# PD.net
KiCad netlist of a schematic drawn in Altium Designer
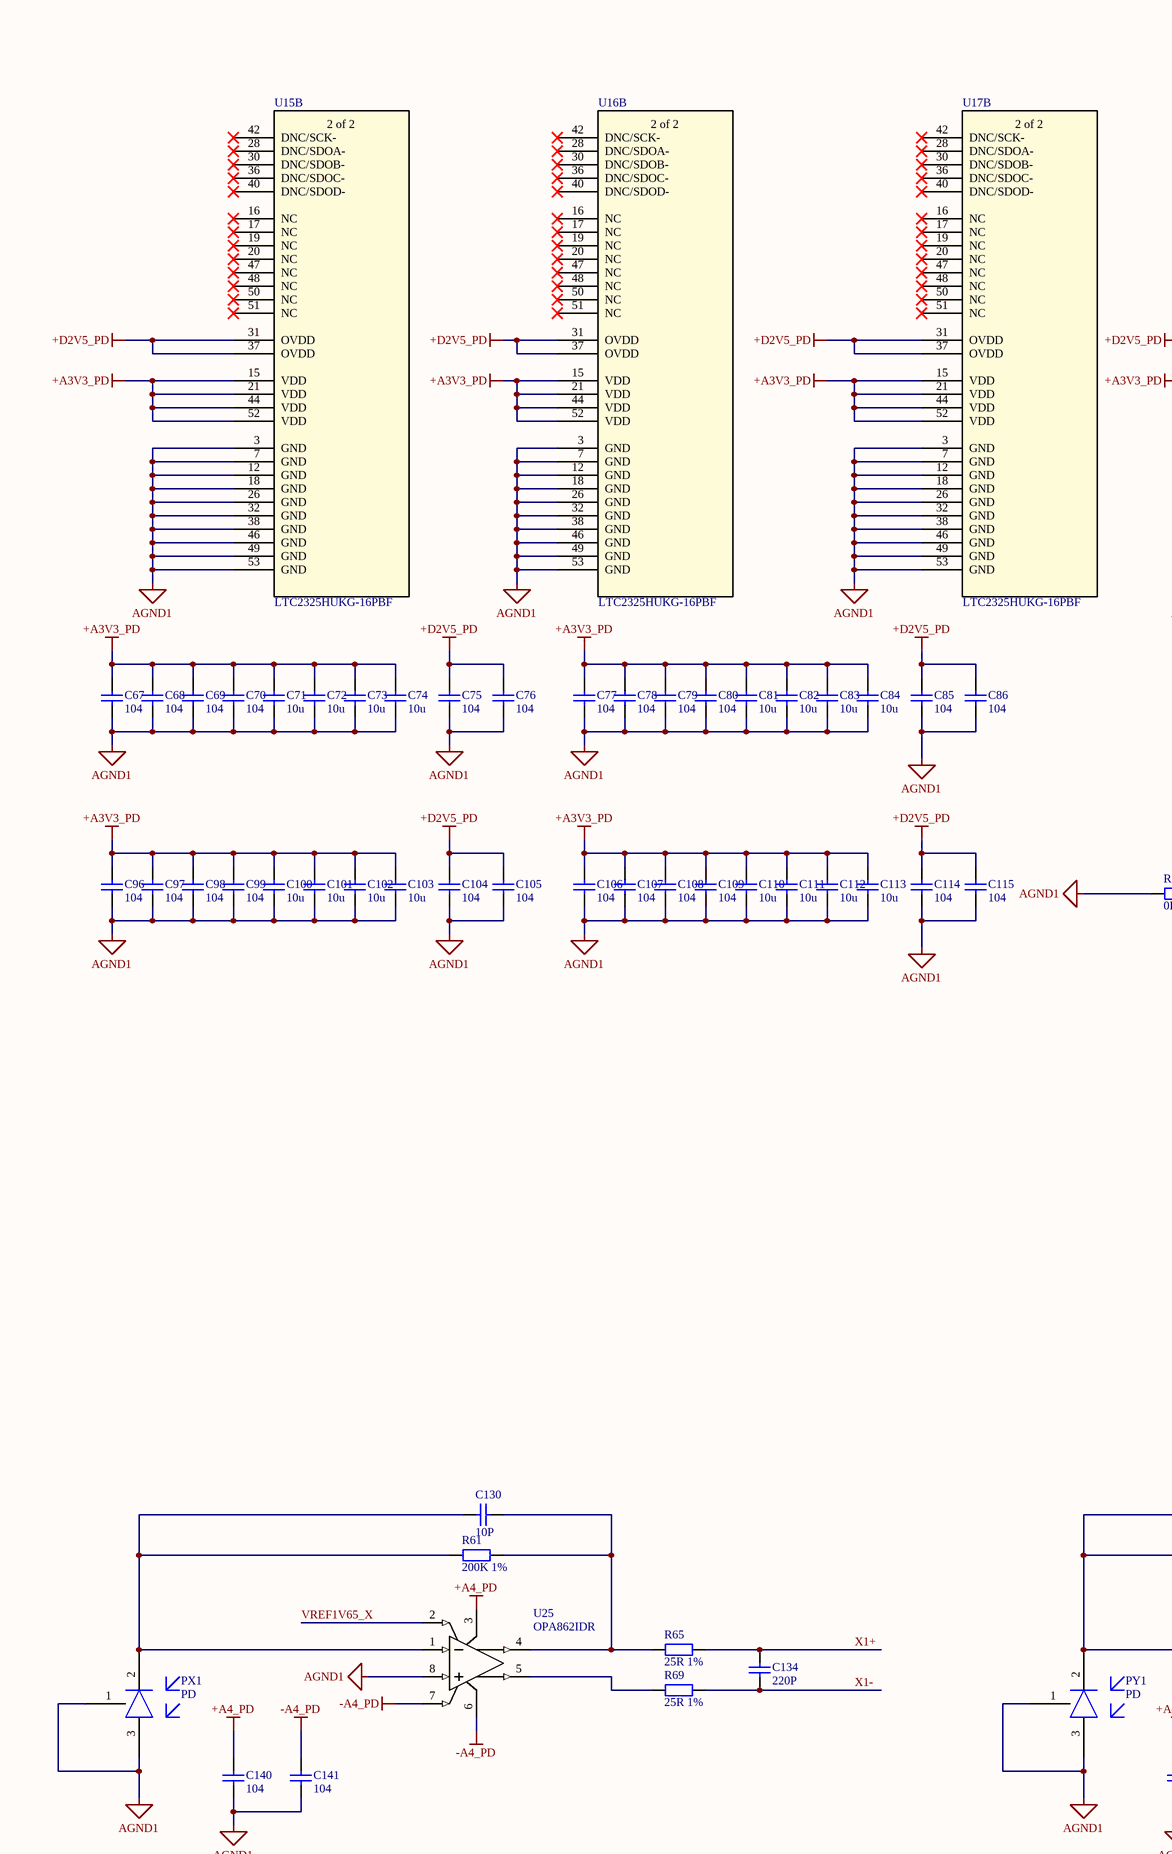
[diagram p0: PD.SchDoc, top left]
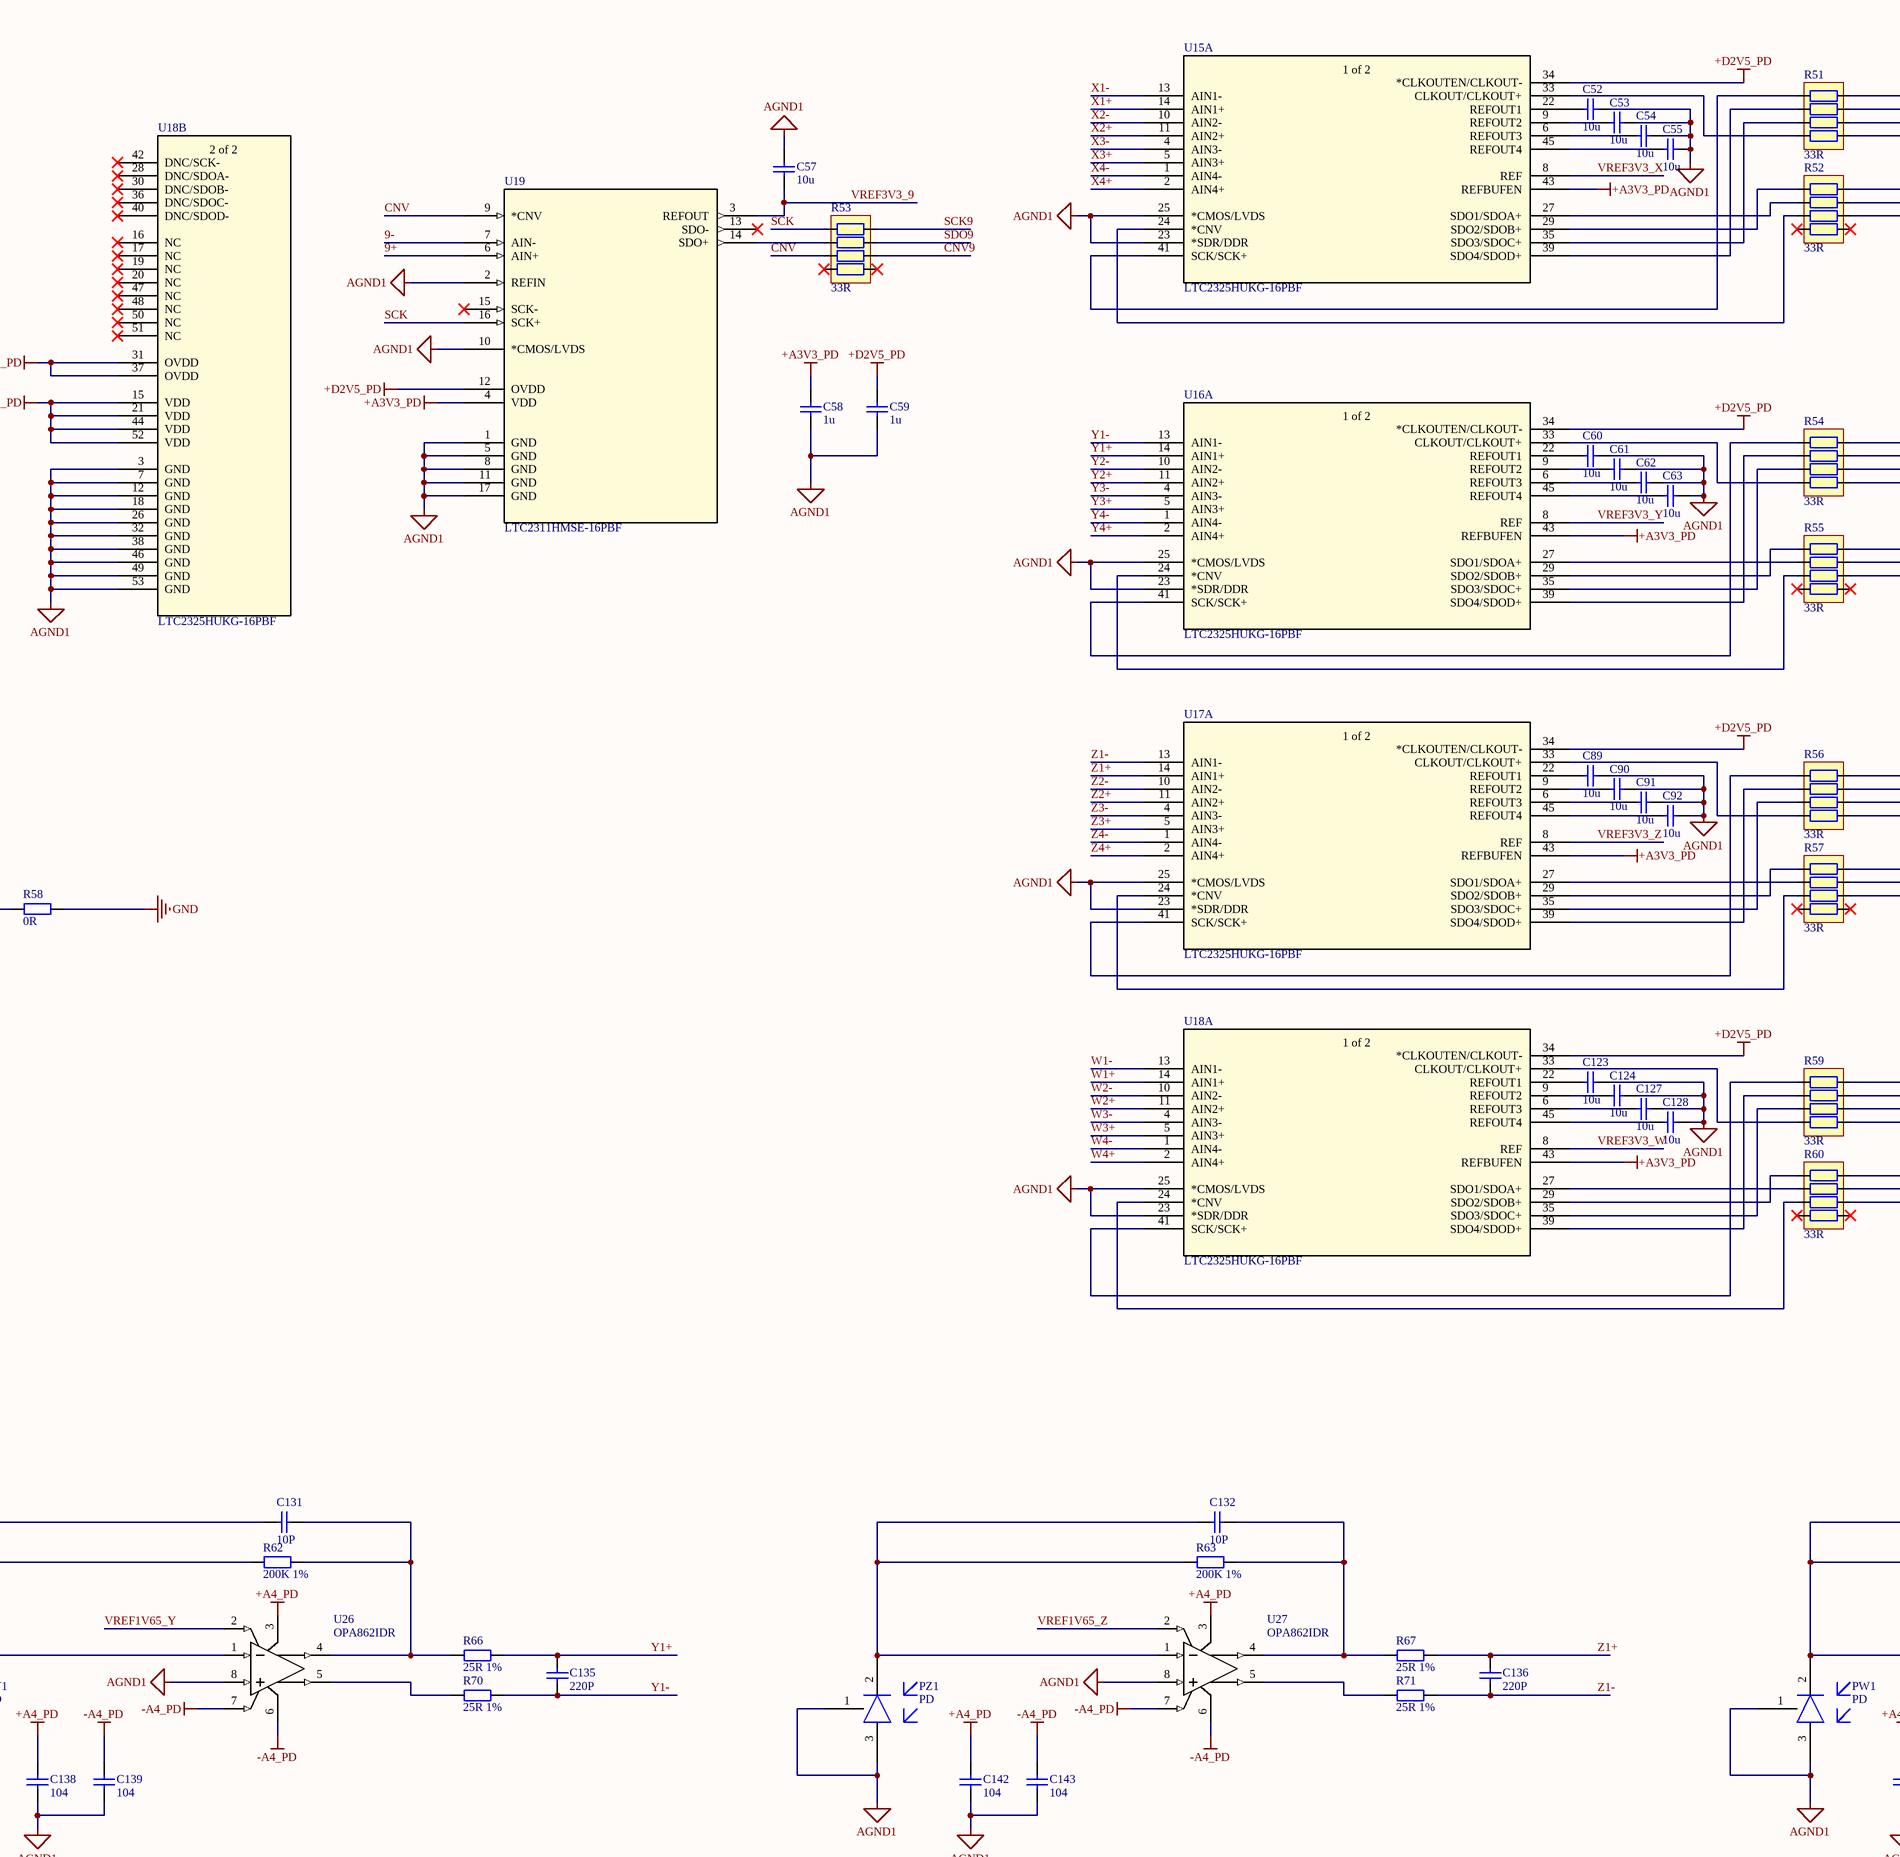
[diagram p1: PD.SchDoc, top middle]
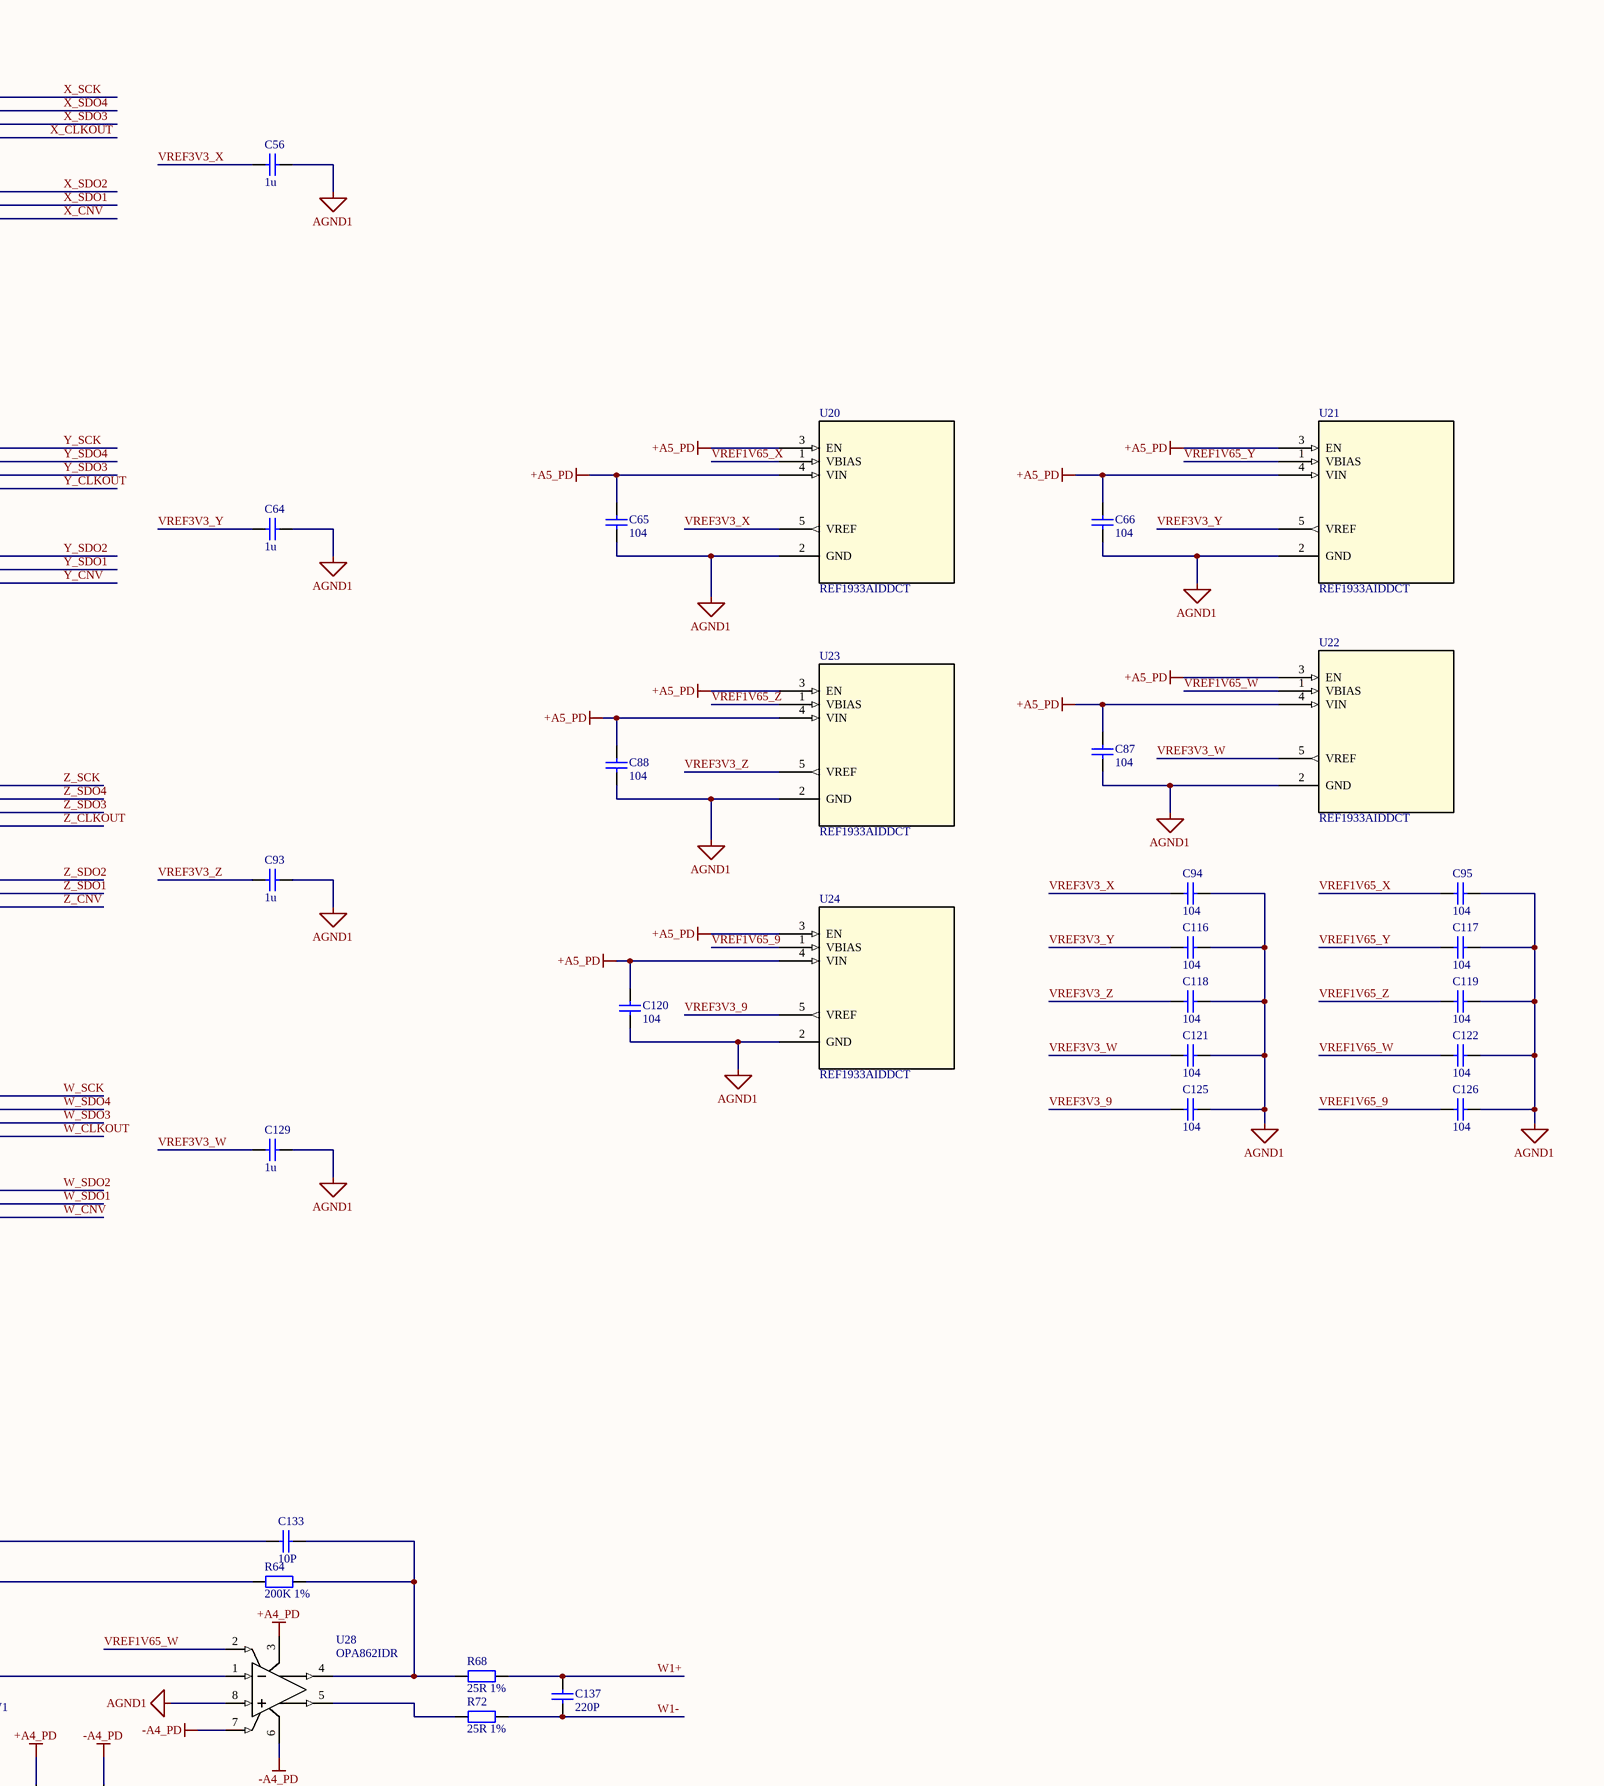
[diagram p2: PD.SchDoc, top right]
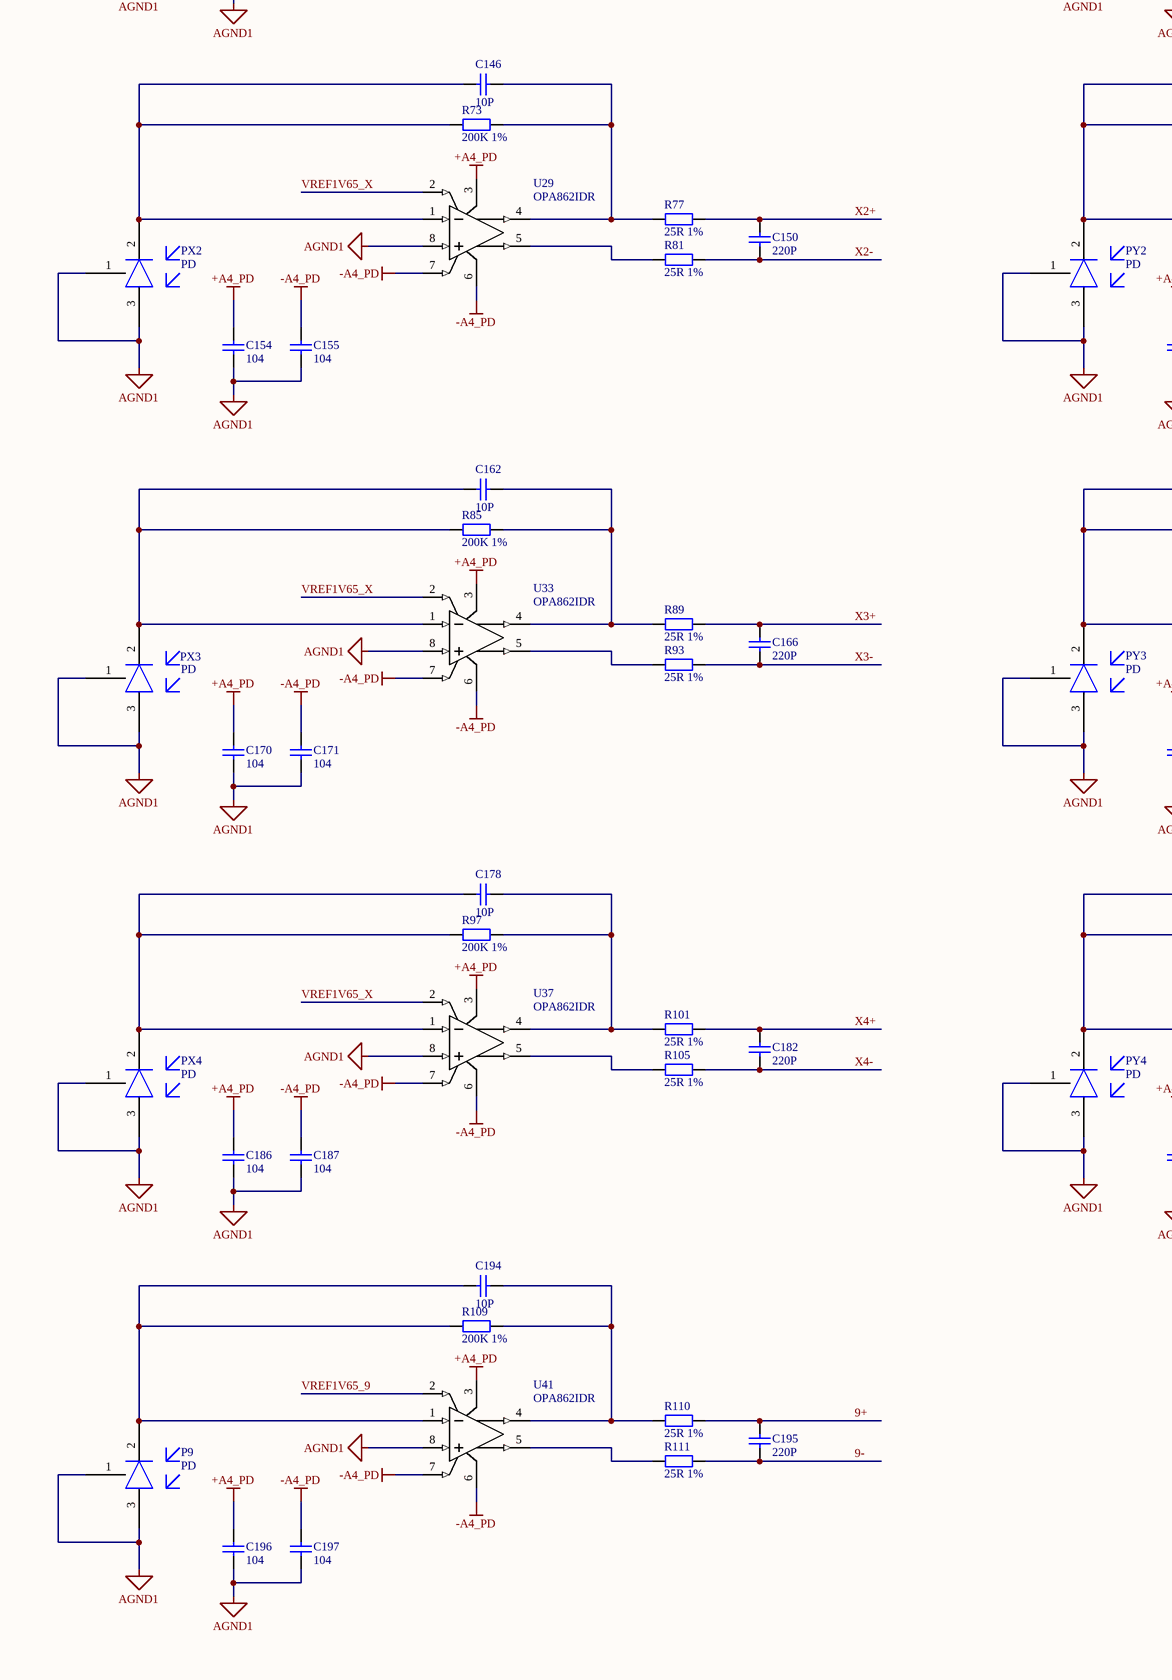
[diagram p3: PD.SchDoc, bottom left]
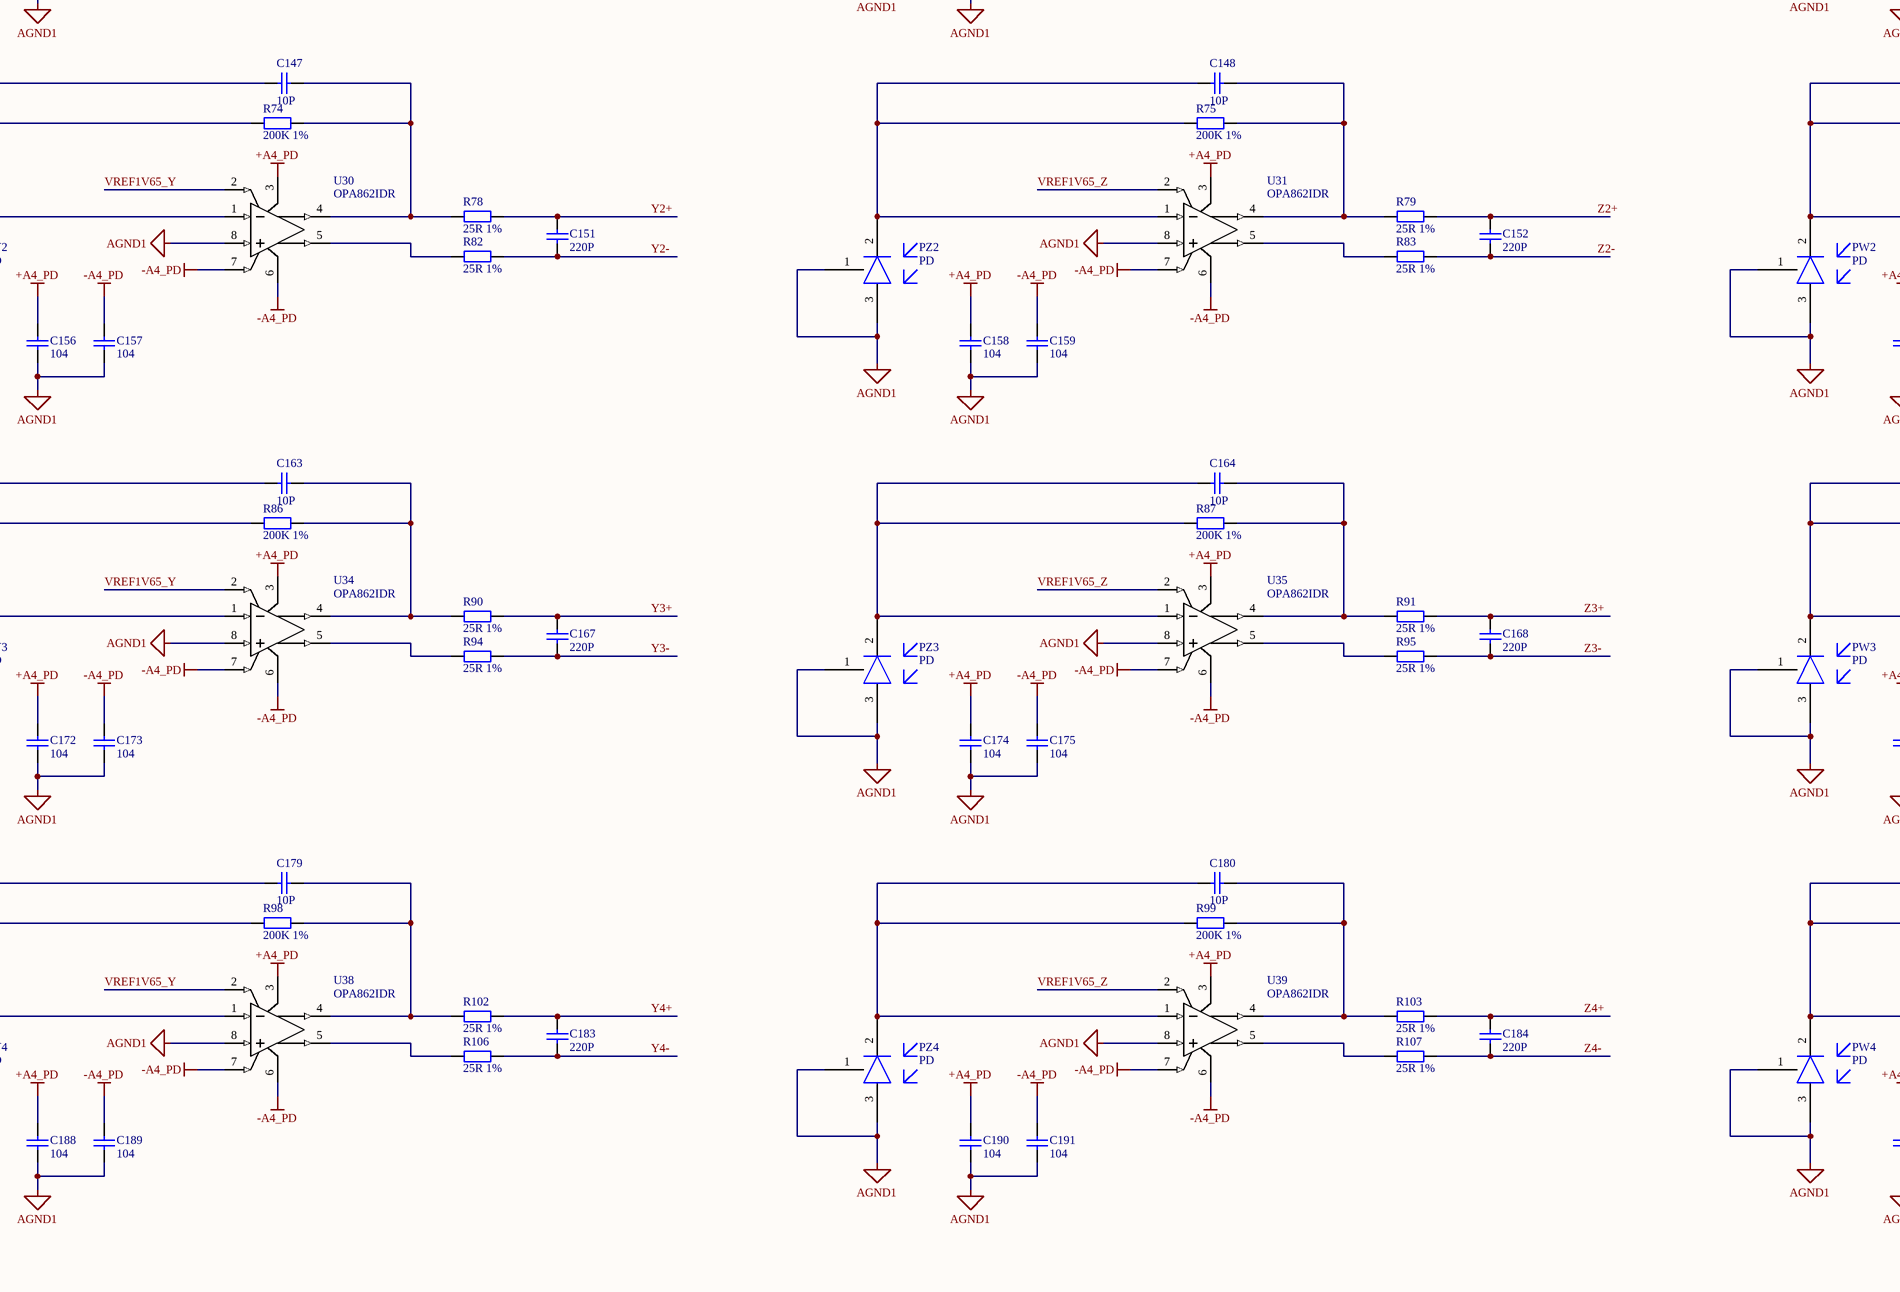
[diagram p4: PD.SchDoc, bottom middle]
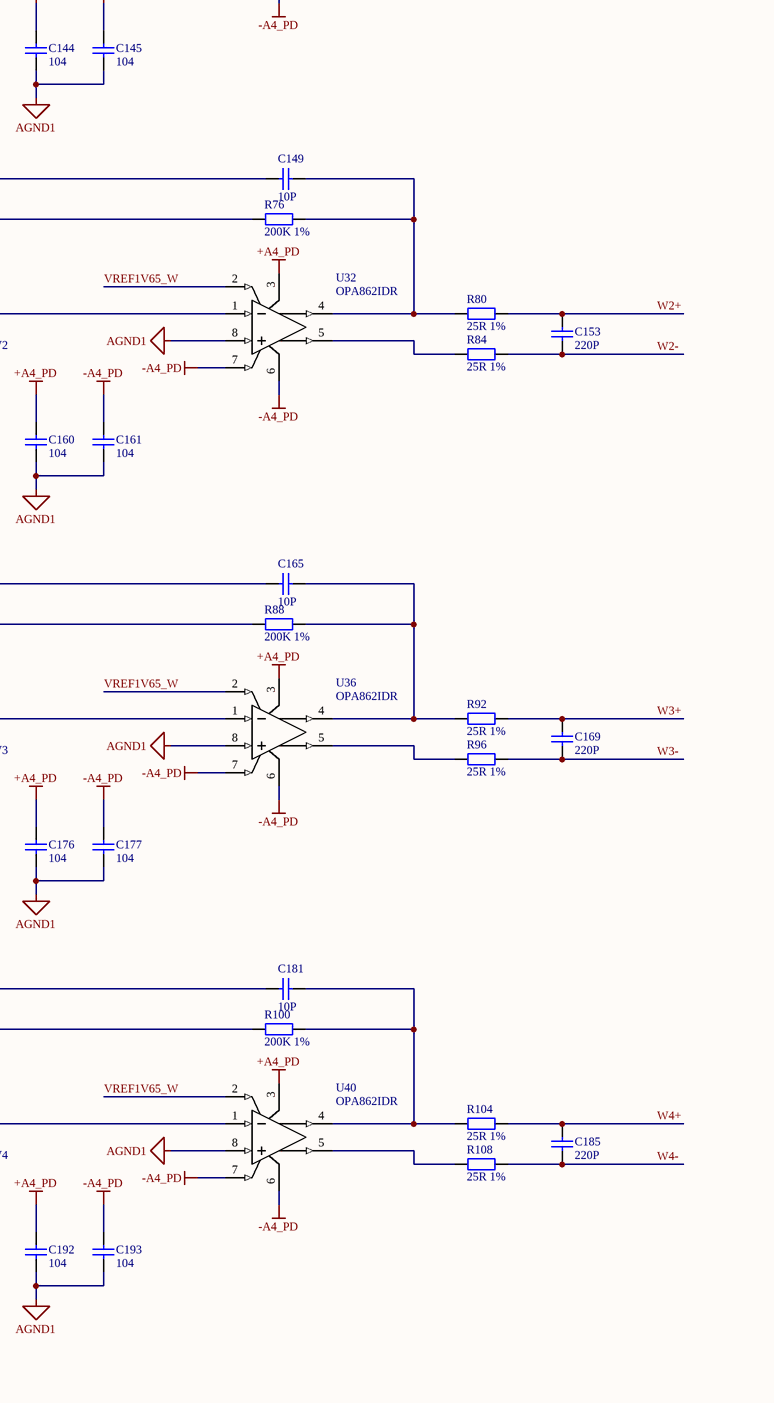
[diagram p5: PD.SchDoc, bottom right]

(export (version "E")
  (design (tool "Eeschema 10.0.6"))
  (components
    (comp (ref "C52")
      (value "10u")
      (footprint "C0805_L")
      (description "贴片电容/MLCC电容")
      (libsource (lib "0.1 - 电阻-电容-电感-保险丝-晶振-晶体-磁珠-电位器-法拉电容-馈通电容") (part "C"))
    )
    (comp (ref "C53")
      (value "10u")
      (footprint "C0805_L")
      (description "贴片电容/MLCC电容")
      (libsource (lib "0.1 - 电阻-电容-电感-保险丝-晶振-晶体-磁珠-电位器-法拉电容-馈通电容") (part "C"))
    )
    (comp (ref "C54")
      (value "10u")
      (footprint "C0805_L")
      (description "贴片电容/MLCC电容")
      (libsource (lib "0.1 - 电阻-电容-电感-保险丝-晶振-晶体-磁珠-电位器-法拉电容-馈通电容") (part "C"))
    )
    (comp (ref "C55")
      (value "10u")
      (footprint "C0805_L")
      (description "贴片电容/MLCC电容")
      (libsource (lib "0.1 - 电阻-电容-电感-保险丝-晶振-晶体-磁珠-电位器-法拉电容-馈通电容") (part "C"))
    )
    (comp (ref "C56")
      (value "1u")
      (footprint "C0805_L")
      (description "贴片电容/MLCC电容")
      (libsource (lib "0.1 - 电阻-电容-电感-保险丝-晶振-晶体-磁珠-电位器-法拉电容-馈通电容") (part "C"))
    )
    (comp (ref "C57")
      (value "10u")
      (footprint "C0805_L")
      (description "贴片电容/MLCC电容")
      (libsource (lib "0.1 - 电阻-电容-电感-保险丝-晶振-晶体-磁珠-电位器-法拉电容-馈通电容") (part "C"))
    )
    (comp (ref "C58")
      (value "1u")
      (footprint "C0402_L")
      (description "贴片电容/MLCC电容")
      (libsource (lib "0.1 - 电阻-电容-电感-保险丝-晶振-晶体-磁珠-电位器-法拉电容-馈通电容") (part "C"))
    )
    (comp (ref "C59")
      (value "1u")
      (footprint "C0402_L")
      (description "贴片电容/MLCC电容")
      (libsource (lib "0.1 - 电阻-电容-电感-保险丝-晶振-晶体-磁珠-电位器-法拉电容-馈通电容") (part "C"))
    )
    (comp (ref "C60")
      (value "10u")
      (footprint "C0805_L")
      (description "贴片电容/MLCC电容")
      (libsource (lib "0.1 - 电阻-电容-电感-保险丝-晶振-晶体-磁珠-电位器-法拉电容-馈通电容") (part "C"))
    )
    (comp (ref "C61")
      (value "10u")
      (footprint "C0805_L")
      (description "贴片电容/MLCC电容")
      (libsource (lib "0.1 - 电阻-电容-电感-保险丝-晶振-晶体-磁珠-电位器-法拉电容-馈通电容") (part "C"))
    )
    (comp (ref "C62")
      (value "10u")
      (footprint "C0805_L")
      (description "贴片电容/MLCC电容")
      (libsource (lib "0.1 - 电阻-电容-电感-保险丝-晶振-晶体-磁珠-电位器-法拉电容-馈通电容") (part "C"))
    )
    (comp (ref "C63")
      (value "10u")
      (footprint "C0805_L")
      (description "贴片电容/MLCC电容")
      (libsource (lib "0.1 - 电阻-电容-电感-保险丝-晶振-晶体-磁珠-电位器-法拉电容-馈通电容") (part "C"))
    )
    (comp (ref "C64")
      (value "1u")
      (footprint "C0805_L")
      (description "贴片电容/MLCC电容")
      (libsource (lib "0.1 - 电阻-电容-电感-保险丝-晶振-晶体-磁珠-电位器-法拉电容-馈通电容") (part "C"))
    )
    (comp (ref "C65")
      (value "104")
      (footprint "C0402_L")
      (description "贴片电容/MLCC电容")
      (libsource (lib "0.1 - 电阻-电容-电感-保险丝-晶振-晶体-磁珠-电位器-法拉电容-馈通电容") (part "C"))
    )
    (comp (ref "C66")
      (value "104")
      (footprint "C0402_L")
      (description "贴片电容/MLCC电容")
      (libsource (lib "0.1 - 电阻-电容-电感-保险丝-晶振-晶体-磁珠-电位器-法拉电容-馈通电容") (part "C"))
    )
    (comp (ref "C67")
      (value "104")
      (footprint "C0402_L")
      (description "贴片电容/MLCC电容")
      (libsource (lib "0.1 - 电阻-电容-电感-保险丝-晶振-晶体-磁珠-电位器-法拉电容-馈通电容") (part "C"))
    )
    (comp (ref "C68")
      (value "104")
      (footprint "C0402_L")
      (description "贴片电容/MLCC电容")
      (libsource (lib "0.1 - 电阻-电容-电感-保险丝-晶振-晶体-磁珠-电位器-法拉电容-馈通电容") (part "C"))
    )
    (comp (ref "C69")
      (value "104")
      (footprint "C0402_L")
      (description "贴片电容/MLCC电容")
      (libsource (lib "0.1 - 电阻-电容-电感-保险丝-晶振-晶体-磁珠-电位器-法拉电容-馈通电容") (part "C"))
    )
    (comp (ref "C70")
      (value "104")
      (footprint "C0402_L")
      (description "贴片电容/MLCC电容")
      (libsource (lib "0.1 - 电阻-电容-电感-保险丝-晶振-晶体-磁珠-电位器-法拉电容-馈通电容") (part "C"))
    )
    (comp (ref "C71")
      (value "10u")
      (footprint "C0402_L")
      (description "贴片电容/MLCC电容")
      (libsource (lib "0.1 - 电阻-电容-电感-保险丝-晶振-晶体-磁珠-电位器-法拉电容-馈通电容") (part "C"))
    )
    (comp (ref "C72")
      (value "10u")
      (footprint "C0402_L")
      (description "贴片电容/MLCC电容")
      (libsource (lib "0.1 - 电阻-电容-电感-保险丝-晶振-晶体-磁珠-电位器-法拉电容-馈通电容") (part "C"))
    )
    (comp (ref "C73")
      (value "10u")
      (footprint "C0402_L")
      (description "贴片电容/MLCC电容")
      (libsource (lib "0.1 - 电阻-电容-电感-保险丝-晶振-晶体-磁珠-电位器-法拉电容-馈通电容") (part "C"))
    )
    (comp (ref "C74")
      (value "10u")
      (footprint "C0402_L")
      (description "贴片电容/MLCC电容")
      (libsource (lib "0.1 - 电阻-电容-电感-保险丝-晶振-晶体-磁珠-电位器-法拉电容-馈通电容") (part "C"))
    )
    (comp (ref "C75")
      (value "104")
      (footprint "C0402_L")
      (description "贴片电容/MLCC电容")
      (libsource (lib "0.1 - 电阻-电容-电感-保险丝-晶振-晶体-磁珠-电位器-法拉电容-馈通电容") (part "C"))
    )
    (comp (ref "C76")
      (value "104")
      (footprint "C0402_L")
      (description "贴片电容/MLCC电容")
      (libsource (lib "0.1 - 电阻-电容-电感-保险丝-晶振-晶体-磁珠-电位器-法拉电容-馈通电容") (part "C"))
    )
    (comp (ref "C77")
      (value "104")
      (footprint "C0402_L")
      (description "贴片电容/MLCC电容")
      (libsource (lib "0.1 - 电阻-电容-电感-保险丝-晶振-晶体-磁珠-电位器-法拉电容-馈通电容") (part "C"))
    )
    (comp (ref "C78")
      (value "104")
      (footprint "C0402_L")
      (description "贴片电容/MLCC电容")
      (libsource (lib "0.1 - 电阻-电容-电感-保险丝-晶振-晶体-磁珠-电位器-法拉电容-馈通电容") (part "C"))
    )
    (comp (ref "C79")
      (value "104")
      (footprint "C0402_L")
      (description "贴片电容/MLCC电容")
      (libsource (lib "0.1 - 电阻-电容-电感-保险丝-晶振-晶体-磁珠-电位器-法拉电容-馈通电容") (part "C"))
    )
    (comp (ref "C80")
      (value "104")
      (footprint "C0402_L")
      (description "贴片电容/MLCC电容")
      (libsource (lib "0.1 - 电阻-电容-电感-保险丝-晶振-晶体-磁珠-电位器-法拉电容-馈通电容") (part "C"))
    )
    (comp (ref "C81")
      (value "10u")
      (footprint "C0402_L")
      (description "贴片电容/MLCC电容")
      (libsource (lib "0.1 - 电阻-电容-电感-保险丝-晶振-晶体-磁珠-电位器-法拉电容-馈通电容") (part "C"))
    )
    (comp (ref "C82")
      (value "10u")
      (footprint "C0402_L")
      (description "贴片电容/MLCC电容")
      (libsource (lib "0.1 - 电阻-电容-电感-保险丝-晶振-晶体-磁珠-电位器-法拉电容-馈通电容") (part "C"))
    )
    (comp (ref "C83")
      (value "10u")
      (footprint "C0402_L")
      (description "贴片电容/MLCC电容")
      (libsource (lib "0.1 - 电阻-电容-电感-保险丝-晶振-晶体-磁珠-电位器-法拉电容-馈通电容") (part "C"))
    )
    (comp (ref "C84")
      (value "10u")
      (footprint "C0402_L")
      (description "贴片电容/MLCC电容")
      (libsource (lib "0.1 - 电阻-电容-电感-保险丝-晶振-晶体-磁珠-电位器-法拉电容-馈通电容") (part "C"))
    )
    (comp (ref "C85")
      (value "104")
      (footprint "C0402_L")
      (description "贴片电容/MLCC电容")
      (libsource (lib "0.1 - 电阻-电容-电感-保险丝-晶振-晶体-磁珠-电位器-法拉电容-馈通电容") (part "C"))
    )
    (comp (ref "C86")
      (value "104")
      (footprint "C0402_L")
      (description "贴片电容/MLCC电容")
      (libsource (lib "0.1 - 电阻-电容-电感-保险丝-晶振-晶体-磁珠-电位器-法拉电容-馈通电容") (part "C"))
    )
    (comp (ref "C87")
      (value "104")
      (footprint "C0402_L")
      (description "贴片电容/MLCC电容")
      (libsource (lib "0.1 - 电阻-电容-电感-保险丝-晶振-晶体-磁珠-电位器-法拉电容-馈通电容") (part "C"))
    )
    (comp (ref "C88")
      (value "104")
      (footprint "C0402_L")
      (description "贴片电容/MLCC电容")
      (libsource (lib "0.1 - 电阻-电容-电感-保险丝-晶振-晶体-磁珠-电位器-法拉电容-馈通电容") (part "C"))
    )
    (comp (ref "C89")
      (value "10u")
      (footprint "C0805_L")
      (description "贴片电容/MLCC电容")
      (libsource (lib "0.1 - 电阻-电容-电感-保险丝-晶振-晶体-磁珠-电位器-法拉电容-馈通电容") (part "C"))
    )
    (comp (ref "C90")
      (value "10u")
      (footprint "C0805_L")
      (description "贴片电容/MLCC电容")
      (libsource (lib "0.1 - 电阻-电容-电感-保险丝-晶振-晶体-磁珠-电位器-法拉电容-馈通电容") (part "C"))
    )
    (comp (ref "C91")
      (value "10u")
      (footprint "C0805_L")
      (description "贴片电容/MLCC电容")
      (libsource (lib "0.1 - 电阻-电容-电感-保险丝-晶振-晶体-磁珠-电位器-法拉电容-馈通电容") (part "C"))
    )
    (comp (ref "C92")
      (value "10u")
      (footprint "C0805_L")
      (description "贴片电容/MLCC电容")
      (libsource (lib "0.1 - 电阻-电容-电感-保险丝-晶振-晶体-磁珠-电位器-法拉电容-馈通电容") (part "C"))
    )
    (comp (ref "C93")
      (value "1u")
      (footprint "C0805_L")
      (description "贴片电容/MLCC电容")
      (libsource (lib "0.1 - 电阻-电容-电感-保险丝-晶振-晶体-磁珠-电位器-法拉电容-馈通电容") (part "C"))
    )
    (comp (ref "C94")
      (value "104")
      (footprint "C0402_L")
      (description "贴片电容/MLCC电容")
      (libsource (lib "0.1 - 电阻-电容-电感-保险丝-晶振-晶体-磁珠-电位器-法拉电容-馈通电容") (part "C"))
    )
    (comp (ref "C95")
      (value "104")
      (footprint "C0402_L")
      (description "贴片电容/MLCC电容")
      (libsource (lib "0.1 - 电阻-电容-电感-保险丝-晶振-晶体-磁珠-电位器-法拉电容-馈通电容") (part "C"))
    )
    (comp (ref "C96")
      (value "104")
      (footprint "C0402_L")
      (description "贴片电容/MLCC电容")
      (libsource (lib "0.1 - 电阻-电容-电感-保险丝-晶振-晶体-磁珠-电位器-法拉电容-馈通电容") (part "C"))
    )
    (comp (ref "C97")
      (value "104")
      (footprint "C0402_L")
      (description "贴片电容/MLCC电容")
      (libsource (lib "0.1 - 电阻-电容-电感-保险丝-晶振-晶体-磁珠-电位器-法拉电容-馈通电容") (part "C"))
    )
    (comp (ref "C98")
      (value "104")
      (footprint "C0402_L")
      (description "贴片电容/MLCC电容")
      (libsource (lib "0.1 - 电阻-电容-电感-保险丝-晶振-晶体-磁珠-电位器-法拉电容-馈通电容") (part "C"))
    )
    (comp (ref "C99")
      (value "104")
      (footprint "C0402_L")
      (description "贴片电容/MLCC电容")
      (libsource (lib "0.1 - 电阻-电容-电感-保险丝-晶振-晶体-磁珠-电位器-法拉电容-馈通电容") (part "C"))
    )
    (comp (ref "C100")
      (value "10u")
      (footprint "C0402_L")
      (description "贴片电容/MLCC电容")
      (libsource (lib "0.1 - 电阻-电容-电感-保险丝-晶振-晶体-磁珠-电位器-法拉电容-馈通电容") (part "C"))
    )
    (comp (ref "C101")
      (value "10u")
      (footprint "C0402_L")
      (description "贴片电容/MLCC电容")
      (libsource (lib "0.1 - 电阻-电容-电感-保险丝-晶振-晶体-磁珠-电位器-法拉电容-馈通电容") (part "C"))
    )
    (comp (ref "C102")
      (value "10u")
      (footprint "C0402_L")
      (description "贴片电容/MLCC电容")
      (libsource (lib "0.1 - 电阻-电容-电感-保险丝-晶振-晶体-磁珠-电位器-法拉电容-馈通电容") (part "C"))
    )
    (comp (ref "C103")
      (value "10u")
      (footprint "C0402_L")
      (description "贴片电容/MLCC电容")
      (libsource (lib "0.1 - 电阻-电容-电感-保险丝-晶振-晶体-磁珠-电位器-法拉电容-馈通电容") (part "C"))
    )
    (comp (ref "C104")
      (value "104")
      (footprint "C0402_L")
      (description "贴片电容/MLCC电容")
      (libsource (lib "0.1 - 电阻-电容-电感-保险丝-晶振-晶体-磁珠-电位器-法拉电容-馈通电容") (part "C"))
    )
    (comp (ref "C105")
      (value "104")
      (footprint "C0402_L")
      (description "贴片电容/MLCC电容")
      (libsource (lib "0.1 - 电阻-电容-电感-保险丝-晶振-晶体-磁珠-电位器-法拉电容-馈通电容") (part "C"))
    )
    (comp (ref "C106")
      (value "104")
      (footprint "C0402_L")
      (description "贴片电容/MLCC电容")
      (libsource (lib "0.1 - 电阻-电容-电感-保险丝-晶振-晶体-磁珠-电位器-法拉电容-馈通电容") (part "C"))
    )
    (comp (ref "C107")
      (value "104")
      (footprint "C0402_L")
      (description "贴片电容/MLCC电容")
      (libsource (lib "0.1 - 电阻-电容-电感-保险丝-晶振-晶体-磁珠-电位器-法拉电容-馈通电容") (part "C"))
    )
    (comp (ref "C108")
      (value "104")
      (footprint "C0402_L")
      (description "贴片电容/MLCC电容")
      (libsource (lib "0.1 - 电阻-电容-电感-保险丝-晶振-晶体-磁珠-电位器-法拉电容-馈通电容") (part "C"))
    )
    (comp (ref "C109")
      (value "104")
      (footprint "C0402_L")
      (description "贴片电容/MLCC电容")
      (libsource (lib "0.1 - 电阻-电容-电感-保险丝-晶振-晶体-磁珠-电位器-法拉电容-馈通电容") (part "C"))
    )
    (comp (ref "C110")
      (value "10u")
      (footprint "C0402_L")
      (description "贴片电容/MLCC电容")
      (libsource (lib "0.1 - 电阻-电容-电感-保险丝-晶振-晶体-磁珠-电位器-法拉电容-馈通电容") (part "C"))
    )
    (comp (ref "C111")
      (value "10u")
      (footprint "C0402_L")
      (description "贴片电容/MLCC电容")
      (libsource (lib "0.1 - 电阻-电容-电感-保险丝-晶振-晶体-磁珠-电位器-法拉电容-馈通电容") (part "C"))
    )
    (comp (ref "C112")
      (value "10u")
      (footprint "C0402_L")
      (description "贴片电容/MLCC电容")
      (libsource (lib "0.1 - 电阻-电容-电感-保险丝-晶振-晶体-磁珠-电位器-法拉电容-馈通电容") (part "C"))
    )
    (comp (ref "C113")
      (value "10u")
      (footprint "C0402_L")
      (description "贴片电容/MLCC电容")
      (libsource (lib "0.1 - 电阻-电容-电感-保险丝-晶振-晶体-磁珠-电位器-法拉电容-馈通电容") (part "C"))
    )
    (comp (ref "C114")
      (value "104")
      (footprint "C0402_L")
      (description "贴片电容/MLCC电容")
      (libsource (lib "0.1 - 电阻-电容-电感-保险丝-晶振-晶体-磁珠-电位器-法拉电容-馈通电容") (part "C"))
    )
    (comp (ref "C115")
      (value "104")
      (footprint "C0402_L")
      (description "贴片电容/MLCC电容")
      (libsource (lib "0.1 - 电阻-电容-电感-保险丝-晶振-晶体-磁珠-电位器-法拉电容-馈通电容") (part "C"))
    )
    (comp (ref "C116")
      (value "104")
      (footprint "C0402_L")
      (description "贴片电容/MLCC电容")
      (libsource (lib "0.1 - 电阻-电容-电感-保险丝-晶振-晶体-磁珠-电位器-法拉电容-馈通电容") (part "C"))
    )
    (comp (ref "C117")
      (value "104")
      (footprint "C0402_L")
      (description "贴片电容/MLCC电容")
      (libsource (lib "0.1 - 电阻-电容-电感-保险丝-晶振-晶体-磁珠-电位器-法拉电容-馈通电容") (part "C"))
    )
    (comp (ref "C118")
      (value "104")
      (footprint "C0402_L")
      (description "贴片电容/MLCC电容")
      (libsource (lib "0.1 - 电阻-电容-电感-保险丝-晶振-晶体-磁珠-电位器-法拉电容-馈通电容") (part "C"))
    )
    (comp (ref "C119")
      (value "104")
      (footprint "C0402_L")
      (description "贴片电容/MLCC电容")
      (libsource (lib "0.1 - 电阻-电容-电感-保险丝-晶振-晶体-磁珠-电位器-法拉电容-馈通电容") (part "C"))
    )
    (comp (ref "C120")
      (value "104")
      (footprint "C0402_L")
      (description "贴片电容/MLCC电容")
      (libsource (lib "0.1 - 电阻-电容-电感-保险丝-晶振-晶体-磁珠-电位器-法拉电容-馈通电容") (part "C"))
    )
    (comp (ref "C121")
      (value "104")
      (footprint "C0402_L")
      (description "贴片电容/MLCC电容")
      (libsource (lib "0.1 - 电阻-电容-电感-保险丝-晶振-晶体-磁珠-电位器-法拉电容-馈通电容") (part "C"))
    )
    (comp (ref "C122")
      (value "104")
      (footprint "C0402_L")
      (description "贴片电容/MLCC电容")
      (libsource (lib "0.1 - 电阻-电容-电感-保险丝-晶振-晶体-磁珠-电位器-法拉电容-馈通电容") (part "C"))
    )
    (comp (ref "C123")
      (value "10u")
      (footprint "C0805_L")
      (description "贴片电容/MLCC电容")
      (libsource (lib "0.1 - 电阻-电容-电感-保险丝-晶振-晶体-磁珠-电位器-法拉电容-馈通电容") (part "C"))
    )
    (comp (ref "C124")
      (value "10u")
      (footprint "C0805_L")
      (description "贴片电容/MLCC电容")
      (libsource (lib "0.1 - 电阻-电容-电感-保险丝-晶振-晶体-磁珠-电位器-法拉电容-馈通电容") (part "C"))
    )
    (comp (ref "C125")
      (value "104")
      (footprint "C0402_L")
      (description "贴片电容/MLCC电容")
      (libsource (lib "0.1 - 电阻-电容-电感-保险丝-晶振-晶体-磁珠-电位器-法拉电容-馈通电容") (part "C"))
    )
    (comp (ref "C126")
      (value "104")
      (footprint "C0402_L")
      (description "贴片电容/MLCC电容")
      (libsource (lib "0.1 - 电阻-电容-电感-保险丝-晶振-晶体-磁珠-电位器-法拉电容-馈通电容") (part "C"))
    )
    (comp (ref "C127")
      (value "10u")
      (footprint "C0805_L")
      (description "贴片电容/MLCC电容")
      (libsource (lib "0.1 - 电阻-电容-电感-保险丝-晶振-晶体-磁珠-电位器-法拉电容-馈通电容") (part "C"))
    )
    (comp (ref "C128")
      (value "10u")
      (footprint "C0805_L")
      (description "贴片电容/MLCC电容")
      (libsource (lib "0.1 - 电阻-电容-电感-保险丝-晶振-晶体-磁珠-电位器-法拉电容-馈通电容") (part "C"))
    )
    (comp (ref "C129")
      (value "1u")
      (footprint "C0805_L")
      (description "贴片电容/MLCC电容")
      (libsource (lib "0.1 - 电阻-电容-电感-保险丝-晶振-晶体-磁珠-电位器-法拉电容-馈通电容") (part "C"))
    )
    (comp (ref "C130")
      (value "10P")
      (footprint "C0402_L")
      (description "贴片电容/MLCC电容")
      (libsource (lib "0.1 - 电阻-电容-电感-保险丝-晶振-晶体-磁珠-电位器-法拉电容-馈通电容") (part "C"))
    )
    (comp (ref "C131")
      (value "10P")
      (footprint "C0402_L")
      (description "贴片电容/MLCC电容")
      (libsource (lib "0.1 - 电阻-电容-电感-保险丝-晶振-晶体-磁珠-电位器-法拉电容-馈通电容") (part "C"))
    )
    (comp (ref "C132")
      (value "10P")
      (footprint "C0402_L")
      (description "贴片电容/MLCC电容")
      (libsource (lib "0.1 - 电阻-电容-电感-保险丝-晶振-晶体-磁珠-电位器-法拉电容-馈通电容") (part "C"))
    )
    (comp (ref "C133")
      (value "10P")
      (footprint "C0402_L")
      (description "贴片电容/MLCC电容")
      (libsource (lib "0.1 - 电阻-电容-电感-保险丝-晶振-晶体-磁珠-电位器-法拉电容-馈通电容") (part "C"))
    )
    (comp (ref "C134")
      (value "220P")
      (footprint "C0402_L")
      (description "贴片电容/MLCC电容")
      (libsource (lib "0.1 - 电阻-电容-电感-保险丝-晶振-晶体-磁珠-电位器-法拉电容-馈通电容") (part "C"))
    )
    (comp (ref "C135")
      (value "220P")
      (footprint "C0402_L")
      (description "贴片电容/MLCC电容")
      (libsource (lib "0.1 - 电阻-电容-电感-保险丝-晶振-晶体-磁珠-电位器-法拉电容-馈通电容") (part "C"))
    )
    (comp (ref "C136")
      (value "220P")
      (footprint "C0402_L")
      (description "贴片电容/MLCC电容")
      (libsource (lib "0.1 - 电阻-电容-电感-保险丝-晶振-晶体-磁珠-电位器-法拉电容-馈通电容") (part "C"))
    )
    (comp (ref "C137")
      (value "220P")
      (footprint "C0402_L")
      (description "贴片电容/MLCC电容")
      (libsource (lib "0.1 - 电阻-电容-电感-保险丝-晶振-晶体-磁珠-电位器-法拉电容-馈通电容") (part "C"))
    )
    (comp (ref "C138")
      (value "104")
      (footprint "C0402_L")
      (description "贴片电容/MLCC电容")
      (libsource (lib "0.1 - 电阻-电容-电感-保险丝-晶振-晶体-磁珠-电位器-法拉电容-馈通电容") (part "C"))
    )
    (comp (ref "C139")
      (value "104")
      (footprint "C0402_L")
      (description "贴片电容/MLCC电容")
      (libsource (lib "0.1 - 电阻-电容-电感-保险丝-晶振-晶体-磁珠-电位器-法拉电容-馈通电容") (part "C"))
    )
    (comp (ref "C140")
      (value "104")
      (footprint "C0402_L")
      (description "贴片电容/MLCC电容")
      (libsource (lib "0.1 - 电阻-电容-电感-保险丝-晶振-晶体-磁珠-电位器-法拉电容-馈通电容") (part "C"))
    )
    (comp (ref "C141")
      (value "104")
      (footprint "C0402_L")
      (description "贴片电容/MLCC电容")
      (libsource (lib "0.1 - 电阻-电容-电感-保险丝-晶振-晶体-磁珠-电位器-法拉电容-馈通电容") (part "C"))
    )
    (comp (ref "C142")
      (value "104")
      (footprint "C0402_L")
      (description "贴片电容/MLCC电容")
      (libsource (lib "0.1 - 电阻-电容-电感-保险丝-晶振-晶体-磁珠-电位器-法拉电容-馈通电容") (part "C"))
    )
    (comp (ref "C143")
      (value "104")
      (footprint "C0402_L")
      (description "贴片电容/MLCC电容")
      (libsource (lib "0.1 - 电阻-电容-电感-保险丝-晶振-晶体-磁珠-电位器-法拉电容-馈通电容") (part "C"))
    )
    (comp (ref "C144")
      (value "104")
      (footprint "C0402_L")
      (description "贴片电容/MLCC电容")
      (libsource (lib "0.1 - 电阻-电容-电感-保险丝-晶振-晶体-磁珠-电位器-法拉电容-馈通电容") (part "C"))
    )
    (comp (ref "C145")
      (value "104")
      (footprint "C0402_L")
      (description "贴片电容/MLCC电容")
      (libsource (lib "0.1 - 电阻-电容-电感-保险丝-晶振-晶体-磁珠-电位器-法拉电容-馈通电容") (part "C"))
    )
    (comp (ref "C146")
      (value "10P")
      (footprint "C0402_L")
      (description "贴片电容/MLCC电容")
      (libsource (lib "0.1 - 电阻-电容-电感-保险丝-晶振-晶体-磁珠-电位器-法拉电容-馈通电容") (part "C"))
    )
    (comp (ref "C147")
      (value "10P")
      (footprint "C0402_L")
      (description "贴片电容/MLCC电容")
      (libsource (lib "0.1 - 电阻-电容-电感-保险丝-晶振-晶体-磁珠-电位器-法拉电容-馈通电容") (part "C"))
    )
    (comp (ref "C148")
      (value "10P")
      (footprint "C0402_L")
      (description "贴片电容/MLCC电容")
      (libsource (lib "0.1 - 电阻-电容-电感-保险丝-晶振-晶体-磁珠-电位器-法拉电容-馈通电容") (part "C"))
    )
    (comp (ref "C149")
      (value "10P")
      (footprint "C0402_L")
      (description "贴片电容/MLCC电容")
      (libsource (lib "0.1 - 电阻-电容-电感-保险丝-晶振-晶体-磁珠-电位器-法拉电容-馈通电容") (part "C"))
    )
    (comp (ref "C150")
      (value "220P")
      (footprint "C0402_L")
      (description "贴片电容/MLCC电容")
      (libsource (lib "0.1 - 电阻-电容-电感-保险丝-晶振-晶体-磁珠-电位器-法拉电容-馈通电容") (part "C"))
    )
    (comp (ref "C151")
      (value "220P")
      (footprint "C0402_L")
      (description "贴片电容/MLCC电容")
      (libsource (lib "0.1 - 电阻-电容-电感-保险丝-晶振-晶体-磁珠-电位器-法拉电容-馈通电容") (part "C"))
    )
    (comp (ref "C152")
      (value "220P")
      (footprint "C0402_L")
      (description "贴片电容/MLCC电容")
      (libsource (lib "0.1 - 电阻-电容-电感-保险丝-晶振-晶体-磁珠-电位器-法拉电容-馈通电容") (part "C"))
    )
    (comp (ref "C153")
      (value "220P")
      (footprint "C0402_L")
      (description "贴片电容/MLCC电容")
      (libsource (lib "0.1 - 电阻-电容-电感-保险丝-晶振-晶体-磁珠-电位器-法拉电容-馈通电容") (part "C"))
    )
    (comp (ref "C154")
      (value "104")
      (footprint "C0402_L")
      (description "贴片电容/MLCC电容")
      (libsource (lib "0.1 - 电阻-电容-电感-保险丝-晶振-晶体-磁珠-电位器-法拉电容-馈通电容") (part "C"))
    )
    (comp (ref "C155")
      (value "104")
      (footprint "C0402_L")
      (description "贴片电容/MLCC电容")
      (libsource (lib "0.1 - 电阻-电容-电感-保险丝-晶振-晶体-磁珠-电位器-法拉电容-馈通电容") (part "C"))
    )
    (comp (ref "C156")
      (value "104")
      (footprint "C0402_L")
      (description "贴片电容/MLCC电容")
      (libsource (lib "0.1 - 电阻-电容-电感-保险丝-晶振-晶体-磁珠-电位器-法拉电容-馈通电容") (part "C"))
    )
    (comp (ref "C157")
      (value "104")
      (footprint "C0402_L")
      (description "贴片电容/MLCC电容")
      (libsource (lib "0.1 - 电阻-电容-电感-保险丝-晶振-晶体-磁珠-电位器-法拉电容-馈通电容") (part "C"))
    )
    (comp (ref "C158")
      (value "104")
      (footprint "C0402_L")
      (description "贴片电容/MLCC电容")
      (libsource (lib "0.1 - 电阻-电容-电感-保险丝-晶振-晶体-磁珠-电位器-法拉电容-馈通电容") (part "C"))
    )
    (comp (ref "C159")
      (value "104")
      (footprint "C0402_L")
      (description "贴片电容/MLCC电容")
      (libsource (lib "0.1 - 电阻-电容-电感-保险丝-晶振-晶体-磁珠-电位器-法拉电容-馈通电容") (part "C"))
    )
    (comp (ref "C160")
      (value "104")
      (footprint "C0402_L")
      (description "贴片电容/MLCC电容")
      (libsource (lib "0.1 - 电阻-电容-电感-保险丝-晶振-晶体-磁珠-电位器-法拉电容-馈通电容") (part "C"))
    )
    (comp (ref "C161")
      (value "104")
      (footprint "C0402_L")
      (description "贴片电容/MLCC电容")
      (libsource (lib "0.1 - 电阻-电容-电感-保险丝-晶振-晶体-磁珠-电位器-法拉电容-馈通电容") (part "C"))
    )
    (comp (ref "C162")
      (value "10P")
      (footprint "C0402_L")
      (description "贴片电容/MLCC电容")
      (libsource (lib "0.1 - 电阻-电容-电感-保险丝-晶振-晶体-磁珠-电位器-法拉电容-馈通电容") (part "C"))
    )
    (comp (ref "C163")
      (value "10P")
      (footprint "C0402_L")
      (description "贴片电容/MLCC电容")
      (libsource (lib "0.1 - 电阻-电容-电感-保险丝-晶振-晶体-磁珠-电位器-法拉电容-馈通电容") (part "C"))
    )
    (comp (ref "C164")
      (value "10P")
      (footprint "C0402_L")
      (description "贴片电容/MLCC电容")
      (libsource (lib "0.1 - 电阻-电容-电感-保险丝-晶振-晶体-磁珠-电位器-法拉电容-馈通电容") (part "C"))
    )
    (comp (ref "C165")
      (value "10P")
      (footprint "C0402_L")
      (description "贴片电容/MLCC电容")
      (libsource (lib "0.1 - 电阻-电容-电感-保险丝-晶振-晶体-磁珠-电位器-法拉电容-馈通电容") (part "C"))
    )
    (comp (ref "C166")
      (value "220P")
      (footprint "C0402_L")
      (description "贴片电容/MLCC电容")
      (libsource (lib "0.1 - 电阻-电容-电感-保险丝-晶振-晶体-磁珠-电位器-法拉电容-馈通电容") (part "C"))
    )
    (comp (ref "C167")
      (value "220P")
      (footprint "C0402_L")
      (description "贴片电容/MLCC电容")
      (libsource (lib "0.1 - 电阻-电容-电感-保险丝-晶振-晶体-磁珠-电位器-法拉电容-馈通电容") (part "C"))
    )
    (comp (ref "C168")
      (value "220P")
      (footprint "C0402_L")
      (description "贴片电容/MLCC电容")
      (libsource (lib "0.1 - 电阻-电容-电感-保险丝-晶振-晶体-磁珠-电位器-法拉电容-馈通电容") (part "C"))
    )
    (comp (ref "C169")
      (value "220P")
      (footprint "C0402_L")
      (description "贴片电容/MLCC电容")
      (libsource (lib "0.1 - 电阻-电容-电感-保险丝-晶振-晶体-磁珠-电位器-法拉电容-馈通电容") (part "C"))
    )
    (comp (ref "C170")
      (value "104")
      (footprint "C0402_L")
      (description "贴片电容/MLCC电容")
      (libsource (lib "0.1 - 电阻-电容-电感-保险丝-晶振-晶体-磁珠-电位器-法拉电容-馈通电容") (part "C"))
    )
    (comp (ref "C171")
      (value "104")
      (footprint "C0402_L")
      (description "贴片电容/MLCC电容")
      (libsource (lib "0.1 - 电阻-电容-电感-保险丝-晶振-晶体-磁珠-电位器-法拉电容-馈通电容") (part "C"))
    )
    (comp (ref "C172")
      (value "104")
      (footprint "C0402_L")
      (description "贴片电容/MLCC电容")
      (libsource (lib "0.1 - 电阻-电容-电感-保险丝-晶振-晶体-磁珠-电位器-法拉电容-馈通电容") (part "C"))
    )
    (comp (ref "C173")
      (value "104")
      (footprint "C0402_L")
      (description "贴片电容/MLCC电容")
      (libsource (lib "0.1 - 电阻-电容-电感-保险丝-晶振-晶体-磁珠-电位器-法拉电容-馈通电容") (part "C"))
    )
    (comp (ref "C174")
      (value "104")
      (footprint "C0402_L")
      (description "贴片电容/MLCC电容")
      (libsource (lib "0.1 - 电阻-电容-电感-保险丝-晶振-晶体-磁珠-电位器-法拉电容-馈通电容") (part "C"))
    )
    (comp (ref "C175")
      (value "104")
      (footprint "C0402_L")
      (description "贴片电容/MLCC电容")
      (libsource (lib "0.1 - 电阻-电容-电感-保险丝-晶振-晶体-磁珠-电位器-法拉电容-馈通电容") (part "C"))
    )
    (comp (ref "C176")
      (value "104")
      (footprint "C0402_L")
      (description "贴片电容/MLCC电容")
      (libsource (lib "0.1 - 电阻-电容-电感-保险丝-晶振-晶体-磁珠-电位器-法拉电容-馈通电容") (part "C"))
    )
    (comp (ref "C177")
      (value "104")
      (footprint "C0402_L")
      (description "贴片电容/MLCC电容")
      (libsource (lib "0.1 - 电阻-电容-电感-保险丝-晶振-晶体-磁珠-电位器-法拉电容-馈通电容") (part "C"))
    )
    (comp (ref "C178")
      (value "10P")
      (footprint "C0402_L")
      (description "贴片电容/MLCC电容")
      (libsource (lib "0.1 - 电阻-电容-电感-保险丝-晶振-晶体-磁珠-电位器-法拉电容-馈通电容") (part "C"))
    )
    (comp (ref "C179")
      (value "10P")
      (footprint "C0402_L")
      (description "贴片电容/MLCC电容")
      (libsource (lib "0.1 - 电阻-电容-电感-保险丝-晶振-晶体-磁珠-电位器-法拉电容-馈通电容") (part "C"))
    )
    (comp (ref "C180")
      (value "10P")
      (footprint "C0402_L")
      (description "贴片电容/MLCC电容")
      (libsource (lib "0.1 - 电阻-电容-电感-保险丝-晶振-晶体-磁珠-电位器-法拉电容-馈通电容") (part "C"))
    )
    (comp (ref "C181")
      (value "10P")
      (footprint "C0402_L")
      (description "贴片电容/MLCC电容")
      (libsource (lib "0.1 - 电阻-电容-电感-保险丝-晶振-晶体-磁珠-电位器-法拉电容-馈通电容") (part "C"))
    )
    (comp (ref "C182")
      (value "220P")
      (footprint "C0402_L")
      (description "贴片电容/MLCC电容")
      (libsource (lib "0.1 - 电阻-电容-电感-保险丝-晶振-晶体-磁珠-电位器-法拉电容-馈通电容") (part "C"))
    )
    (comp (ref "C183")
      (value "220P")
      (footprint "C0402_L")
      (description "贴片电容/MLCC电容")
      (libsource (lib "0.1 - 电阻-电容-电感-保险丝-晶振-晶体-磁珠-电位器-法拉电容-馈通电容") (part "C"))
    )
    (comp (ref "C184")
      (value "220P")
      (footprint "C0402_L")
      (description "贴片电容/MLCC电容")
      (libsource (lib "0.1 - 电阻-电容-电感-保险丝-晶振-晶体-磁珠-电位器-法拉电容-馈通电容") (part "C"))
    )
    (comp (ref "C185")
      (value "220P")
      (footprint "C0402_L")
      (description "贴片电容/MLCC电容")
      (libsource (lib "0.1 - 电阻-电容-电感-保险丝-晶振-晶体-磁珠-电位器-法拉电容-馈通电容") (part "C"))
    )
    (comp (ref "C186")
      (value "104")
      (footprint "C0402_L")
      (description "贴片电容/MLCC电容")
      (libsource (lib "0.1 - 电阻-电容-电感-保险丝-晶振-晶体-磁珠-电位器-法拉电容-馈通电容") (part "C"))
    )
    (comp (ref "C187")
      (value "104")
      (footprint "C0402_L")
      (description "贴片电容/MLCC电容")
      (libsource (lib "0.1 - 电阻-电容-电感-保险丝-晶振-晶体-磁珠-电位器-法拉电容-馈通电容") (part "C"))
    )
    (comp (ref "C188")
      (value "104")
      (footprint "C0402_L")
      (description "贴片电容/MLCC电容")
      (libsource (lib "0.1 - 电阻-电容-电感-保险丝-晶振-晶体-磁珠-电位器-法拉电容-馈通电容") (part "C"))
    )
    (comp (ref "C189")
      (value "104")
      (footprint "C0402_L")
      (description "贴片电容/MLCC电容")
      (libsource (lib "0.1 - 电阻-电容-电感-保险丝-晶振-晶体-磁珠-电位器-法拉电容-馈通电容") (part "C"))
    )
    (comp (ref "C190")
      (value "104")
      (footprint "C0402_L")
      (description "贴片电容/MLCC电容")
      (libsource (lib "0.1 - 电阻-电容-电感-保险丝-晶振-晶体-磁珠-电位器-法拉电容-馈通电容") (part "C"))
    )
    (comp (ref "C191")
      (value "104")
      (footprint "C0402_L")
      (description "贴片电容/MLCC电容")
      (libsource (lib "0.1 - 电阻-电容-电感-保险丝-晶振-晶体-磁珠-电位器-法拉电容-馈通电容") (part "C"))
    )
    (comp (ref "C192")
      (value "104")
      (footprint "C0402_L")
      (description "贴片电容/MLCC电容")
      (libsource (lib "0.1 - 电阻-电容-电感-保险丝-晶振-晶体-磁珠-电位器-法拉电容-馈通电容") (part "C"))
    )
    (comp (ref "C193")
      (value "104")
      (footprint "C0402_L")
      (description "贴片电容/MLCC电容")
      (libsource (lib "0.1 - 电阻-电容-电感-保险丝-晶振-晶体-磁珠-电位器-法拉电容-馈通电容") (part "C"))
    )
    (comp (ref "C194")
      (value "10P")
      (footprint "C0402_L")
      (description "贴片电容/MLCC电容")
      (libsource (lib "0.1 - 电阻-电容-电感-保险丝-晶振-晶体-磁珠-电位器-法拉电容-馈通电容") (part "C"))
    )
    (comp (ref "C195")
      (value "220P")
      (footprint "C0402_L")
      (description "贴片电容/MLCC电容")
      (libsource (lib "0.1 - 电阻-电容-电感-保险丝-晶振-晶体-磁珠-电位器-法拉电容-馈通电容") (part "C"))
    )
    (comp (ref "C196")
      (value "104")
      (footprint "C0402_L")
      (description "贴片电容/MLCC电容")
      (libsource (lib "0.1 - 电阻-电容-电感-保险丝-晶振-晶体-磁珠-电位器-法拉电容-馈通电容") (part "C"))
    )
    (comp (ref "C197")
      (value "104")
      (footprint "C0402_L")
      (description "贴片电容/MLCC电容")
      (libsource (lib "0.1 - 电阻-电容-电感-保险丝-晶振-晶体-磁珠-电位器-法拉电容-馈通电容") (part "C"))
    )
    (comp (ref "P9") (value "PD") (footprint "PD") (libsource (lib "LTC2325_2311_COMS") (part "PD")))
    (comp (ref "PW1") (value "PD") (footprint "PD") (libsource (lib "LTC2325_2311_COMS") (part "PD")))
    (comp (ref "PW2") (value "PD") (footprint "PD") (libsource (lib "LTC2325_2311_COMS") (part "PD")))
    (comp (ref "PW3") (value "PD") (footprint "PD") (libsource (lib "LTC2325_2311_COMS") (part "PD")))
    (comp (ref "PW4") (value "PD") (footprint "PD") (libsource (lib "LTC2325_2311_COMS") (part "PD")))
    (comp (ref "PX1") (value "PD") (footprint "PD") (libsource (lib "LTC2325_2311_COMS") (part "PD")))
    (comp (ref "PX2") (value "PD") (footprint "PD") (libsource (lib "LTC2325_2311_COMS") (part "PD")))
    (comp (ref "PX3") (value "PD") (footprint "PD") (libsource (lib "LTC2325_2311_COMS") (part "PD")))
    (comp (ref "PX4") (value "PD") (footprint "PD") (libsource (lib "LTC2325_2311_COMS") (part "PD")))
    (comp (ref "PY1") (value "PD") (footprint "PD") (libsource (lib "LTC2325_2311_COMS") (part "PD")))
    (comp (ref "PY2") (value "PD") (footprint "PD") (libsource (lib "LTC2325_2311_COMS") (part "PD")))
    (comp (ref "PY3") (value "PD") (footprint "PD") (libsource (lib "LTC2325_2311_COMS") (part "PD")))
    (comp (ref "PY4") (value "PD") (footprint "PD") (libsource (lib "LTC2325_2311_COMS") (part "PD")))
    (comp (ref "PZ1") (value "PD") (footprint "PD") (libsource (lib "LTC2325_2311_COMS") (part "PD")))
    (comp (ref "PZ2") (value "PD") (footprint "PD") (libsource (lib "LTC2325_2311_COMS") (part "PD")))
    (comp (ref "PZ3") (value "PD") (footprint "PD") (libsource (lib "LTC2325_2311_COMS") (part "PD")))
    (comp (ref "PZ4") (value "PD") (footprint "PD") (libsource (lib "LTC2325_2311_COMS") (part "PD")))
    (comp (ref "R51")
      (value "33R")
      (footprint "RCA-8P4R-0402")
      (description "贴片4P排阻")
      (libsource (lib "0.1 - 电阻-电容-电感-保险丝-晶振-晶体-磁珠-电位器-法拉电容-馈通电容") (part "R-8P4R"))
    )
    (comp (ref "R52")
      (value "33R")
      (footprint "RCA-8P4R-0402")
      (description "贴片4P排阻")
      (libsource (lib "0.1 - 电阻-电容-电感-保险丝-晶振-晶体-磁珠-电位器-法拉电容-馈通电容") (part "R-8P4R"))
    )
    (comp (ref "R53")
      (value "33R")
      (footprint "RCA-8P4R-0402")
      (description "贴片4P排阻")
      (libsource (lib "0.1 - 电阻-电容-电感-保险丝-晶振-晶体-磁珠-电位器-法拉电容-馈通电容") (part "R-8P4R"))
    )
    (comp (ref "R54")
      (value "33R")
      (footprint "RCA-8P4R-0402")
      (description "贴片4P排阻")
      (libsource (lib "0.1 - 电阻-电容-电感-保险丝-晶振-晶体-磁珠-电位器-法拉电容-馈通电容") (part "R-8P4R"))
    )
    (comp (ref "R55")
      (value "33R")
      (footprint "RCA-8P4R-0402")
      (description "贴片4P排阻")
      (libsource (lib "0.1 - 电阻-电容-电感-保险丝-晶振-晶体-磁珠-电位器-法拉电容-馈通电容") (part "R-8P4R"))
    )
    (comp (ref "R56")
      (value "33R")
      (footprint "RCA-8P4R-0402")
      (description "贴片4P排阻")
      (libsource (lib "0.1 - 电阻-电容-电感-保险丝-晶振-晶体-磁珠-电位器-法拉电容-馈通电容") (part "R-8P4R"))
    )
    (comp (ref "R57")
      (value "33R")
      (footprint "RCA-8P4R-0402")
      (description "贴片4P排阻")
      (libsource (lib "0.1 - 电阻-电容-电感-保险丝-晶振-晶体-磁珠-电位器-法拉电容-馈通电容") (part "R-8P4R"))
    )
    (comp (ref "R58")
      (value "0R")
      (footprint "R0402_L")
      (description "贴片电阻")
      (libsource (lib "0.1 - 电阻-电容-电感-保险丝-晶振-晶体-磁珠-电位器-法拉电容-馈通电容") (part "R"))
    )
    (comp (ref "R59")
      (value "33R")
      (footprint "RCA-8P4R-0402")
      (description "贴片4P排阻")
      (libsource (lib "0.1 - 电阻-电容-电感-保险丝-晶振-晶体-磁珠-电位器-法拉电容-馈通电容") (part "R-8P4R"))
    )
    (comp (ref "R60")
      (value "33R")
      (footprint "RCA-8P4R-0402")
      (description "贴片4P排阻")
      (libsource (lib "0.1 - 电阻-电容-电感-保险丝-晶振-晶体-磁珠-电位器-法拉电容-馈通电容") (part "R-8P4R"))
    )
    (comp (ref "R61")
      (value "200K 1%")
      (footprint "R0402_L")
      (description "贴片电阻")
      (libsource (lib "0.1 - 电阻-电容-电感-保险丝-晶振-晶体-磁珠-电位器-法拉电容-馈通电容") (part "R"))
    )
    (comp (ref "R62")
      (value "200K 1%")
      (footprint "R0402_L")
      (description "贴片电阻")
      (libsource (lib "0.1 - 电阻-电容-电感-保险丝-晶振-晶体-磁珠-电位器-法拉电容-馈通电容") (part "R"))
    )
    (comp (ref "R63")
      (value "200K 1%")
      (footprint "R0402_L")
      (description "贴片电阻")
      (libsource (lib "0.1 - 电阻-电容-电感-保险丝-晶振-晶体-磁珠-电位器-法拉电容-馈通电容") (part "R"))
    )
    (comp (ref "R64")
      (value "200K 1%")
      (footprint "R0402_L")
      (description "贴片电阻")
      (libsource (lib "0.1 - 电阻-电容-电感-保险丝-晶振-晶体-磁珠-电位器-法拉电容-馈通电容") (part "R"))
    )
    (comp (ref "R65")
      (value "25R 1%")
      (footprint "R0402_L")
      (description "贴片电阻")
      (libsource (lib "0.1 - 电阻-电容-电感-保险丝-晶振-晶体-磁珠-电位器-法拉电容-馈通电容") (part "R"))
    )
    (comp (ref "R66")
      (value "25R 1%")
      (footprint "R0402_L")
      (description "贴片电阻")
      (libsource (lib "0.1 - 电阻-电容-电感-保险丝-晶振-晶体-磁珠-电位器-法拉电容-馈通电容") (part "R"))
    )
    (comp (ref "R67")
      (value "25R 1%")
      (footprint "R0402_L")
      (description "贴片电阻")
      (libsource (lib "0.1 - 电阻-电容-电感-保险丝-晶振-晶体-磁珠-电位器-法拉电容-馈通电容") (part "R"))
    )
    (comp (ref "R68")
      (value "25R 1%")
      (footprint "R0402_L")
      (description "贴片电阻")
      (libsource (lib "0.1 - 电阻-电容-电感-保险丝-晶振-晶体-磁珠-电位器-法拉电容-馈通电容") (part "R"))
    )
    (comp (ref "R69")
      (value "25R 1%")
      (footprint "R0402_L")
      (description "贴片电阻")
      (libsource (lib "0.1 - 电阻-电容-电感-保险丝-晶振-晶体-磁珠-电位器-法拉电容-馈通电容") (part "R"))
    )
    (comp (ref "R70")
      (value "25R 1%")
      (footprint "R0402_L")
      (description "贴片电阻")
      (libsource (lib "0.1 - 电阻-电容-电感-保险丝-晶振-晶体-磁珠-电位器-法拉电容-馈通电容") (part "R"))
    )
    (comp (ref "R71")
      (value "25R 1%")
      (footprint "R0402_L")
      (description "贴片电阻")
      (libsource (lib "0.1 - 电阻-电容-电感-保险丝-晶振-晶体-磁珠-电位器-法拉电容-馈通电容") (part "R"))
    )
    (comp (ref "R72")
      (value "25R 1%")
      (footprint "R0402_L")
      (description "贴片电阻")
      (libsource (lib "0.1 - 电阻-电容-电感-保险丝-晶振-晶体-磁珠-电位器-法拉电容-馈通电容") (part "R"))
    )
    (comp (ref "R73")
      (value "200K 1%")
      (footprint "R0402_L")
      (description "贴片电阻")
      (libsource (lib "0.1 - 电阻-电容-电感-保险丝-晶振-晶体-磁珠-电位器-法拉电容-馈通电容") (part "R"))
    )
    (comp (ref "R74")
      (value "200K 1%")
      (footprint "R0402_L")
      (description "贴片电阻")
      (libsource (lib "0.1 - 电阻-电容-电感-保险丝-晶振-晶体-磁珠-电位器-法拉电容-馈通电容") (part "R"))
    )
    (comp (ref "R75")
      (value "200K 1%")
      (footprint "R0402_L")
      (description "贴片电阻")
      (libsource (lib "0.1 - 电阻-电容-电感-保险丝-晶振-晶体-磁珠-电位器-法拉电容-馈通电容") (part "R"))
    )
    (comp (ref "R76")
      (value "200K 1%")
      (footprint "R0402_L")
      (description "贴片电阻")
      (libsource (lib "0.1 - 电阻-电容-电感-保险丝-晶振-晶体-磁珠-电位器-法拉电容-馈通电容") (part "R"))
    )
    (comp (ref "R77")
      (value "25R 1%")
      (footprint "R0402_L")
      (description "贴片电阻")
      (libsource (lib "0.1 - 电阻-电容-电感-保险丝-晶振-晶体-磁珠-电位器-法拉电容-馈通电容") (part "R"))
    )
    (comp (ref "R78")
      (value "25R 1%")
      (footprint "R0402_L")
      (description "贴片电阻")
      (libsource (lib "0.1 - 电阻-电容-电感-保险丝-晶振-晶体-磁珠-电位器-法拉电容-馈通电容") (part "R"))
    )
    (comp (ref "R79")
      (value "25R 1%")
      (footprint "R0402_L")
      (description "贴片电阻")
      (libsource (lib "0.1 - 电阻-电容-电感-保险丝-晶振-晶体-磁珠-电位器-法拉电容-馈通电容") (part "R"))
    )
    (comp (ref "R80")
      (value "25R 1%")
      (footprint "R0402_L")
      (description "贴片电阻")
      (libsource (lib "0.1 - 电阻-电容-电感-保险丝-晶振-晶体-磁珠-电位器-法拉电容-馈通电容") (part "R"))
    )
    (comp (ref "R81")
      (value "25R 1%")
      (footprint "R0402_L")
      (description "贴片电阻")
      (libsource (lib "0.1 - 电阻-电容-电感-保险丝-晶振-晶体-磁珠-电位器-法拉电容-馈通电容") (part "R"))
    )
    (comp (ref "R82")
      (value "25R 1%")
      (footprint "R0402_L")
      (description "贴片电阻")
      (libsource (lib "0.1 - 电阻-电容-电感-保险丝-晶振-晶体-磁珠-电位器-法拉电容-馈通电容") (part "R"))
    )
    (comp (ref "R83")
      (value "25R 1%")
      (footprint "R0402_L")
      (description "贴片电阻")
      (libsource (lib "0.1 - 电阻-电容-电感-保险丝-晶振-晶体-磁珠-电位器-法拉电容-馈通电容") (part "R"))
    )
    (comp (ref "R84")
      (value "25R 1%")
      (footprint "R0402_L")
      (description "贴片电阻")
      (libsource (lib "0.1 - 电阻-电容-电感-保险丝-晶振-晶体-磁珠-电位器-法拉电容-馈通电容") (part "R"))
    )
    (comp (ref "R85")
      (value "200K 1%")
      (footprint "R0402_L")
      (description "贴片电阻")
      (libsource (lib "0.1 - 电阻-电容-电感-保险丝-晶振-晶体-磁珠-电位器-法拉电容-馈通电容") (part "R"))
    )
    (comp (ref "R86")
      (value "200K 1%")
      (footprint "R0402_L")
      (description "贴片电阻")
      (libsource (lib "0.1 - 电阻-电容-电感-保险丝-晶振-晶体-磁珠-电位器-法拉电容-馈通电容") (part "R"))
    )
    (comp (ref "R87")
      (value "200K 1%")
      (footprint "R0402_L")
      (description "贴片电阻")
      (libsource (lib "0.1 - 电阻-电容-电感-保险丝-晶振-晶体-磁珠-电位器-法拉电容-馈通电容") (part "R"))
    )
    (comp (ref "R88")
      (value "200K 1%")
      (footprint "R0402_L")
      (description "贴片电阻")
      (libsource (lib "0.1 - 电阻-电容-电感-保险丝-晶振-晶体-磁珠-电位器-法拉电容-馈通电容") (part "R"))
    )
    (comp (ref "R89")
      (value "25R 1%")
      (footprint "R0402_L")
      (description "贴片电阻")
      (libsource (lib "0.1 - 电阻-电容-电感-保险丝-晶振-晶体-磁珠-电位器-法拉电容-馈通电容") (part "R"))
    )
    (comp (ref "R90")
      (value "25R 1%")
      (footprint "R0402_L")
      (description "贴片电阻")
      (libsource (lib "0.1 - 电阻-电容-电感-保险丝-晶振-晶体-磁珠-电位器-法拉电容-馈通电容") (part "R"))
    )
    (comp (ref "R91")
      (value "25R 1%")
      (footprint "R0402_L")
      (description "贴片电阻")
      (libsource (lib "0.1 - 电阻-电容-电感-保险丝-晶振-晶体-磁珠-电位器-法拉电容-馈通电容") (part "R"))
    )
    (comp (ref "R92")
      (value "25R 1%")
      (footprint "R0402_L")
      (description "贴片电阻")
      (libsource (lib "0.1 - 电阻-电容-电感-保险丝-晶振-晶体-磁珠-电位器-法拉电容-馈通电容") (part "R"))
    )
    (comp (ref "R93")
      (value "25R 1%")
      (footprint "R0402_L")
      (description "贴片电阻")
      (libsource (lib "0.1 - 电阻-电容-电感-保险丝-晶振-晶体-磁珠-电位器-法拉电容-馈通电容") (part "R"))
    )
    (comp (ref "R94")
      (value "25R 1%")
      (footprint "R0402_L")
      (description "贴片电阻")
      (libsource (lib "0.1 - 电阻-电容-电感-保险丝-晶振-晶体-磁珠-电位器-法拉电容-馈通电容") (part "R"))
    )
    (comp (ref "R95")
      (value "25R 1%")
      (footprint "R0402_L")
      (description "贴片电阻")
      (libsource (lib "0.1 - 电阻-电容-电感-保险丝-晶振-晶体-磁珠-电位器-法拉电容-馈通电容") (part "R"))
    )
    (comp (ref "R96")
      (value "25R 1%")
      (footprint "R0402_L")
      (description "贴片电阻")
      (libsource (lib "0.1 - 电阻-电容-电感-保险丝-晶振-晶体-磁珠-电位器-法拉电容-馈通电容") (part "R"))
    )
    (comp (ref "R97")
      (value "200K 1%")
      (footprint "R0402_L")
      (description "贴片电阻")
      (libsource (lib "0.1 - 电阻-电容-电感-保险丝-晶振-晶体-磁珠-电位器-法拉电容-馈通电容") (part "R"))
    )
    (comp (ref "R98")
      (value "200K 1%")
      (footprint "R0402_L")
      (description "贴片电阻")
      (libsource (lib "0.1 - 电阻-电容-电感-保险丝-晶振-晶体-磁珠-电位器-法拉电容-馈通电容") (part "R"))
    )
    (comp (ref "R99")
      (value "200K 1%")
      (footprint "R0402_L")
      (description "贴片电阻")
      (libsource (lib "0.1 - 电阻-电容-电感-保险丝-晶振-晶体-磁珠-电位器-法拉电容-馈通电容") (part "R"))
    )
    (comp (ref "R100")
      (value "200K 1%")
      (footprint "R0402_L")
      (description "贴片电阻")
      (libsource (lib "0.1 - 电阻-电容-电感-保险丝-晶振-晶体-磁珠-电位器-法拉电容-馈通电容") (part "R"))
    )
    (comp (ref "R101")
      (value "25R 1%")
      (footprint "R0402_L")
      (description "贴片电阻")
      (libsource (lib "0.1 - 电阻-电容-电感-保险丝-晶振-晶体-磁珠-电位器-法拉电容-馈通电容") (part "R"))
    )
    (comp (ref "R102")
      (value "25R 1%")
      (footprint "R0402_L")
      (description "贴片电阻")
      (libsource (lib "0.1 - 电阻-电容-电感-保险丝-晶振-晶体-磁珠-电位器-法拉电容-馈通电容") (part "R"))
    )
    (comp (ref "R103")
      (value "25R 1%")
      (footprint "R0402_L")
      (description "贴片电阻")
      (libsource (lib "0.1 - 电阻-电容-电感-保险丝-晶振-晶体-磁珠-电位器-法拉电容-馈通电容") (part "R"))
    )
    (comp (ref "R104")
      (value "25R 1%")
      (footprint "R0402_L")
      (description "贴片电阻")
      (libsource (lib "0.1 - 电阻-电容-电感-保险丝-晶振-晶体-磁珠-电位器-法拉电容-馈通电容") (part "R"))
    )
    (comp (ref "R105")
      (value "25R 1%")
      (footprint "R0402_L")
      (description "贴片电阻")
      (libsource (lib "0.1 - 电阻-电容-电感-保险丝-晶振-晶体-磁珠-电位器-法拉电容-馈通电容") (part "R"))
    )
    (comp (ref "R106")
      (value "25R 1%")
      (footprint "R0402_L")
      (description "贴片电阻")
      (libsource (lib "0.1 - 电阻-电容-电感-保险丝-晶振-晶体-磁珠-电位器-法拉电容-馈通电容") (part "R"))
    )
    (comp (ref "R107")
      (value "25R 1%")
      (footprint "R0402_L")
      (description "贴片电阻")
      (libsource (lib "0.1 - 电阻-电容-电感-保险丝-晶振-晶体-磁珠-电位器-法拉电容-馈通电容") (part "R"))
    )
    (comp (ref "R108")
      (value "25R 1%")
      (footprint "R0402_L")
      (description "贴片电阻")
      (libsource (lib "0.1 - 电阻-电容-电感-保险丝-晶振-晶体-磁珠-电位器-法拉电容-馈通电容") (part "R"))
    )
    (comp (ref "R109")
      (value "200K 1%")
      (footprint "R0402_L")
      (description "贴片电阻")
      (libsource (lib "0.1 - 电阻-电容-电感-保险丝-晶振-晶体-磁珠-电位器-法拉电容-馈通电容") (part "R"))
    )
    (comp (ref "R110")
      (value "25R 1%")
      (footprint "R0402_L")
      (description "贴片电阻")
      (libsource (lib "0.1 - 电阻-电容-电感-保险丝-晶振-晶体-磁珠-电位器-法拉电容-馈通电容") (part "R"))
    )
    (comp (ref "R111")
      (value "25R 1%")
      (footprint "R0402_L")
      (description "贴片电阻")
      (libsource (lib "0.1 - 电阻-电容-电感-保险丝-晶振-晶体-磁珠-电位器-法拉电容-馈通电容") (part "R"))
    )
    (comp (ref "U15")
      (value "LTC2325HUKG-16PBF")
      (footprint "UKG_52A_ADI")
      (description "No Description Available")
      (libsource (lib "LTC2325HUKG-16PBF") (part "LTC2325HUKG-16PBF"))
    )
    (comp (ref "U16")
      (value "LTC2325HUKG-16PBF")
      (footprint "UKG_52A_ADI")
      (description "No Description Available")
      (libsource (lib "LTC2325HUKG-16PBF") (part "LTC2325HUKG-16PBF"))
    )
    (comp (ref "U17")
      (value "LTC2325HUKG-16PBF")
      (footprint "UKG_52A_ADI")
      (description "No Description Available")
      (libsource (lib "LTC2325HUKG-16PBF") (part "LTC2325HUKG-16PBF"))
    )
    (comp (ref "U18")
      (value "LTC2325HUKG-16PBF")
      (footprint "UKG_52A_ADI")
      (description "No Description Available")
      (libsource (lib "LTC2325HUKG-16PBF") (part "LTC2325HUKG-16PBF"))
    )
    (comp (ref "U19")
      (value "LTC2311HMSE-16PBF")
      (footprint "MSE_16_ADI")
      (description "No Description Available")
      (libsource (lib "LTC2311HMSE-16PBF") (part "LTC2311HMSE-16PBF"))
    )
    (comp (ref "U20")
      (value "REF1933AIDDCT")
      (footprint "DDC5_TEX")
      (description "No Description Available")
      (libsource (lib "REF1925AIDDCT") (part "REF1925AIDDCT"))
    )
    (comp (ref "U21")
      (value "REF1933AIDDCT")
      (footprint "DDC5_TEX")
      (description "No Description Available")
      (libsource (lib "REF1925AIDDCT") (part "REF1925AIDDCT"))
    )
    (comp (ref "U22")
      (value "REF1933AIDDCT")
      (footprint "DDC5_TEX")
      (description "No Description Available")
      (libsource (lib "REF1925AIDDCT") (part "REF1925AIDDCT"))
    )
    (comp (ref "U23")
      (value "REF1933AIDDCT")
      (footprint "DDC5_TEX")
      (description "No Description Available")
      (libsource (lib "REF1925AIDDCT") (part "REF1925AIDDCT"))
    )
    (comp (ref "U24")
      (value "REF1933AIDDCT")
      (footprint "DDC5_TEX")
      (description "No Description Available")
      (libsource (lib "REF1925AIDDCT") (part "REF1925AIDDCT"))
    )
    (comp (ref "U25")
      (value "OPA862IDR")
      (footprint "SOIC-8")
      (description "No Description Available")
      (libsource (lib "OPA862IDR") (part "OPA862IDR"))
    )
    (comp (ref "U26")
      (value "OPA862IDR")
      (footprint "SOIC-8")
      (description "No Description Available")
      (libsource (lib "OPA862IDR") (part "OPA862IDR"))
    )
    (comp (ref "U27")
      (value "OPA862IDR")
      (footprint "SOIC-8")
      (description "No Description Available")
      (libsource (lib "OPA862IDR") (part "OPA862IDR"))
    )
    (comp (ref "U28")
      (value "OPA862IDR")
      (footprint "SOIC-8")
      (description "No Description Available")
      (libsource (lib "OPA862IDR") (part "OPA862IDR"))
    )
    (comp (ref "U29")
      (value "OPA862IDR")
      (footprint "SOIC-8")
      (description "No Description Available")
      (libsource (lib "OPA862IDR") (part "OPA862IDR"))
    )
    (comp (ref "U30")
      (value "OPA862IDR")
      (footprint "SOIC-8")
      (description "No Description Available")
      (libsource (lib "OPA862IDR") (part "OPA862IDR"))
    )
    (comp (ref "U31")
      (value "OPA862IDR")
      (footprint "SOIC-8")
      (description "No Description Available")
      (libsource (lib "OPA862IDR") (part "OPA862IDR"))
    )
    (comp (ref "U32")
      (value "OPA862IDR")
      (footprint "SOIC-8")
      (description "No Description Available")
      (libsource (lib "OPA862IDR") (part "OPA862IDR"))
    )
    (comp (ref "U33")
      (value "OPA862IDR")
      (footprint "SOIC-8")
      (description "No Description Available")
      (libsource (lib "OPA862IDR") (part "OPA862IDR"))
    )
    (comp (ref "U34")
      (value "OPA862IDR")
      (footprint "SOIC-8")
      (description "No Description Available")
      (libsource (lib "OPA862IDR") (part "OPA862IDR"))
    )
    (comp (ref "U35")
      (value "OPA862IDR")
      (footprint "SOIC-8")
      (description "No Description Available")
      (libsource (lib "OPA862IDR") (part "OPA862IDR"))
    )
    (comp (ref "U36")
      (value "OPA862IDR")
      (footprint "SOIC-8")
      (description "No Description Available")
      (libsource (lib "OPA862IDR") (part "OPA862IDR"))
    )
    (comp (ref "U37")
      (value "OPA862IDR")
      (footprint "SOIC-8")
      (description "No Description Available")
      (libsource (lib "OPA862IDR") (part "OPA862IDR"))
    )
    (comp (ref "U38")
      (value "OPA862IDR")
      (footprint "SOIC-8")
      (description "No Description Available")
      (libsource (lib "OPA862IDR") (part "OPA862IDR"))
    )
    (comp (ref "U39")
      (value "OPA862IDR")
      (footprint "SOIC-8")
      (description "No Description Available")
      (libsource (lib "OPA862IDR") (part "OPA862IDR"))
    )
    (comp (ref "U40")
      (value "OPA862IDR")
      (footprint "SOIC-8")
      (description "No Description Available")
      (libsource (lib "OPA862IDR") (part "OPA862IDR"))
    )
    (comp (ref "U41")
      (value "OPA862IDR")
      (footprint "SOIC-8")
      (description "No Description Available")
      (libsource (lib "OPA862IDR") (part "OPA862IDR"))
    )
  )
  (nets
    (net (code "1") (name "+A3V3_PD") (class "Default")
      (node (ref "C100") (pin "1") (pinfunction "1_1") (pintype "passive"))
      (node (ref "C101") (pin "1") (pinfunction "1_1") (pintype "passive"))
      (node (ref "C102") (pin "1") (pinfunction "1_1") (pintype "passive"))
      (node (ref "C103") (pin "1") (pinfunction "1_1") (pintype "passive"))
      (node (ref "C106") (pin "1") (pinfunction "1_1") (pintype "passive"))
      (node (ref "C107") (pin "1") (pinfunction "1_1") (pintype "passive"))
      (node (ref "C108") (pin "1") (pinfunction "1_1") (pintype "passive"))
      (node (ref "C109") (pin "1") (pinfunction "1_1") (pintype "passive"))
      (node (ref "C110") (pin "1") (pinfunction "1_1") (pintype "passive"))
      (node (ref "C111") (pin "1") (pinfunction "1_1") (pintype "passive"))
      (node (ref "C112") (pin "1") (pinfunction "1_1") (pintype "passive"))
      (node (ref "C113") (pin "1") (pinfunction "1_1") (pintype "passive"))
      (node (ref "C58") (pin "1") (pinfunction "1_1") (pintype "passive"))
      (node (ref "C67") (pin "1") (pinfunction "1_1") (pintype "passive"))
      (node (ref "C68") (pin "1") (pinfunction "1_1") (pintype "passive"))
      (node (ref "C69") (pin "1") (pinfunction "1_1") (pintype "passive"))
      (node (ref "C70") (pin "1") (pinfunction "1_1") (pintype "passive"))
      (node (ref "C71") (pin "1") (pinfunction "1_1") (pintype "passive"))
      (node (ref "C72") (pin "1") (pinfunction "1_1") (pintype "passive"))
      (node (ref "C73") (pin "1") (pinfunction "1_1") (pintype "passive"))
      (node (ref "C74") (pin "1") (pinfunction "1_1") (pintype "passive"))
      (node (ref "C77") (pin "1") (pinfunction "1_1") (pintype "passive"))
      (node (ref "C78") (pin "1") (pinfunction "1_1") (pintype "passive"))
      (node (ref "C79") (pin "1") (pinfunction "1_1") (pintype "passive"))
      (node (ref "C80") (pin "1") (pinfunction "1_1") (pintype "passive"))
      (node (ref "C81") (pin "1") (pinfunction "1_1") (pintype "passive"))
      (node (ref "C82") (pin "1") (pinfunction "1_1") (pintype "passive"))
      (node (ref "C83") (pin "1") (pinfunction "1_1") (pintype "passive"))
      (node (ref "C84") (pin "1") (pinfunction "1_1") (pintype "passive"))
      (node (ref "C96") (pin "1") (pinfunction "1_1") (pintype "passive"))
      (node (ref "C97") (pin "1") (pinfunction "1_1") (pintype "passive"))
      (node (ref "C98") (pin "1") (pinfunction "1_1") (pintype "passive"))
      (node (ref "C99") (pin "1") (pinfunction "1_1") (pintype "passive"))
      (node (ref "U15") (pin "15") (pinfunction "VDD_15") (pintype "passive"))
      (node (ref "U15") (pin "21") (pinfunction "VDD_21") (pintype "passive"))
      (node (ref "U15") (pin "43") (pinfunction "REFBUFEN_43") (pintype "passive"))
      (node (ref "U15") (pin "44") (pinfunction "VDD_44") (pintype "passive"))
      (node (ref "U15") (pin "52") (pinfunction "VDD_52") (pintype "passive"))
      (node (ref "U16") (pin "15") (pinfunction "VDD_15") (pintype "passive"))
      (node (ref "U16") (pin "21") (pinfunction "VDD_21") (pintype "passive"))
      (node (ref "U16") (pin "43") (pinfunction "REFBUFEN_43") (pintype "passive"))
      (node (ref "U16") (pin "44") (pinfunction "VDD_44") (pintype "passive"))
      (node (ref "U16") (pin "52") (pinfunction "VDD_52") (pintype "passive"))
      (node (ref "U17") (pin "15") (pinfunction "VDD_15") (pintype "passive"))
      (node (ref "U17") (pin "21") (pinfunction "VDD_21") (pintype "passive"))
      (node (ref "U17") (pin "43") (pinfunction "REFBUFEN_43") (pintype "passive"))
      (node (ref "U17") (pin "44") (pinfunction "VDD_44") (pintype "passive"))
      (node (ref "U17") (pin "52") (pinfunction "VDD_52") (pintype "passive"))
      (node (ref "U18") (pin "15") (pinfunction "VDD_15") (pintype "passive"))
      (node (ref "U18") (pin "21") (pinfunction "VDD_21") (pintype "passive"))
      (node (ref "U18") (pin "43") (pinfunction "REFBUFEN_43") (pintype "passive"))
      (node (ref "U18") (pin "44") (pinfunction "VDD_44") (pintype "passive"))
      (node (ref "U18") (pin "52") (pinfunction "VDD_52") (pintype "passive"))
      (node (ref "U19") (pin "4") (pinfunction "VDD_4") (pintype "power_in"))
    )
    (net (code "2") (name "+A4_PD") (class "Default")
      (node (ref "C138") (pin "1") (pinfunction "1_1") (pintype "passive"))
      (node (ref "C140") (pin "1") (pinfunction "1_1") (pintype "passive"))
      (node (ref "C142") (pin "1") (pinfunction "1_1") (pintype "passive"))
      (node (ref "C144") (pin "1") (pinfunction "1_1") (pintype "passive"))
      (node (ref "C154") (pin "1") (pinfunction "1_1") (pintype "passive"))
      (node (ref "C156") (pin "1") (pinfunction "1_1") (pintype "passive"))
      (node (ref "C158") (pin "1") (pinfunction "1_1") (pintype "passive"))
      (node (ref "C160") (pin "1") (pinfunction "1_1") (pintype "passive"))
      (node (ref "C170") (pin "1") (pinfunction "1_1") (pintype "passive"))
      (node (ref "C172") (pin "1") (pinfunction "1_1") (pintype "passive"))
      (node (ref "C174") (pin "1") (pinfunction "1_1") (pintype "passive"))
      (node (ref "C176") (pin "1") (pinfunction "1_1") (pintype "passive"))
      (node (ref "C186") (pin "1") (pinfunction "1_1") (pintype "passive"))
      (node (ref "C188") (pin "1") (pinfunction "1_1") (pintype "passive"))
      (node (ref "C190") (pin "1") (pinfunction "1_1") (pintype "passive"))
      (node (ref "C192") (pin "1") (pinfunction "1_1") (pintype "passive"))
      (node (ref "C196") (pin "1") (pinfunction "1_1") (pintype "passive"))
      (node (ref "U25") (pin "3") (pinfunction "VS+_3") (pintype "power_in"))
      (node (ref "U26") (pin "3") (pinfunction "VS+_3") (pintype "power_in"))
      (node (ref "U27") (pin "3") (pinfunction "VS+_3") (pintype "power_in"))
      (node (ref "U28") (pin "3") (pinfunction "VS+_3") (pintype "power_in"))
      (node (ref "U29") (pin "3") (pinfunction "VS+_3") (pintype "power_in"))
      (node (ref "U30") (pin "3") (pinfunction "VS+_3") (pintype "power_in"))
      (node (ref "U31") (pin "3") (pinfunction "VS+_3") (pintype "power_in"))
      (node (ref "U32") (pin "3") (pinfunction "VS+_3") (pintype "power_in"))
      (node (ref "U33") (pin "3") (pinfunction "VS+_3") (pintype "power_in"))
      (node (ref "U34") (pin "3") (pinfunction "VS+_3") (pintype "power_in"))
      (node (ref "U35") (pin "3") (pinfunction "VS+_3") (pintype "power_in"))
      (node (ref "U36") (pin "3") (pinfunction "VS+_3") (pintype "power_in"))
      (node (ref "U37") (pin "3") (pinfunction "VS+_3") (pintype "power_in"))
      (node (ref "U38") (pin "3") (pinfunction "VS+_3") (pintype "power_in"))
      (node (ref "U39") (pin "3") (pinfunction "VS+_3") (pintype "power_in"))
      (node (ref "U40") (pin "3") (pinfunction "VS+_3") (pintype "power_in"))
      (node (ref "U41") (pin "3") (pinfunction "VS+_3") (pintype "power_in"))
    )
    (net (code "3") (name "+A5_PD") (class "Default")
      (node (ref "C120") (pin "2") (pinfunction "2_2") (pintype "passive"))
      (node (ref "C65") (pin "2") (pinfunction "2_2") (pintype "passive"))
      (node (ref "C66") (pin "2") (pinfunction "2_2") (pintype "passive"))
      (node (ref "C87") (pin "2") (pinfunction "2_2") (pintype "passive"))
      (node (ref "C88") (pin "2") (pinfunction "2_2") (pintype "passive"))
      (node (ref "U20") (pin "3") (pinfunction "EN_3") (pintype "input"))
      (node (ref "U20") (pin "4") (pinfunction "VIN_4") (pintype "input"))
      (node (ref "U21") (pin "3") (pinfunction "EN_3") (pintype "input"))
      (node (ref "U21") (pin "4") (pinfunction "VIN_4") (pintype "input"))
      (node (ref "U22") (pin "3") (pinfunction "EN_3") (pintype "input"))
      (node (ref "U22") (pin "4") (pinfunction "VIN_4") (pintype "input"))
      (node (ref "U23") (pin "3") (pinfunction "EN_3") (pintype "input"))
      (node (ref "U23") (pin "4") (pinfunction "VIN_4") (pintype "input"))
      (node (ref "U24") (pin "3") (pinfunction "EN_3") (pintype "input"))
      (node (ref "U24") (pin "4") (pinfunction "VIN_4") (pintype "input"))
    )
    (net (code "4") (name "+D2V5_PD") (class "Default")
      (node (ref "C104") (pin "1") (pinfunction "1_1") (pintype "passive"))
      (node (ref "C105") (pin "1") (pinfunction "1_1") (pintype "passive"))
      (node (ref "C114") (pin "1") (pinfunction "1_1") (pintype "passive"))
      (node (ref "C115") (pin "1") (pinfunction "1_1") (pintype "passive"))
      (node (ref "C59") (pin "1") (pinfunction "1_1") (pintype "passive"))
      (node (ref "C75") (pin "1") (pinfunction "1_1") (pintype "passive"))
      (node (ref "C76") (pin "1") (pinfunction "1_1") (pintype "passive"))
      (node (ref "C85") (pin "1") (pinfunction "1_1") (pintype "passive"))
      (node (ref "C86") (pin "1") (pinfunction "1_1") (pintype "passive"))
      (node (ref "U15") (pin "31") (pinfunction "OVDD_31") (pintype "passive"))
      (node (ref "U15") (pin "34") (pinfunction "*CLKOUTEN/CLKOUT-_34") (pintype "passive"))
      (node (ref "U15") (pin "37") (pinfunction "OVDD_37") (pintype "passive"))
      (node (ref "U16") (pin "31") (pinfunction "OVDD_31") (pintype "passive"))
      (node (ref "U16") (pin "34") (pinfunction "*CLKOUTEN/CLKOUT-_34") (pintype "passive"))
      (node (ref "U16") (pin "37") (pinfunction "OVDD_37") (pintype "passive"))
      (node (ref "U17") (pin "31") (pinfunction "OVDD_31") (pintype "passive"))
      (node (ref "U17") (pin "34") (pinfunction "*CLKOUTEN/CLKOUT-_34") (pintype "passive"))
      (node (ref "U17") (pin "37") (pinfunction "OVDD_37") (pintype "passive"))
      (node (ref "U18") (pin "31") (pinfunction "OVDD_31") (pintype "passive"))
      (node (ref "U18") (pin "34") (pinfunction "*CLKOUTEN/CLKOUT-_34") (pintype "passive"))
      (node (ref "U18") (pin "37") (pinfunction "OVDD_37") (pintype "passive"))
      (node (ref "U19") (pin "12") (pinfunction "OVDD_12") (pintype "power_in"))
    )
    (net (code "5") (name "-A4_PD") (class "Default")
      (node (ref "C139") (pin "1") (pinfunction "1_1") (pintype "passive"))
      (node (ref "C141") (pin "1") (pinfunction "1_1") (pintype "passive"))
      (node (ref "C143") (pin "1") (pinfunction "1_1") (pintype "passive"))
      (node (ref "C145") (pin "1") (pinfunction "1_1") (pintype "passive"))
      (node (ref "C155") (pin "1") (pinfunction "1_1") (pintype "passive"))
      (node (ref "C157") (pin "1") (pinfunction "1_1") (pintype "passive"))
      (node (ref "C159") (pin "1") (pinfunction "1_1") (pintype "passive"))
      (node (ref "C161") (pin "1") (pinfunction "1_1") (pintype "passive"))
      (node (ref "C171") (pin "1") (pinfunction "1_1") (pintype "passive"))
      (node (ref "C173") (pin "1") (pinfunction "1_1") (pintype "passive"))
      (node (ref "C175") (pin "1") (pinfunction "1_1") (pintype "passive"))
      (node (ref "C177") (pin "1") (pinfunction "1_1") (pintype "passive"))
      (node (ref "C187") (pin "1") (pinfunction "1_1") (pintype "passive"))
      (node (ref "C189") (pin "1") (pinfunction "1_1") (pintype "passive"))
      (node (ref "C191") (pin "1") (pinfunction "1_1") (pintype "passive"))
      (node (ref "C193") (pin "1") (pinfunction "1_1") (pintype "passive"))
      (node (ref "C197") (pin "1") (pinfunction "1_1") (pintype "passive"))
      (node (ref "U25") (pin "6") (pinfunction "VS-_6") (pintype "power_in"))
      (node (ref "U25") (pin "7") (pinfunction "PD_N_7") (pintype "input"))
      (node (ref "U26") (pin "6") (pinfunction "VS-_6") (pintype "power_in"))
      (node (ref "U26") (pin "7") (pinfunction "PD_N_7") (pintype "input"))
      (node (ref "U27") (pin "6") (pinfunction "VS-_6") (pintype "power_in"))
      (node (ref "U27") (pin "7") (pinfunction "PD_N_7") (pintype "input"))
      (node (ref "U28") (pin "6") (pinfunction "VS-_6") (pintype "power_in"))
      (node (ref "U28") (pin "7") (pinfunction "PD_N_7") (pintype "input"))
      (node (ref "U29") (pin "6") (pinfunction "VS-_6") (pintype "power_in"))
      (node (ref "U29") (pin "7") (pinfunction "PD_N_7") (pintype "input"))
      (node (ref "U30") (pin "6") (pinfunction "VS-_6") (pintype "power_in"))
      (node (ref "U30") (pin "7") (pinfunction "PD_N_7") (pintype "input"))
      (node (ref "U31") (pin "6") (pinfunction "VS-_6") (pintype "power_in"))
      (node (ref "U31") (pin "7") (pinfunction "PD_N_7") (pintype "input"))
      (node (ref "U32") (pin "6") (pinfunction "VS-_6") (pintype "power_in"))
      (node (ref "U32") (pin "7") (pinfunction "PD_N_7") (pintype "input"))
      (node (ref "U33") (pin "6") (pinfunction "VS-_6") (pintype "power_in"))
      (node (ref "U33") (pin "7") (pinfunction "PD_N_7") (pintype "input"))
      (node (ref "U34") (pin "6") (pinfunction "VS-_6") (pintype "power_in"))
      (node (ref "U34") (pin "7") (pinfunction "PD_N_7") (pintype "input"))
      (node (ref "U35") (pin "6") (pinfunction "VS-_6") (pintype "power_in"))
      (node (ref "U35") (pin "7") (pinfunction "PD_N_7") (pintype "input"))
      (node (ref "U36") (pin "6") (pinfunction "VS-_6") (pintype "power_in"))
      (node (ref "U36") (pin "7") (pinfunction "PD_N_7") (pintype "input"))
      (node (ref "U37") (pin "6") (pinfunction "VS-_6") (pintype "power_in"))
      (node (ref "U37") (pin "7") (pinfunction "PD_N_7") (pintype "input"))
      (node (ref "U38") (pin "6") (pinfunction "VS-_6") (pintype "power_in"))
      (node (ref "U38") (pin "7") (pinfunction "PD_N_7") (pintype "input"))
      (node (ref "U39") (pin "6") (pinfunction "VS-_6") (pintype "power_in"))
      (node (ref "U39") (pin "7") (pinfunction "PD_N_7") (pintype "input"))
      (node (ref "U40") (pin "6") (pinfunction "VS-_6") (pintype "power_in"))
      (node (ref "U40") (pin "7") (pinfunction "PD_N_7") (pintype "input"))
      (node (ref "U41") (pin "6") (pinfunction "VS-_6") (pintype "power_in"))
      (node (ref "U41") (pin "7") (pinfunction "PD_N_7") (pintype "input"))
    )
    (net (code "6") (name "/9+") (class "Default")
      (node (ref "C195") (pin "2") (pinfunction "2_2") (pintype "passive"))
      (node (ref "R110") (pin "2") (pinfunction "2_2") (pintype "passive"))
      (node (ref "U19") (pin "6") (pinfunction "AIN+_6") (pintype "input"))
    )
    (net (code "7") (name "/9-") (class "Default")
      (node (ref "C195") (pin "1") (pinfunction "1_1") (pintype "passive"))
      (node (ref "R111") (pin "2") (pinfunction "2_2") (pintype "passive"))
      (node (ref "U19") (pin "7") (pinfunction "AIN-_7") (pintype "input"))
    )
    (net (code "8") (name "/CNV") (class "Default")
      (node (ref "R53") (pin "3") (pinfunction "3_3") (pintype "passive"))
      (node (ref "U19") (pin "9") (pinfunction "*CNV_9") (pintype "input"))
    )
    (net (code "9") (name "/CNV9") (class "Default")
      (node (ref "R53") (pin "6") (pinfunction "6_6") (pintype "passive"))
    )
    (net (code "10") (name "/SCK") (class "Default")
      (node (ref "R53") (pin "1") (pinfunction "1_1") (pintype "passive"))
      (node (ref "U19") (pin "16") (pinfunction "SCK+_16") (pintype "input"))
    )
    (net (code "11") (name "/SCK9") (class "Default")
      (node (ref "R53") (pin "8") (pinfunction "8_8") (pintype "passive"))
    )
    (net (code "12") (name "/SDO9") (class "Default")
      (node (ref "R53") (pin "7") (pinfunction "7_7") (pintype "passive"))
    )
    (net (code "13") (name "/VREF1V65_9") (class "Default")
      (node (ref "C126") (pin "2") (pinfunction "2_2") (pintype "passive"))
      (node (ref "U24") (pin "1") (pinfunction "VBIAS_1") (pintype "input"))
      (node (ref "U41") (pin "2") (pinfunction "VOCM_2") (pintype "input"))
    )
    (net (code "14") (name "/VREF1V65_W") (class "Default")
      (node (ref "C122") (pin "2") (pinfunction "2_2") (pintype "passive"))
      (node (ref "U22") (pin "1") (pinfunction "VBIAS_1") (pintype "input"))
      (node (ref "U28") (pin "2") (pinfunction "VOCM_2") (pintype "input"))
      (node (ref "U32") (pin "2") (pinfunction "VOCM_2") (pintype "input"))
      (node (ref "U36") (pin "2") (pinfunction "VOCM_2") (pintype "input"))
      (node (ref "U40") (pin "2") (pinfunction "VOCM_2") (pintype "input"))
    )
    (net (code "15") (name "/VREF1V65_X") (class "Default")
      (node (ref "C95") (pin "2") (pinfunction "2_2") (pintype "passive"))
      (node (ref "U20") (pin "1") (pinfunction "VBIAS_1") (pintype "input"))
      (node (ref "U25") (pin "2") (pinfunction "VOCM_2") (pintype "input"))
      (node (ref "U29") (pin "2") (pinfunction "VOCM_2") (pintype "input"))
      (node (ref "U33") (pin "2") (pinfunction "VOCM_2") (pintype "input"))
      (node (ref "U37") (pin "2") (pinfunction "VOCM_2") (pintype "input"))
    )
    (net (code "16") (name "/VREF1V65_Y") (class "Default")
      (node (ref "C117") (pin "2") (pinfunction "2_2") (pintype "passive"))
      (node (ref "U21") (pin "1") (pinfunction "VBIAS_1") (pintype "input"))
      (node (ref "U26") (pin "2") (pinfunction "VOCM_2") (pintype "input"))
      (node (ref "U30") (pin "2") (pinfunction "VOCM_2") (pintype "input"))
      (node (ref "U34") (pin "2") (pinfunction "VOCM_2") (pintype "input"))
      (node (ref "U38") (pin "2") (pinfunction "VOCM_2") (pintype "input"))
    )
    (net (code "17") (name "/VREF1V65_Z") (class "Default")
      (node (ref "C119") (pin "2") (pinfunction "2_2") (pintype "passive"))
      (node (ref "U23") (pin "1") (pinfunction "VBIAS_1") (pintype "input"))
      (node (ref "U27") (pin "2") (pinfunction "VOCM_2") (pintype "input"))
      (node (ref "U31") (pin "2") (pinfunction "VOCM_2") (pintype "input"))
      (node (ref "U35") (pin "2") (pinfunction "VOCM_2") (pintype "input"))
      (node (ref "U39") (pin "2") (pinfunction "VOCM_2") (pintype "input"))
    )
    (net (code "18") (name "/VREF3V3_9") (class "Default")
      (node (ref "C125") (pin "2") (pinfunction "2_2") (pintype "passive"))
      (node (ref "C57") (pin "1") (pinfunction "1_1") (pintype "passive"))
      (node (ref "U19") (pin "3") (pinfunction "REFOUT_3") (pintype "output"))
      (node (ref "U24") (pin "5") (pinfunction "VREF_5") (pintype "output"))
    )
    (net (code "19") (name "/VREF3V3_W") (class "Default")
      (node (ref "C121") (pin "2") (pinfunction "2_2") (pintype "passive"))
      (node (ref "C129") (pin "2") (pinfunction "2_2") (pintype "passive"))
      (node (ref "U18") (pin "8") (pinfunction "REF_8") (pintype "passive"))
      (node (ref "U22") (pin "5") (pinfunction "VREF_5") (pintype "output"))
    )
    (net (code "20") (name "/VREF3V3_X") (class "Default")
      (node (ref "C56") (pin "2") (pinfunction "2_2") (pintype "passive"))
      (node (ref "C94") (pin "2") (pinfunction "2_2") (pintype "passive"))
      (node (ref "U15") (pin "8") (pinfunction "REF_8") (pintype "passive"))
      (node (ref "U20") (pin "5") (pinfunction "VREF_5") (pintype "output"))
    )
    (net (code "21") (name "/VREF3V3_Y") (class "Default")
      (node (ref "C116") (pin "2") (pinfunction "2_2") (pintype "passive"))
      (node (ref "C64") (pin "2") (pinfunction "2_2") (pintype "passive"))
      (node (ref "U16") (pin "8") (pinfunction "REF_8") (pintype "passive"))
      (node (ref "U21") (pin "5") (pinfunction "VREF_5") (pintype "output"))
    )
    (net (code "22") (name "/VREF3V3_Z") (class "Default")
      (node (ref "C118") (pin "2") (pinfunction "2_2") (pintype "passive"))
      (node (ref "C93") (pin "2") (pinfunction "2_2") (pintype "passive"))
      (node (ref "U17") (pin "8") (pinfunction "REF_8") (pintype "passive"))
      (node (ref "U23") (pin "5") (pinfunction "VREF_5") (pintype "output"))
    )
    (net (code "23") (name "/W1+") (class "Default")
      (node (ref "C137") (pin "2") (pinfunction "2_2") (pintype "passive"))
      (node (ref "R68") (pin "2") (pinfunction "2_2") (pintype "passive"))
      (node (ref "U18") (pin "14") (pinfunction "AIN1+_14") (pintype "passive"))
    )
    (net (code "24") (name "/W1-") (class "Default")
      (node (ref "C137") (pin "1") (pinfunction "1_1") (pintype "passive"))
      (node (ref "R72") (pin "2") (pinfunction "2_2") (pintype "passive"))
      (node (ref "U18") (pin "13") (pinfunction "AIN1-_13") (pintype "passive"))
    )
    (net (code "25") (name "/W2+") (class "Default")
      (node (ref "C153") (pin "2") (pinfunction "2_2") (pintype "passive"))
      (node (ref "R80") (pin "2") (pinfunction "2_2") (pintype "passive"))
      (node (ref "U18") (pin "11") (pinfunction "AIN2+_11") (pintype "passive"))
    )
    (net (code "26") (name "/W2-") (class "Default")
      (node (ref "C153") (pin "1") (pinfunction "1_1") (pintype "passive"))
      (node (ref "R84") (pin "2") (pinfunction "2_2") (pintype "passive"))
      (node (ref "U18") (pin "10") (pinfunction "AIN2-_10") (pintype "passive"))
    )
    (net (code "27") (name "/W3+") (class "Default")
      (node (ref "C169") (pin "2") (pinfunction "2_2") (pintype "passive"))
      (node (ref "R92") (pin "2") (pinfunction "2_2") (pintype "passive"))
      (node (ref "U18") (pin "5") (pinfunction "AIN3+_5") (pintype "passive"))
    )
    (net (code "28") (name "/W3-") (class "Default")
      (node (ref "C169") (pin "1") (pinfunction "1_1") (pintype "passive"))
      (node (ref "R96") (pin "2") (pinfunction "2_2") (pintype "passive"))
      (node (ref "U18") (pin "4") (pinfunction "AIN3-_4") (pintype "passive"))
    )
    (net (code "29") (name "/W4+") (class "Default")
      (node (ref "C185") (pin "2") (pinfunction "2_2") (pintype "passive"))
      (node (ref "R104") (pin "2") (pinfunction "2_2") (pintype "passive"))
      (node (ref "U18") (pin "2") (pinfunction "AIN4+_2") (pintype "passive"))
    )
    (net (code "30") (name "/W4-") (class "Default")
      (node (ref "C185") (pin "1") (pinfunction "1_1") (pintype "passive"))
      (node (ref "R108") (pin "2") (pinfunction "2_2") (pintype "passive"))
      (node (ref "U18") (pin "1") (pinfunction "AIN4-_1") (pintype "passive"))
    )
    (net (code "31") (name "/W_CLKOUT") (class "Default")
      (node (ref "R59") (pin "5") (pinfunction "5_5") (pintype "passive"))
    )
    (net (code "32") (name "/W_CNV") (class "Default")
      (node (ref "R60") (pin "6") (pinfunction "6_6") (pintype "passive"))
    )
    (net (code "33") (name "/W_SCK") (class "Default")
      (node (ref "R59") (pin "8") (pinfunction "8_8") (pintype "passive"))
    )
    (net (code "34") (name "/W_SDO1") (class "Default")
      (node (ref "R60") (pin "7") (pinfunction "7_7") (pintype "passive"))
    )
    (net (code "35") (name "/W_SDO2") (class "Default")
      (node (ref "R60") (pin "8") (pinfunction "8_8") (pintype "passive"))
    )
    (net (code "36") (name "/W_SDO3") (class "Default")
      (node (ref "R59") (pin "6") (pinfunction "6_6") (pintype "passive"))
    )
    (net (code "37") (name "/W_SDO4") (class "Default")
      (node (ref "R59") (pin "7") (pinfunction "7_7") (pintype "passive"))
    )
    (net (code "38") (name "/X1+") (class "Default")
      (node (ref "C134") (pin "2") (pinfunction "2_2") (pintype "passive"))
      (node (ref "R65") (pin "2") (pinfunction "2_2") (pintype "passive"))
      (node (ref "U15") (pin "14") (pinfunction "AIN1+_14") (pintype "passive"))
    )
    (net (code "39") (name "/X1-") (class "Default")
      (node (ref "C134") (pin "1") (pinfunction "1_1") (pintype "passive"))
      (node (ref "R69") (pin "2") (pinfunction "2_2") (pintype "passive"))
      (node (ref "U15") (pin "13") (pinfunction "AIN1-_13") (pintype "passive"))
    )
    (net (code "40") (name "/X2+") (class "Default")
      (node (ref "C150") (pin "2") (pinfunction "2_2") (pintype "passive"))
      (node (ref "R77") (pin "2") (pinfunction "2_2") (pintype "passive"))
      (node (ref "U15") (pin "11") (pinfunction "AIN2+_11") (pintype "passive"))
    )
    (net (code "41") (name "/X2-") (class "Default")
      (node (ref "C150") (pin "1") (pinfunction "1_1") (pintype "passive"))
      (node (ref "R81") (pin "2") (pinfunction "2_2") (pintype "passive"))
      (node (ref "U15") (pin "10") (pinfunction "AIN2-_10") (pintype "passive"))
    )
    (net (code "42") (name "/X3+") (class "Default")
      (node (ref "C166") (pin "2") (pinfunction "2_2") (pintype "passive"))
      (node (ref "R89") (pin "2") (pinfunction "2_2") (pintype "passive"))
      (node (ref "U15") (pin "5") (pinfunction "AIN3+_5") (pintype "passive"))
    )
    (net (code "43") (name "/X3-") (class "Default")
      (node (ref "C166") (pin "1") (pinfunction "1_1") (pintype "passive"))
      (node (ref "R93") (pin "2") (pinfunction "2_2") (pintype "passive"))
      (node (ref "U15") (pin "4") (pinfunction "AIN3-_4") (pintype "passive"))
    )
    (net (code "44") (name "/X4+") (class "Default")
      (node (ref "C182") (pin "2") (pinfunction "2_2") (pintype "passive"))
      (node (ref "R101") (pin "2") (pinfunction "2_2") (pintype "passive"))
      (node (ref "U15") (pin "2") (pinfunction "AIN4+_2") (pintype "passive"))
    )
    (net (code "45") (name "/X4-") (class "Default")
      (node (ref "C182") (pin "1") (pinfunction "1_1") (pintype "passive"))
      (node (ref "R105") (pin "2") (pinfunction "2_2") (pintype "passive"))
      (node (ref "U15") (pin "1") (pinfunction "AIN4-_1") (pintype "passive"))
    )
    (net (code "46") (name "/X_CLKOUT") (class "Default")
      (node (ref "R51") (pin "5") (pinfunction "5_5") (pintype "passive"))
    )
    (net (code "47") (name "/X_CNV") (class "Default")
      (node (ref "R52") (pin "6") (pinfunction "6_6") (pintype "passive"))
    )
    (net (code "48") (name "/X_SCK") (class "Default")
      (node (ref "R51") (pin "8") (pinfunction "8_8") (pintype "passive"))
    )
    (net (code "49") (name "/X_SDO1") (class "Default")
      (node (ref "R52") (pin "7") (pinfunction "7_7") (pintype "passive"))
    )
    (net (code "50") (name "/X_SDO2") (class "Default")
      (node (ref "R52") (pin "8") (pinfunction "8_8") (pintype "passive"))
    )
    (net (code "51") (name "/X_SDO3") (class "Default")
      (node (ref "R51") (pin "6") (pinfunction "6_6") (pintype "passive"))
    )
    (net (code "52") (name "/X_SDO4") (class "Default")
      (node (ref "R51") (pin "7") (pinfunction "7_7") (pintype "passive"))
    )
    (net (code "53") (name "/Y1+") (class "Default")
      (node (ref "C135") (pin "2") (pinfunction "2_2") (pintype "passive"))
      (node (ref "R66") (pin "2") (pinfunction "2_2") (pintype "passive"))
      (node (ref "U16") (pin "14") (pinfunction "AIN1+_14") (pintype "passive"))
    )
    (net (code "54") (name "/Y1-") (class "Default")
      (node (ref "C135") (pin "1") (pinfunction "1_1") (pintype "passive"))
      (node (ref "R70") (pin "2") (pinfunction "2_2") (pintype "passive"))
      (node (ref "U16") (pin "13") (pinfunction "AIN1-_13") (pintype "passive"))
    )
    (net (code "55") (name "/Y2+") (class "Default")
      (node (ref "C151") (pin "2") (pinfunction "2_2") (pintype "passive"))
      (node (ref "R78") (pin "2") (pinfunction "2_2") (pintype "passive"))
      (node (ref "U16") (pin "11") (pinfunction "AIN2+_11") (pintype "passive"))
    )
    (net (code "56") (name "/Y2-") (class "Default")
      (node (ref "C151") (pin "1") (pinfunction "1_1") (pintype "passive"))
      (node (ref "R82") (pin "2") (pinfunction "2_2") (pintype "passive"))
      (node (ref "U16") (pin "10") (pinfunction "AIN2-_10") (pintype "passive"))
    )
    (net (code "57") (name "/Y3+") (class "Default")
      (node (ref "C167") (pin "2") (pinfunction "2_2") (pintype "passive"))
      (node (ref "R90") (pin "2") (pinfunction "2_2") (pintype "passive"))
      (node (ref "U16") (pin "5") (pinfunction "AIN3+_5") (pintype "passive"))
    )
    (net (code "58") (name "/Y3-") (class "Default")
      (node (ref "C167") (pin "1") (pinfunction "1_1") (pintype "passive"))
      (node (ref "R94") (pin "2") (pinfunction "2_2") (pintype "passive"))
      (node (ref "U16") (pin "4") (pinfunction "AIN3-_4") (pintype "passive"))
    )
    (net (code "59") (name "/Y4+") (class "Default")
      (node (ref "C183") (pin "2") (pinfunction "2_2") (pintype "passive"))
      (node (ref "R102") (pin "2") (pinfunction "2_2") (pintype "passive"))
      (node (ref "U16") (pin "2") (pinfunction "AIN4+_2") (pintype "passive"))
    )
    (net (code "60") (name "/Y4-") (class "Default")
      (node (ref "C183") (pin "1") (pinfunction "1_1") (pintype "passive"))
      (node (ref "R106") (pin "2") (pinfunction "2_2") (pintype "passive"))
      (node (ref "U16") (pin "1") (pinfunction "AIN4-_1") (pintype "passive"))
    )
    (net (code "61") (name "/Y_CLKOUT") (class "Default")
      (node (ref "R54") (pin "5") (pinfunction "5_5") (pintype "passive"))
    )
    (net (code "62") (name "/Y_CNV") (class "Default")
      (node (ref "R55") (pin "6") (pinfunction "6_6") (pintype "passive"))
    )
    (net (code "63") (name "/Y_SCK") (class "Default")
      (node (ref "R54") (pin "8") (pinfunction "8_8") (pintype "passive"))
    )
    (net (code "64") (name "/Y_SDO1") (class "Default")
      (node (ref "R55") (pin "7") (pinfunction "7_7") (pintype "passive"))
    )
    (net (code "65") (name "/Y_SDO2") (class "Default")
      (node (ref "R55") (pin "8") (pinfunction "8_8") (pintype "passive"))
    )
    (net (code "66") (name "/Y_SDO3") (class "Default")
      (node (ref "R54") (pin "6") (pinfunction "6_6") (pintype "passive"))
    )
    (net (code "67") (name "/Y_SDO4") (class "Default")
      (node (ref "R54") (pin "7") (pinfunction "7_7") (pintype "passive"))
    )
    (net (code "68") (name "/Z1+") (class "Default")
      (node (ref "C136") (pin "2") (pinfunction "2_2") (pintype "passive"))
      (node (ref "R67") (pin "2") (pinfunction "2_2") (pintype "passive"))
      (node (ref "U17") (pin "14") (pinfunction "AIN1+_14") (pintype "passive"))
    )
    (net (code "69") (name "/Z1-") (class "Default")
      (node (ref "C136") (pin "1") (pinfunction "1_1") (pintype "passive"))
      (node (ref "R71") (pin "2") (pinfunction "2_2") (pintype "passive"))
      (node (ref "U17") (pin "13") (pinfunction "AIN1-_13") (pintype "passive"))
    )
    (net (code "70") (name "/Z2+") (class "Default")
      (node (ref "C152") (pin "2") (pinfunction "2_2") (pintype "passive"))
      (node (ref "R79") (pin "2") (pinfunction "2_2") (pintype "passive"))
      (node (ref "U17") (pin "11") (pinfunction "AIN2+_11") (pintype "passive"))
    )
    (net (code "71") (name "/Z2-") (class "Default")
      (node (ref "C152") (pin "1") (pinfunction "1_1") (pintype "passive"))
      (node (ref "R83") (pin "2") (pinfunction "2_2") (pintype "passive"))
      (node (ref "U17") (pin "10") (pinfunction "AIN2-_10") (pintype "passive"))
    )
    (net (code "72") (name "/Z3+") (class "Default")
      (node (ref "C168") (pin "2") (pinfunction "2_2") (pintype "passive"))
      (node (ref "R91") (pin "2") (pinfunction "2_2") (pintype "passive"))
      (node (ref "U17") (pin "5") (pinfunction "AIN3+_5") (pintype "passive"))
    )
    (net (code "73") (name "/Z3-") (class "Default")
      (node (ref "C168") (pin "1") (pinfunction "1_1") (pintype "passive"))
      (node (ref "R95") (pin "2") (pinfunction "2_2") (pintype "passive"))
      (node (ref "U17") (pin "4") (pinfunction "AIN3-_4") (pintype "passive"))
    )
    (net (code "74") (name "/Z4+") (class "Default")
      (node (ref "C184") (pin "2") (pinfunction "2_2") (pintype "passive"))
      (node (ref "R103") (pin "2") (pinfunction "2_2") (pintype "passive"))
      (node (ref "U17") (pin "2") (pinfunction "AIN4+_2") (pintype "passive"))
    )
    (net (code "75") (name "/Z4-") (class "Default")
      (node (ref "C184") (pin "1") (pinfunction "1_1") (pintype "passive"))
      (node (ref "R107") (pin "2") (pinfunction "2_2") (pintype "passive"))
      (node (ref "U17") (pin "1") (pinfunction "AIN4-_1") (pintype "passive"))
    )
    (net (code "76") (name "/Z_CLKOUT") (class "Default")
      (node (ref "R56") (pin "5") (pinfunction "5_5") (pintype "passive"))
    )
    (net (code "77") (name "/Z_CNV") (class "Default")
      (node (ref "R57") (pin "6") (pinfunction "6_6") (pintype "passive"))
    )
    (net (code "78") (name "/Z_SCK") (class "Default")
      (node (ref "R56") (pin "8") (pinfunction "8_8") (pintype "passive"))
    )
    (net (code "79") (name "/Z_SDO1") (class "Default")
      (node (ref "R57") (pin "7") (pinfunction "7_7") (pintype "passive"))
    )
    (net (code "80") (name "/Z_SDO2") (class "Default")
      (node (ref "R57") (pin "8") (pinfunction "8_8") (pintype "passive"))
    )
    (net (code "81") (name "/Z_SDO3") (class "Default")
      (node (ref "R56") (pin "6") (pinfunction "6_6") (pintype "passive"))
    )
    (net (code "82") (name "/Z_SDO4") (class "Default")
      (node (ref "R56") (pin "7") (pinfunction "7_7") (pintype "passive"))
    )
    (net (code "83") (name "AGND1") (class "Default")
      (node (ref "C100") (pin "2") (pinfunction "2_2") (pintype "passive"))
      (node (ref "C101") (pin "2") (pinfunction "2_2") (pintype "passive"))
      (node (ref "C102") (pin "2") (pinfunction "2_2") (pintype "passive"))
      (node (ref "C103") (pin "2") (pinfunction "2_2") (pintype "passive"))
      (node (ref "C104") (pin "2") (pinfunction "2_2") (pintype "passive"))
      (node (ref "C105") (pin "2") (pinfunction "2_2") (pintype "passive"))
      (node (ref "C106") (pin "2") (pinfunction "2_2") (pintype "passive"))
      (node (ref "C107") (pin "2") (pinfunction "2_2") (pintype "passive"))
      (node (ref "C108") (pin "2") (pinfunction "2_2") (pintype "passive"))
      (node (ref "C109") (pin "2") (pinfunction "2_2") (pintype "passive"))
      (node (ref "C110") (pin "2") (pinfunction "2_2") (pintype "passive"))
      (node (ref "C111") (pin "2") (pinfunction "2_2") (pintype "passive"))
      (node (ref "C112") (pin "2") (pinfunction "2_2") (pintype "passive"))
      (node (ref "C113") (pin "2") (pinfunction "2_2") (pintype "passive"))
      (node (ref "C114") (pin "2") (pinfunction "2_2") (pintype "passive"))
      (node (ref "C115") (pin "2") (pinfunction "2_2") (pintype "passive"))
      (node (ref "C116") (pin "1") (pinfunction "1_1") (pintype "passive"))
      (node (ref "C117") (pin "1") (pinfunction "1_1") (pintype "passive"))
      (node (ref "C118") (pin "1") (pinfunction "1_1") (pintype "passive"))
      (node (ref "C119") (pin "1") (pinfunction "1_1") (pintype "passive"))
      (node (ref "C120") (pin "1") (pinfunction "1_1") (pintype "passive"))
      (node (ref "C121") (pin "1") (pinfunction "1_1") (pintype "passive"))
      (node (ref "C122") (pin "1") (pinfunction "1_1") (pintype "passive"))
      (node (ref "C123") (pin "2") (pinfunction "2_2") (pintype "passive"))
      (node (ref "C124") (pin "2") (pinfunction "2_2") (pintype "passive"))
      (node (ref "C125") (pin "1") (pinfunction "1_1") (pintype "passive"))
      (node (ref "C126") (pin "1") (pinfunction "1_1") (pintype "passive"))
      (node (ref "C127") (pin "2") (pinfunction "2_2") (pintype "passive"))
      (node (ref "C128") (pin "2") (pinfunction "2_2") (pintype "passive"))
      (node (ref "C129") (pin "1") (pinfunction "1_1") (pintype "passive"))
      (node (ref "C138") (pin "2") (pinfunction "2_2") (pintype "passive"))
      (node (ref "C139") (pin "2") (pinfunction "2_2") (pintype "passive"))
      (node (ref "C140") (pin "2") (pinfunction "2_2") (pintype "passive"))
      (node (ref "C141") (pin "2") (pinfunction "2_2") (pintype "passive"))
      (node (ref "C142") (pin "2") (pinfunction "2_2") (pintype "passive"))
      (node (ref "C143") (pin "2") (pinfunction "2_2") (pintype "passive"))
      (node (ref "C144") (pin "2") (pinfunction "2_2") (pintype "passive"))
      (node (ref "C145") (pin "2") (pinfunction "2_2") (pintype "passive"))
      (node (ref "C154") (pin "2") (pinfunction "2_2") (pintype "passive"))
      (node (ref "C155") (pin "2") (pinfunction "2_2") (pintype "passive"))
      (node (ref "C156") (pin "2") (pinfunction "2_2") (pintype "passive"))
      (node (ref "C157") (pin "2") (pinfunction "2_2") (pintype "passive"))
      (node (ref "C158") (pin "2") (pinfunction "2_2") (pintype "passive"))
      (node (ref "C159") (pin "2") (pinfunction "2_2") (pintype "passive"))
      (node (ref "C160") (pin "2") (pinfunction "2_2") (pintype "passive"))
      (node (ref "C161") (pin "2") (pinfunction "2_2") (pintype "passive"))
      (node (ref "C170") (pin "2") (pinfunction "2_2") (pintype "passive"))
      (node (ref "C171") (pin "2") (pinfunction "2_2") (pintype "passive"))
      (node (ref "C172") (pin "2") (pinfunction "2_2") (pintype "passive"))
      (node (ref "C173") (pin "2") (pinfunction "2_2") (pintype "passive"))
      (node (ref "C174") (pin "2") (pinfunction "2_2") (pintype "passive"))
      (node (ref "C175") (pin "2") (pinfunction "2_2") (pintype "passive"))
      (node (ref "C176") (pin "2") (pinfunction "2_2") (pintype "passive"))
      (node (ref "C177") (pin "2") (pinfunction "2_2") (pintype "passive"))
      (node (ref "C186") (pin "2") (pinfunction "2_2") (pintype "passive"))
      (node (ref "C187") (pin "2") (pinfunction "2_2") (pintype "passive"))
      (node (ref "C188") (pin "2") (pinfunction "2_2") (pintype "passive"))
      (node (ref "C189") (pin "2") (pinfunction "2_2") (pintype "passive"))
      (node (ref "C190") (pin "2") (pinfunction "2_2") (pintype "passive"))
      (node (ref "C191") (pin "2") (pinfunction "2_2") (pintype "passive"))
      (node (ref "C192") (pin "2") (pinfunction "2_2") (pintype "passive"))
      (node (ref "C193") (pin "2") (pinfunction "2_2") (pintype "passive"))
      (node (ref "C196") (pin "2") (pinfunction "2_2") (pintype "passive"))
      (node (ref "C197") (pin "2") (pinfunction "2_2") (pintype "passive"))
      (node (ref "C52") (pin "2") (pinfunction "2_2") (pintype "passive"))
      (node (ref "C53") (pin "2") (pinfunction "2_2") (pintype "passive"))
      (node (ref "C54") (pin "2") (pinfunction "2_2") (pintype "passive"))
      (node (ref "C55") (pin "2") (pinfunction "2_2") (pintype "passive"))
      (node (ref "C56") (pin "1") (pinfunction "1_1") (pintype "passive"))
      (node (ref "C57") (pin "2") (pinfunction "2_2") (pintype "passive"))
      (node (ref "C58") (pin "2") (pinfunction "2_2") (pintype "passive"))
      (node (ref "C59") (pin "2") (pinfunction "2_2") (pintype "passive"))
      (node (ref "C60") (pin "2") (pinfunction "2_2") (pintype "passive"))
      (node (ref "C61") (pin "2") (pinfunction "2_2") (pintype "passive"))
      (node (ref "C62") (pin "2") (pinfunction "2_2") (pintype "passive"))
      (node (ref "C63") (pin "2") (pinfunction "2_2") (pintype "passive"))
      (node (ref "C64") (pin "1") (pinfunction "1_1") (pintype "passive"))
      (node (ref "C65") (pin "1") (pinfunction "1_1") (pintype "passive"))
      (node (ref "C66") (pin "1") (pinfunction "1_1") (pintype "passive"))
      (node (ref "C67") (pin "2") (pinfunction "2_2") (pintype "passive"))
      (node (ref "C68") (pin "2") (pinfunction "2_2") (pintype "passive"))
      (node (ref "C69") (pin "2") (pinfunction "2_2") (pintype "passive"))
      (node (ref "C70") (pin "2") (pinfunction "2_2") (pintype "passive"))
      (node (ref "C71") (pin "2") (pinfunction "2_2") (pintype "passive"))
      (node (ref "C72") (pin "2") (pinfunction "2_2") (pintype "passive"))
      (node (ref "C73") (pin "2") (pinfunction "2_2") (pintype "passive"))
      (node (ref "C74") (pin "2") (pinfunction "2_2") (pintype "passive"))
      (node (ref "C75") (pin "2") (pinfunction "2_2") (pintype "passive"))
      (node (ref "C76") (pin "2") (pinfunction "2_2") (pintype "passive"))
      (node (ref "C77") (pin "2") (pinfunction "2_2") (pintype "passive"))
      (node (ref "C78") (pin "2") (pinfunction "2_2") (pintype "passive"))
      (node (ref "C79") (pin "2") (pinfunction "2_2") (pintype "passive"))
      (node (ref "C80") (pin "2") (pinfunction "2_2") (pintype "passive"))
      (node (ref "C81") (pin "2") (pinfunction "2_2") (pintype "passive"))
      (node (ref "C82") (pin "2") (pinfunction "2_2") (pintype "passive"))
      (node (ref "C83") (pin "2") (pinfunction "2_2") (pintype "passive"))
      (node (ref "C84") (pin "2") (pinfunction "2_2") (pintype "passive"))
      (node (ref "C85") (pin "2") (pinfunction "2_2") (pintype "passive"))
      (node (ref "C86") (pin "2") (pinfunction "2_2") (pintype "passive"))
      (node (ref "C87") (pin "1") (pinfunction "1_1") (pintype "passive"))
      (node (ref "C88") (pin "1") (pinfunction "1_1") (pintype "passive"))
      (node (ref "C89") (pin "2") (pinfunction "2_2") (pintype "passive"))
      (node (ref "C90") (pin "2") (pinfunction "2_2") (pintype "passive"))
      (node (ref "C91") (pin "2") (pinfunction "2_2") (pintype "passive"))
      (node (ref "C92") (pin "2") (pinfunction "2_2") (pintype "passive"))
      (node (ref "C93") (pin "1") (pinfunction "1_1") (pintype "passive"))
      (node (ref "C94") (pin "1") (pinfunction "1_1") (pintype "passive"))
      (node (ref "C95") (pin "1") (pinfunction "1_1") (pintype "passive"))
      (node (ref "C96") (pin "2") (pinfunction "2_2") (pintype "passive"))
      (node (ref "C97") (pin "2") (pinfunction "2_2") (pintype "passive"))
      (node (ref "C98") (pin "2") (pinfunction "2_2") (pintype "passive"))
      (node (ref "C99") (pin "2") (pinfunction "2_2") (pintype "passive"))
      (node (ref "P9") (pin "1") (pintype "passive"))
      (node (ref "P9") (pin "3") (pintype "passive"))
      (node (ref "PW1") (pin "1") (pintype "passive"))
      (node (ref "PW1") (pin "3") (pintype "passive"))
      (node (ref "PW2") (pin "1") (pintype "passive"))
      (node (ref "PW2") (pin "3") (pintype "passive"))
      (node (ref "PW3") (pin "1") (pintype "passive"))
      (node (ref "PW3") (pin "3") (pintype "passive"))
      (node (ref "PW4") (pin "1") (pintype "passive"))
      (node (ref "PW4") (pin "3") (pintype "passive"))
      (node (ref "PX1") (pin "1") (pintype "passive"))
      (node (ref "PX1") (pin "3") (pintype "passive"))
      (node (ref "PX2") (pin "1") (pintype "passive"))
      (node (ref "PX2") (pin "3") (pintype "passive"))
      (node (ref "PX3") (pin "1") (pintype "passive"))
      (node (ref "PX3") (pin "3") (pintype "passive"))
      (node (ref "PX4") (pin "1") (pintype "passive"))
      (node (ref "PX4") (pin "3") (pintype "passive"))
      (node (ref "PY1") (pin "1") (pintype "passive"))
      (node (ref "PY1") (pin "3") (pintype "passive"))
      (node (ref "PY2") (pin "1") (pintype "passive"))
      (node (ref "PY2") (pin "3") (pintype "passive"))
      (node (ref "PY3") (pin "1") (pintype "passive"))
      (node (ref "PY3") (pin "3") (pintype "passive"))
      (node (ref "PY4") (pin "1") (pintype "passive"))
      (node (ref "PY4") (pin "3") (pintype "passive"))
      (node (ref "PZ1") (pin "1") (pintype "passive"))
      (node (ref "PZ1") (pin "3") (pintype "passive"))
      (node (ref "PZ2") (pin "1") (pintype "passive"))
      (node (ref "PZ2") (pin "3") (pintype "passive"))
      (node (ref "PZ3") (pin "1") (pintype "passive"))
      (node (ref "PZ3") (pin "3") (pintype "passive"))
      (node (ref "PZ4") (pin "1") (pintype "passive"))
      (node (ref "PZ4") (pin "3") (pintype "passive"))
      (node (ref "R58") (pin "1") (pinfunction "1_1") (pintype "passive"))
      (node (ref "U15") (pin "12") (pinfunction "GND_12") (pintype "passive"))
      (node (ref "U15") (pin "18") (pinfunction "GND_18") (pintype "passive"))
      (node (ref "U15") (pin "23") (pinfunction "*SDR/DDR_23") (pintype "passive"))
      (node (ref "U15") (pin "25") (pinfunction "*CMOS/LVDS_25") (pintype "passive"))
      (node (ref "U15") (pin "26") (pinfunction "GND_26") (pintype "passive"))
      (node (ref "U15") (pin "3") (pinfunction "GND_3") (pintype "passive"))
      (node (ref "U15") (pin "32") (pinfunction "GND_32") (pintype "passive"))
      (node (ref "U15") (pin "38") (pinfunction "GND_38") (pintype "passive"))
      (node (ref "U15") (pin "46") (pinfunction "GND_46") (pintype "passive"))
      (node (ref "U15") (pin "49") (pinfunction "GND_49") (pintype "passive"))
      (node (ref "U15") (pin "53") (pinfunction "GND_53") (pintype "passive"))
      (node (ref "U15") (pin "7") (pinfunction "GND_7") (pintype "passive"))
      (node (ref "U16") (pin "12") (pinfunction "GND_12") (pintype "passive"))
      (node (ref "U16") (pin "18") (pinfunction "GND_18") (pintype "passive"))
      (node (ref "U16") (pin "23") (pinfunction "*SDR/DDR_23") (pintype "passive"))
      (node (ref "U16") (pin "25") (pinfunction "*CMOS/LVDS_25") (pintype "passive"))
      (node (ref "U16") (pin "26") (pinfunction "GND_26") (pintype "passive"))
      (node (ref "U16") (pin "3") (pinfunction "GND_3") (pintype "passive"))
      (node (ref "U16") (pin "32") (pinfunction "GND_32") (pintype "passive"))
      (node (ref "U16") (pin "38") (pinfunction "GND_38") (pintype "passive"))
      (node (ref "U16") (pin "46") (pinfunction "GND_46") (pintype "passive"))
      (node (ref "U16") (pin "49") (pinfunction "GND_49") (pintype "passive"))
      (node (ref "U16") (pin "53") (pinfunction "GND_53") (pintype "passive"))
      (node (ref "U16") (pin "7") (pinfunction "GND_7") (pintype "passive"))
      (node (ref "U17") (pin "12") (pinfunction "GND_12") (pintype "passive"))
      (node (ref "U17") (pin "18") (pinfunction "GND_18") (pintype "passive"))
      (node (ref "U17") (pin "23") (pinfunction "*SDR/DDR_23") (pintype "passive"))
      (node (ref "U17") (pin "25") (pinfunction "*CMOS/LVDS_25") (pintype "passive"))
      (node (ref "U17") (pin "26") (pinfunction "GND_26") (pintype "passive"))
      (node (ref "U17") (pin "3") (pinfunction "GND_3") (pintype "passive"))
      (node (ref "U17") (pin "32") (pinfunction "GND_32") (pintype "passive"))
      (node (ref "U17") (pin "38") (pinfunction "GND_38") (pintype "passive"))
      (node (ref "U17") (pin "46") (pinfunction "GND_46") (pintype "passive"))
      (node (ref "U17") (pin "49") (pinfunction "GND_49") (pintype "passive"))
      (node (ref "U17") (pin "53") (pinfunction "GND_53") (pintype "passive"))
      (node (ref "U17") (pin "7") (pinfunction "GND_7") (pintype "passive"))
      (node (ref "U18") (pin "12") (pinfunction "GND_12") (pintype "passive"))
      (node (ref "U18") (pin "18") (pinfunction "GND_18") (pintype "passive"))
      (node (ref "U18") (pin "23") (pinfunction "*SDR/DDR_23") (pintype "passive"))
      (node (ref "U18") (pin "25") (pinfunction "*CMOS/LVDS_25") (pintype "passive"))
      (node (ref "U18") (pin "26") (pinfunction "GND_26") (pintype "passive"))
      (node (ref "U18") (pin "3") (pinfunction "GND_3") (pintype "passive"))
      (node (ref "U18") (pin "32") (pinfunction "GND_32") (pintype "passive"))
      (node (ref "U18") (pin "38") (pinfunction "GND_38") (pintype "passive"))
      (node (ref "U18") (pin "46") (pinfunction "GND_46") (pintype "passive"))
      (node (ref "U18") (pin "49") (pinfunction "GND_49") (pintype "passive"))
      (node (ref "U18") (pin "53") (pinfunction "GND_53") (pintype "passive"))
      (node (ref "U18") (pin "7") (pinfunction "GND_7") (pintype "passive"))
      (node (ref "U19") (pin "1") (pinfunction "GND_1") (pintype "power_in"))
      (node (ref "U19") (pin "10") (pinfunction "*CMOS/LVDS_10") (pintype "passive"))
      (node (ref "U19") (pin "11") (pinfunction "GND_11") (pintype "power_in"))
      (node (ref "U19") (pin "17") (pinfunction "GND_17") (pintype "power_in"))
      (node (ref "U19") (pin "2") (pinfunction "REFIN_2") (pintype "input"))
      (node (ref "U19") (pin "5") (pinfunction "GND_5") (pintype "power_in"))
      (node (ref "U19") (pin "8") (pinfunction "GND_8") (pintype "power_in"))
      (node (ref "U20") (pin "2") (pinfunction "GND_2") (pintype "power_in"))
      (node (ref "U21") (pin "2") (pinfunction "GND_2") (pintype "power_in"))
      (node (ref "U22") (pin "2") (pinfunction "GND_2") (pintype "power_in"))
      (node (ref "U23") (pin "2") (pinfunction "GND_2") (pintype "power_in"))
      (node (ref "U24") (pin "2") (pinfunction "GND_2") (pintype "power_in"))
      (node (ref "U25") (pin "8") (pinfunction "VIN+_8") (pintype "input"))
      (node (ref "U26") (pin "8") (pinfunction "VIN+_8") (pintype "input"))
      (node (ref "U27") (pin "8") (pinfunction "VIN+_8") (pintype "input"))
      (node (ref "U28") (pin "8") (pinfunction "VIN+_8") (pintype "input"))
      (node (ref "U29") (pin "8") (pinfunction "VIN+_8") (pintype "input"))
      (node (ref "U30") (pin "8") (pinfunction "VIN+_8") (pintype "input"))
      (node (ref "U31") (pin "8") (pinfunction "VIN+_8") (pintype "input"))
      (node (ref "U32") (pin "8") (pinfunction "VIN+_8") (pintype "input"))
      (node (ref "U33") (pin "8") (pinfunction "VIN+_8") (pintype "input"))
      (node (ref "U34") (pin "8") (pinfunction "VIN+_8") (pintype "input"))
      (node (ref "U35") (pin "8") (pinfunction "VIN+_8") (pintype "input"))
      (node (ref "U36") (pin "8") (pinfunction "VIN+_8") (pintype "input"))
      (node (ref "U37") (pin "8") (pinfunction "VIN+_8") (pintype "input"))
      (node (ref "U38") (pin "8") (pinfunction "VIN+_8") (pintype "input"))
      (node (ref "U39") (pin "8") (pinfunction "VIN+_8") (pintype "input"))
      (node (ref "U40") (pin "8") (pinfunction "VIN+_8") (pintype "input"))
      (node (ref "U41") (pin "8") (pinfunction "VIN+_8") (pintype "input"))
    )
    (net (code "84") (name "GND") (class "Default")
      (node (ref "R58") (pin "2") (pinfunction "2_2") (pintype "passive"))
    )
    (net (code "85") (name "Net-(U15A-*CNV)") (class "Default")
      (node (ref "R52") (pin "3") (pinfunction "3_3") (pintype "passive"))
      (node (ref "U15") (pin "24") (pinfunction "*CNV_24") (pintype "passive"))
    )
    (net (code "86") (name "Net-(U15A-CLKOUT{slash}CLKOUT+)") (class "Default")
      (node (ref "R51") (pin "4") (pinfunction "4_4") (pintype "passive"))
      (node (ref "U15") (pin "33") (pinfunction "CLKOUT/CLKOUT+_33") (pintype "passive"))
    )
    (net (code "87") (name "Net-(U15A-REFOUT1)") (class "Default")
      (node (ref "C52") (pin "1") (pinfunction "1_1") (pintype "passive"))
      (node (ref "U15") (pin "22") (pinfunction "REFOUT1_22") (pintype "passive"))
    )
    (net (code "88") (name "Net-(U15A-REFOUT2)") (class "Default")
      (node (ref "C53") (pin "1") (pinfunction "1_1") (pintype "passive"))
      (node (ref "U15") (pin "9") (pinfunction "REFOUT2_9") (pintype "passive"))
    )
    (net (code "89") (name "Net-(U15A-REFOUT3)") (class "Default")
      (node (ref "C54") (pin "1") (pinfunction "1_1") (pintype "passive"))
      (node (ref "U15") (pin "6") (pinfunction "REFOUT3_6") (pintype "passive"))
    )
    (net (code "90") (name "Net-(U15A-REFOUT4)") (class "Default")
      (node (ref "C55") (pin "1") (pinfunction "1_1") (pintype "passive"))
      (node (ref "U15") (pin "45") (pinfunction "REFOUT4_45") (pintype "passive"))
    )
    (net (code "91") (name "Net-(U15A-SCK{slash}SCK+)") (class "Default")
      (node (ref "R51") (pin "1") (pinfunction "1_1") (pintype "passive"))
      (node (ref "U15") (pin "41") (pinfunction "SCK/SCK+_41") (pintype "passive"))
    )
    (net (code "92") (name "Net-(U15A-SDO1{slash}SDOA+)") (class "Default")
      (node (ref "R52") (pin "2") (pinfunction "2_2") (pintype "passive"))
      (node (ref "U15") (pin "27") (pinfunction "SDO1/SDOA+_27") (pintype "passive"))
    )
    (net (code "93") (name "Net-(U15A-SDO2{slash}SDOB+)") (class "Default")
      (node (ref "R52") (pin "1") (pinfunction "1_1") (pintype "passive"))
      (node (ref "U15") (pin "29") (pinfunction "SDO2/SDOB+_29") (pintype "passive"))
    )
    (net (code "94") (name "Net-(U15A-SDO3{slash}SDOC+)") (class "Default")
      (node (ref "R51") (pin "3") (pinfunction "3_3") (pintype "passive"))
      (node (ref "U15") (pin "35") (pinfunction "SDO3/SDOC+_35") (pintype "passive"))
    )
    (net (code "95") (name "Net-(U15A-SDO4{slash}SDOD+)") (class "Default")
      (node (ref "R51") (pin "2") (pinfunction "2_2") (pintype "passive"))
      (node (ref "U15") (pin "39") (pinfunction "SDO4/SDOD+_39") (pintype "passive"))
    )
    (net (code "96") (name "Net-(U16A-*CNV)") (class "Default")
      (node (ref "R55") (pin "3") (pinfunction "3_3") (pintype "passive"))
      (node (ref "U16") (pin "24") (pinfunction "*CNV_24") (pintype "passive"))
    )
    (net (code "97") (name "Net-(U16A-CLKOUT{slash}CLKOUT+)") (class "Default")
      (node (ref "R54") (pin "4") (pinfunction "4_4") (pintype "passive"))
      (node (ref "U16") (pin "33") (pinfunction "CLKOUT/CLKOUT+_33") (pintype "passive"))
    )
    (net (code "98") (name "Net-(U16A-REFOUT1)") (class "Default")
      (node (ref "C60") (pin "1") (pinfunction "1_1") (pintype "passive"))
      (node (ref "U16") (pin "22") (pinfunction "REFOUT1_22") (pintype "passive"))
    )
    (net (code "99") (name "Net-(U16A-REFOUT2)") (class "Default")
      (node (ref "C61") (pin "1") (pinfunction "1_1") (pintype "passive"))
      (node (ref "U16") (pin "9") (pinfunction "REFOUT2_9") (pintype "passive"))
    )
    (net (code "100") (name "Net-(U16A-REFOUT3)") (class "Default")
      (node (ref "C62") (pin "1") (pinfunction "1_1") (pintype "passive"))
      (node (ref "U16") (pin "6") (pinfunction "REFOUT3_6") (pintype "passive"))
    )
    (net (code "101") (name "Net-(U16A-REFOUT4)") (class "Default")
      (node (ref "C63") (pin "1") (pinfunction "1_1") (pintype "passive"))
      (node (ref "U16") (pin "45") (pinfunction "REFOUT4_45") (pintype "passive"))
    )
    (net (code "102") (name "Net-(U16A-SCK{slash}SCK+)") (class "Default")
      (node (ref "R54") (pin "1") (pinfunction "1_1") (pintype "passive"))
      (node (ref "U16") (pin "41") (pinfunction "SCK/SCK+_41") (pintype "passive"))
    )
    (net (code "103") (name "Net-(U16A-SDO1{slash}SDOA+)") (class "Default")
      (node (ref "R55") (pin "2") (pinfunction "2_2") (pintype "passive"))
      (node (ref "U16") (pin "27") (pinfunction "SDO1/SDOA+_27") (pintype "passive"))
    )
    (net (code "104") (name "Net-(U16A-SDO2{slash}SDOB+)") (class "Default")
      (node (ref "R55") (pin "1") (pinfunction "1_1") (pintype "passive"))
      (node (ref "U16") (pin "29") (pinfunction "SDO2/SDOB+_29") (pintype "passive"))
    )
    (net (code "105") (name "Net-(U16A-SDO3{slash}SDOC+)") (class "Default")
      (node (ref "R54") (pin "3") (pinfunction "3_3") (pintype "passive"))
      (node (ref "U16") (pin "35") (pinfunction "SDO3/SDOC+_35") (pintype "passive"))
    )
    (net (code "106") (name "Net-(U16A-SDO4{slash}SDOD+)") (class "Default")
      (node (ref "R54") (pin "2") (pinfunction "2_2") (pintype "passive"))
      (node (ref "U16") (pin "39") (pinfunction "SDO4/SDOD+_39") (pintype "passive"))
    )
    (net (code "107") (name "Net-(U17A-*CNV)") (class "Default")
      (node (ref "R57") (pin "3") (pinfunction "3_3") (pintype "passive"))
      (node (ref "U17") (pin "24") (pinfunction "*CNV_24") (pintype "passive"))
    )
    (net (code "108") (name "Net-(U17A-CLKOUT{slash}CLKOUT+)") (class "Default")
      (node (ref "R56") (pin "4") (pinfunction "4_4") (pintype "passive"))
      (node (ref "U17") (pin "33") (pinfunction "CLKOUT/CLKOUT+_33") (pintype "passive"))
    )
    (net (code "109") (name "Net-(U17A-REFOUT1)") (class "Default")
      (node (ref "C89") (pin "1") (pinfunction "1_1") (pintype "passive"))
      (node (ref "U17") (pin "22") (pinfunction "REFOUT1_22") (pintype "passive"))
    )
    (net (code "110") (name "Net-(U17A-REFOUT2)") (class "Default")
      (node (ref "C90") (pin "1") (pinfunction "1_1") (pintype "passive"))
      (node (ref "U17") (pin "9") (pinfunction "REFOUT2_9") (pintype "passive"))
    )
    (net (code "111") (name "Net-(U17A-REFOUT3)") (class "Default")
      (node (ref "C91") (pin "1") (pinfunction "1_1") (pintype "passive"))
      (node (ref "U17") (pin "6") (pinfunction "REFOUT3_6") (pintype "passive"))
    )
    (net (code "112") (name "Net-(U17A-REFOUT4)") (class "Default")
      (node (ref "C92") (pin "1") (pinfunction "1_1") (pintype "passive"))
      (node (ref "U17") (pin "45") (pinfunction "REFOUT4_45") (pintype "passive"))
    )
    (net (code "113") (name "Net-(U17A-SCK{slash}SCK+)") (class "Default")
      (node (ref "R56") (pin "1") (pinfunction "1_1") (pintype "passive"))
      (node (ref "U17") (pin "41") (pinfunction "SCK/SCK+_41") (pintype "passive"))
    )
    (net (code "114") (name "Net-(U17A-SDO1{slash}SDOA+)") (class "Default")
      (node (ref "R57") (pin "2") (pinfunction "2_2") (pintype "passive"))
      (node (ref "U17") (pin "27") (pinfunction "SDO1/SDOA+_27") (pintype "passive"))
    )
    (net (code "115") (name "Net-(U17A-SDO2{slash}SDOB+)") (class "Default")
      (node (ref "R57") (pin "1") (pinfunction "1_1") (pintype "passive"))
      (node (ref "U17") (pin "29") (pinfunction "SDO2/SDOB+_29") (pintype "passive"))
    )
    (net (code "116") (name "Net-(U17A-SDO3{slash}SDOC+)") (class "Default")
      (node (ref "R56") (pin "3") (pinfunction "3_3") (pintype "passive"))
      (node (ref "U17") (pin "35") (pinfunction "SDO3/SDOC+_35") (pintype "passive"))
    )
    (net (code "117") (name "Net-(U17A-SDO4{slash}SDOD+)") (class "Default")
      (node (ref "R56") (pin "2") (pinfunction "2_2") (pintype "passive"))
      (node (ref "U17") (pin "39") (pinfunction "SDO4/SDOD+_39") (pintype "passive"))
    )
    (net (code "118") (name "Net-(U18A-*CNV)") (class "Default")
      (node (ref "R60") (pin "3") (pinfunction "3_3") (pintype "passive"))
      (node (ref "U18") (pin "24") (pinfunction "*CNV_24") (pintype "passive"))
    )
    (net (code "119") (name "Net-(U18A-CLKOUT{slash}CLKOUT+)") (class "Default")
      (node (ref "R59") (pin "4") (pinfunction "4_4") (pintype "passive"))
      (node (ref "U18") (pin "33") (pinfunction "CLKOUT/CLKOUT+_33") (pintype "passive"))
    )
    (net (code "120") (name "Net-(U18A-REFOUT1)") (class "Default")
      (node (ref "C123") (pin "1") (pinfunction "1_1") (pintype "passive"))
      (node (ref "U18") (pin "22") (pinfunction "REFOUT1_22") (pintype "passive"))
    )
    (net (code "121") (name "Net-(U18A-REFOUT2)") (class "Default")
      (node (ref "C124") (pin "1") (pinfunction "1_1") (pintype "passive"))
      (node (ref "U18") (pin "9") (pinfunction "REFOUT2_9") (pintype "passive"))
    )
    (net (code "122") (name "Net-(U18A-REFOUT3)") (class "Default")
      (node (ref "C127") (pin "1") (pinfunction "1_1") (pintype "passive"))
      (node (ref "U18") (pin "6") (pinfunction "REFOUT3_6") (pintype "passive"))
    )
    (net (code "123") (name "Net-(U18A-REFOUT4)") (class "Default")
      (node (ref "C128") (pin "1") (pinfunction "1_1") (pintype "passive"))
      (node (ref "U18") (pin "45") (pinfunction "REFOUT4_45") (pintype "passive"))
    )
    (net (code "124") (name "Net-(U18A-SCK{slash}SCK+)") (class "Default")
      (node (ref "R59") (pin "1") (pinfunction "1_1") (pintype "passive"))
      (node (ref "U18") (pin "41") (pinfunction "SCK/SCK+_41") (pintype "passive"))
    )
    (net (code "125") (name "Net-(U18A-SDO1{slash}SDOA+)") (class "Default")
      (node (ref "R60") (pin "2") (pinfunction "2_2") (pintype "passive"))
      (node (ref "U18") (pin "27") (pinfunction "SDO1/SDOA+_27") (pintype "passive"))
    )
    (net (code "126") (name "Net-(U18A-SDO2{slash}SDOB+)") (class "Default")
      (node (ref "R60") (pin "1") (pinfunction "1_1") (pintype "passive"))
      (node (ref "U18") (pin "29") (pinfunction "SDO2/SDOB+_29") (pintype "passive"))
    )
    (net (code "127") (name "Net-(U18A-SDO3{slash}SDOC+)") (class "Default")
      (node (ref "R59") (pin "3") (pinfunction "3_3") (pintype "passive"))
      (node (ref "U18") (pin "35") (pinfunction "SDO3/SDOC+_35") (pintype "passive"))
    )
    (net (code "128") (name "Net-(U18A-SDO4{slash}SDOD+)") (class "Default")
      (node (ref "R59") (pin "2") (pinfunction "2_2") (pintype "passive"))
      (node (ref "U18") (pin "39") (pinfunction "SDO4/SDOD+_39") (pintype "passive"))
    )
    (net (code "129") (name "Net-(U19-SDO+)") (class "Default")
      (node (ref "R53") (pin "2") (pinfunction "2_2") (pintype "passive"))
      (node (ref "U19") (pin "14") (pinfunction "SDO+_14") (pintype "output"))
    )
    (net (code "130") (name "Net-(U25-VIN-)") (class "Default")
      (node (ref "C130") (pin "1") (pinfunction "1_1") (pintype "passive"))
      (node (ref "PX1") (pin "2") (pintype "passive"))
      (node (ref "R61") (pin "1") (pinfunction "1_1") (pintype "passive"))
      (node (ref "U25") (pin "1") (pinfunction "VIN-_1") (pintype "input"))
    )
    (net (code "131") (name "Net-(U25-VOUT+)") (class "Default")
      (node (ref "C130") (pin "2") (pinfunction "2_2") (pintype "passive"))
      (node (ref "R61") (pin "2") (pinfunction "2_2") (pintype "passive"))
      (node (ref "R65") (pin "1") (pinfunction "1_1") (pintype "passive"))
      (node (ref "U25") (pin "4") (pinfunction "VOUT+_4") (pintype "output"))
    )
    (net (code "132") (name "Net-(U25-VOUT-)") (class "Default")
      (node (ref "R69") (pin "1") (pinfunction "1_1") (pintype "passive"))
      (node (ref "U25") (pin "5") (pinfunction "VOUT-_5") (pintype "output"))
    )
    (net (code "133") (name "Net-(U26-VIN-)") (class "Default")
      (node (ref "C131") (pin "1") (pinfunction "1_1") (pintype "passive"))
      (node (ref "PY1") (pin "2") (pintype "passive"))
      (node (ref "R62") (pin "1") (pinfunction "1_1") (pintype "passive"))
      (node (ref "U26") (pin "1") (pinfunction "VIN-_1") (pintype "input"))
    )
    (net (code "134") (name "Net-(U26-VOUT+)") (class "Default")
      (node (ref "C131") (pin "2") (pinfunction "2_2") (pintype "passive"))
      (node (ref "R62") (pin "2") (pinfunction "2_2") (pintype "passive"))
      (node (ref "R66") (pin "1") (pinfunction "1_1") (pintype "passive"))
      (node (ref "U26") (pin "4") (pinfunction "VOUT+_4") (pintype "output"))
    )
    (net (code "135") (name "Net-(U26-VOUT-)") (class "Default")
      (node (ref "R70") (pin "1") (pinfunction "1_1") (pintype "passive"))
      (node (ref "U26") (pin "5") (pinfunction "VOUT-_5") (pintype "output"))
    )
    (net (code "136") (name "Net-(U27-VIN-)") (class "Default")
      (node (ref "C132") (pin "1") (pinfunction "1_1") (pintype "passive"))
      (node (ref "PZ1") (pin "2") (pintype "passive"))
      (node (ref "R63") (pin "1") (pinfunction "1_1") (pintype "passive"))
      (node (ref "U27") (pin "1") (pinfunction "VIN-_1") (pintype "input"))
    )
    (net (code "137") (name "Net-(U27-VOUT+)") (class "Default")
      (node (ref "C132") (pin "2") (pinfunction "2_2") (pintype "passive"))
      (node (ref "R63") (pin "2") (pinfunction "2_2") (pintype "passive"))
      (node (ref "R67") (pin "1") (pinfunction "1_1") (pintype "passive"))
      (node (ref "U27") (pin "4") (pinfunction "VOUT+_4") (pintype "output"))
    )
    (net (code "138") (name "Net-(U27-VOUT-)") (class "Default")
      (node (ref "R71") (pin "1") (pinfunction "1_1") (pintype "passive"))
      (node (ref "U27") (pin "5") (pinfunction "VOUT-_5") (pintype "output"))
    )
    (net (code "139") (name "Net-(U28-VIN-)") (class "Default")
      (node (ref "C133") (pin "1") (pinfunction "1_1") (pintype "passive"))
      (node (ref "PW1") (pin "2") (pintype "passive"))
      (node (ref "R64") (pin "1") (pinfunction "1_1") (pintype "passive"))
      (node (ref "U28") (pin "1") (pinfunction "VIN-_1") (pintype "input"))
    )
    (net (code "140") (name "Net-(U28-VOUT+)") (class "Default")
      (node (ref "C133") (pin "2") (pinfunction "2_2") (pintype "passive"))
      (node (ref "R64") (pin "2") (pinfunction "2_2") (pintype "passive"))
      (node (ref "R68") (pin "1") (pinfunction "1_1") (pintype "passive"))
      (node (ref "U28") (pin "4") (pinfunction "VOUT+_4") (pintype "output"))
    )
    (net (code "141") (name "Net-(U28-VOUT-)") (class "Default")
      (node (ref "R72") (pin "1") (pinfunction "1_1") (pintype "passive"))
      (node (ref "U28") (pin "5") (pinfunction "VOUT-_5") (pintype "output"))
    )
    (net (code "142") (name "Net-(U29-VIN-)") (class "Default")
      (node (ref "C146") (pin "1") (pinfunction "1_1") (pintype "passive"))
      (node (ref "PX2") (pin "2") (pintype "passive"))
      (node (ref "R73") (pin "1") (pinfunction "1_1") (pintype "passive"))
      (node (ref "U29") (pin "1") (pinfunction "VIN-_1") (pintype "input"))
    )
    (net (code "143") (name "Net-(U29-VOUT+)") (class "Default")
      (node (ref "C146") (pin "2") (pinfunction "2_2") (pintype "passive"))
      (node (ref "R73") (pin "2") (pinfunction "2_2") (pintype "passive"))
      (node (ref "R77") (pin "1") (pinfunction "1_1") (pintype "passive"))
      (node (ref "U29") (pin "4") (pinfunction "VOUT+_4") (pintype "output"))
    )
    (net (code "144") (name "Net-(U29-VOUT-)") (class "Default")
      (node (ref "R81") (pin "1") (pinfunction "1_1") (pintype "passive"))
      (node (ref "U29") (pin "5") (pinfunction "VOUT-_5") (pintype "output"))
    )
    (net (code "145") (name "Net-(U30-VIN-)") (class "Default")
      (node (ref "C147") (pin "1") (pinfunction "1_1") (pintype "passive"))
      (node (ref "PY2") (pin "2") (pintype "passive"))
      (node (ref "R74") (pin "1") (pinfunction "1_1") (pintype "passive"))
      (node (ref "U30") (pin "1") (pinfunction "VIN-_1") (pintype "input"))
    )
    (net (code "146") (name "Net-(U30-VOUT+)") (class "Default")
      (node (ref "C147") (pin "2") (pinfunction "2_2") (pintype "passive"))
      (node (ref "R74") (pin "2") (pinfunction "2_2") (pintype "passive"))
      (node (ref "R78") (pin "1") (pinfunction "1_1") (pintype "passive"))
      (node (ref "U30") (pin "4") (pinfunction "VOUT+_4") (pintype "output"))
    )
    (net (code "147") (name "Net-(U30-VOUT-)") (class "Default")
      (node (ref "R82") (pin "1") (pinfunction "1_1") (pintype "passive"))
      (node (ref "U30") (pin "5") (pinfunction "VOUT-_5") (pintype "output"))
    )
    (net (code "148") (name "Net-(U31-VIN-)") (class "Default")
      (node (ref "C148") (pin "1") (pinfunction "1_1") (pintype "passive"))
      (node (ref "PZ2") (pin "2") (pintype "passive"))
      (node (ref "R75") (pin "1") (pinfunction "1_1") (pintype "passive"))
      (node (ref "U31") (pin "1") (pinfunction "VIN-_1") (pintype "input"))
    )
    (net (code "149") (name "Net-(U31-VOUT+)") (class "Default")
      (node (ref "C148") (pin "2") (pinfunction "2_2") (pintype "passive"))
      (node (ref "R75") (pin "2") (pinfunction "2_2") (pintype "passive"))
      (node (ref "R79") (pin "1") (pinfunction "1_1") (pintype "passive"))
      (node (ref "U31") (pin "4") (pinfunction "VOUT+_4") (pintype "output"))
    )
    (net (code "150") (name "Net-(U31-VOUT-)") (class "Default")
      (node (ref "R83") (pin "1") (pinfunction "1_1") (pintype "passive"))
      (node (ref "U31") (pin "5") (pinfunction "VOUT-_5") (pintype "output"))
    )
    (net (code "151") (name "Net-(U32-VIN-)") (class "Default")
      (node (ref "C149") (pin "1") (pinfunction "1_1") (pintype "passive"))
      (node (ref "PW2") (pin "2") (pintype "passive"))
      (node (ref "R76") (pin "1") (pinfunction "1_1") (pintype "passive"))
      (node (ref "U32") (pin "1") (pinfunction "VIN-_1") (pintype "input"))
    )
    (net (code "152") (name "Net-(U32-VOUT+)") (class "Default")
      (node (ref "C149") (pin "2") (pinfunction "2_2") (pintype "passive"))
      (node (ref "R76") (pin "2") (pinfunction "2_2") (pintype "passive"))
      (node (ref "R80") (pin "1") (pinfunction "1_1") (pintype "passive"))
      (node (ref "U32") (pin "4") (pinfunction "VOUT+_4") (pintype "output"))
    )
    (net (code "153") (name "Net-(U32-VOUT-)") (class "Default")
      (node (ref "R84") (pin "1") (pinfunction "1_1") (pintype "passive"))
      (node (ref "U32") (pin "5") (pinfunction "VOUT-_5") (pintype "output"))
    )
    (net (code "154") (name "Net-(U33-VIN-)") (class "Default")
      (node (ref "C162") (pin "1") (pinfunction "1_1") (pintype "passive"))
      (node (ref "PX3") (pin "2") (pintype "passive"))
      (node (ref "R85") (pin "1") (pinfunction "1_1") (pintype "passive"))
      (node (ref "U33") (pin "1") (pinfunction "VIN-_1") (pintype "input"))
    )
    (net (code "155") (name "Net-(U33-VOUT+)") (class "Default")
      (node (ref "C162") (pin "2") (pinfunction "2_2") (pintype "passive"))
      (node (ref "R85") (pin "2") (pinfunction "2_2") (pintype "passive"))
      (node (ref "R89") (pin "1") (pinfunction "1_1") (pintype "passive"))
      (node (ref "U33") (pin "4") (pinfunction "VOUT+_4") (pintype "output"))
    )
    (net (code "156") (name "Net-(U33-VOUT-)") (class "Default")
      (node (ref "R93") (pin "1") (pinfunction "1_1") (pintype "passive"))
      (node (ref "U33") (pin "5") (pinfunction "VOUT-_5") (pintype "output"))
    )
    (net (code "157") (name "Net-(U34-VIN-)") (class "Default")
      (node (ref "C163") (pin "1") (pinfunction "1_1") (pintype "passive"))
      (node (ref "PY3") (pin "2") (pintype "passive"))
      (node (ref "R86") (pin "1") (pinfunction "1_1") (pintype "passive"))
      (node (ref "U34") (pin "1") (pinfunction "VIN-_1") (pintype "input"))
    )
    (net (code "158") (name "Net-(U34-VOUT+)") (class "Default")
      (node (ref "C163") (pin "2") (pinfunction "2_2") (pintype "passive"))
      (node (ref "R86") (pin "2") (pinfunction "2_2") (pintype "passive"))
      (node (ref "R90") (pin "1") (pinfunction "1_1") (pintype "passive"))
      (node (ref "U34") (pin "4") (pinfunction "VOUT+_4") (pintype "output"))
    )
    (net (code "159") (name "Net-(U34-VOUT-)") (class "Default")
      (node (ref "R94") (pin "1") (pinfunction "1_1") (pintype "passive"))
      (node (ref "U34") (pin "5") (pinfunction "VOUT-_5") (pintype "output"))
    )
    (net (code "160") (name "Net-(U35-VIN-)") (class "Default")
      (node (ref "C164") (pin "1") (pinfunction "1_1") (pintype "passive"))
      (node (ref "PZ3") (pin "2") (pintype "passive"))
      (node (ref "R87") (pin "1") (pinfunction "1_1") (pintype "passive"))
      (node (ref "U35") (pin "1") (pinfunction "VIN-_1") (pintype "input"))
    )
    (net (code "161") (name "Net-(U35-VOUT+)") (class "Default")
      (node (ref "C164") (pin "2") (pinfunction "2_2") (pintype "passive"))
      (node (ref "R87") (pin "2") (pinfunction "2_2") (pintype "passive"))
      (node (ref "R91") (pin "1") (pinfunction "1_1") (pintype "passive"))
      (node (ref "U35") (pin "4") (pinfunction "VOUT+_4") (pintype "output"))
    )
    (net (code "162") (name "Net-(U35-VOUT-)") (class "Default")
      (node (ref "R95") (pin "1") (pinfunction "1_1") (pintype "passive"))
      (node (ref "U35") (pin "5") (pinfunction "VOUT-_5") (pintype "output"))
    )
    (net (code "163") (name "Net-(U36-VIN-)") (class "Default")
      (node (ref "C165") (pin "1") (pinfunction "1_1") (pintype "passive"))
      (node (ref "PW3") (pin "2") (pintype "passive"))
      (node (ref "R88") (pin "1") (pinfunction "1_1") (pintype "passive"))
      (node (ref "U36") (pin "1") (pinfunction "VIN-_1") (pintype "input"))
    )
    (net (code "164") (name "Net-(U36-VOUT+)") (class "Default")
      (node (ref "C165") (pin "2") (pinfunction "2_2") (pintype "passive"))
      (node (ref "R88") (pin "2") (pinfunction "2_2") (pintype "passive"))
      (node (ref "R92") (pin "1") (pinfunction "1_1") (pintype "passive"))
      (node (ref "U36") (pin "4") (pinfunction "VOUT+_4") (pintype "output"))
    )
    (net (code "165") (name "Net-(U36-VOUT-)") (class "Default")
      (node (ref "R96") (pin "1") (pinfunction "1_1") (pintype "passive"))
      (node (ref "U36") (pin "5") (pinfunction "VOUT-_5") (pintype "output"))
    )
    (net (code "166") (name "Net-(U37-VIN-)") (class "Default")
      (node (ref "C178") (pin "1") (pinfunction "1_1") (pintype "passive"))
      (node (ref "PX4") (pin "2") (pintype "passive"))
      (node (ref "R97") (pin "1") (pinfunction "1_1") (pintype "passive"))
      (node (ref "U37") (pin "1") (pinfunction "VIN-_1") (pintype "input"))
    )
    (net (code "167") (name "Net-(U37-VOUT+)") (class "Default")
      (node (ref "C178") (pin "2") (pinfunction "2_2") (pintype "passive"))
      (node (ref "R101") (pin "1") (pinfunction "1_1") (pintype "passive"))
      (node (ref "R97") (pin "2") (pinfunction "2_2") (pintype "passive"))
      (node (ref "U37") (pin "4") (pinfunction "VOUT+_4") (pintype "output"))
    )
    (net (code "168") (name "Net-(U37-VOUT-)") (class "Default")
      (node (ref "R105") (pin "1") (pinfunction "1_1") (pintype "passive"))
      (node (ref "U37") (pin "5") (pinfunction "VOUT-_5") (pintype "output"))
    )
    (net (code "169") (name "Net-(U38-VIN-)") (class "Default")
      (node (ref "C179") (pin "1") (pinfunction "1_1") (pintype "passive"))
      (node (ref "PY4") (pin "2") (pintype "passive"))
      (node (ref "R98") (pin "1") (pinfunction "1_1") (pintype "passive"))
      (node (ref "U38") (pin "1") (pinfunction "VIN-_1") (pintype "input"))
    )
    (net (code "170") (name "Net-(U38-VOUT+)") (class "Default")
      (node (ref "C179") (pin "2") (pinfunction "2_2") (pintype "passive"))
      (node (ref "R102") (pin "1") (pinfunction "1_1") (pintype "passive"))
      (node (ref "R98") (pin "2") (pinfunction "2_2") (pintype "passive"))
      (node (ref "U38") (pin "4") (pinfunction "VOUT+_4") (pintype "output"))
    )
    (net (code "171") (name "Net-(U38-VOUT-)") (class "Default")
      (node (ref "R106") (pin "1") (pinfunction "1_1") (pintype "passive"))
      (node (ref "U38") (pin "5") (pinfunction "VOUT-_5") (pintype "output"))
    )
    (net (code "172") (name "Net-(U39-VIN-)") (class "Default")
      (node (ref "C180") (pin "1") (pinfunction "1_1") (pintype "passive"))
      (node (ref "PZ4") (pin "2") (pintype "passive"))
      (node (ref "R99") (pin "1") (pinfunction "1_1") (pintype "passive"))
      (node (ref "U39") (pin "1") (pinfunction "VIN-_1") (pintype "input"))
    )
    (net (code "173") (name "Net-(U39-VOUT+)") (class "Default")
      (node (ref "C180") (pin "2") (pinfunction "2_2") (pintype "passive"))
      (node (ref "R103") (pin "1") (pinfunction "1_1") (pintype "passive"))
      (node (ref "R99") (pin "2") (pinfunction "2_2") (pintype "passive"))
      (node (ref "U39") (pin "4") (pinfunction "VOUT+_4") (pintype "output"))
    )
    (net (code "174") (name "Net-(U39-VOUT-)") (class "Default")
      (node (ref "R107") (pin "1") (pinfunction "1_1") (pintype "passive"))
      (node (ref "U39") (pin "5") (pinfunction "VOUT-_5") (pintype "output"))
    )
    (net (code "175") (name "Net-(U40-VIN-)") (class "Default")
      (node (ref "C181") (pin "1") (pinfunction "1_1") (pintype "passive"))
      (node (ref "PW4") (pin "2") (pintype "passive"))
      (node (ref "R100") (pin "1") (pinfunction "1_1") (pintype "passive"))
      (node (ref "U40") (pin "1") (pinfunction "VIN-_1") (pintype "input"))
    )
    (net (code "176") (name "Net-(U40-VOUT+)") (class "Default")
      (node (ref "C181") (pin "2") (pinfunction "2_2") (pintype "passive"))
      (node (ref "R100") (pin "2") (pinfunction "2_2") (pintype "passive"))
      (node (ref "R104") (pin "1") (pinfunction "1_1") (pintype "passive"))
      (node (ref "U40") (pin "4") (pinfunction "VOUT+_4") (pintype "output"))
    )
    (net (code "177") (name "Net-(U40-VOUT-)") (class "Default")
      (node (ref "R108") (pin "1") (pinfunction "1_1") (pintype "passive"))
      (node (ref "U40") (pin "5") (pinfunction "VOUT-_5") (pintype "output"))
    )
    (net (code "178") (name "Net-(U41-VIN-)") (class "Default")
      (node (ref "C194") (pin "1") (pinfunction "1_1") (pintype "passive"))
      (node (ref "P9") (pin "2") (pintype "passive"))
      (node (ref "R109") (pin "1") (pinfunction "1_1") (pintype "passive"))
      (node (ref "U41") (pin "1") (pinfunction "VIN-_1") (pintype "input"))
    )
    (net (code "179") (name "Net-(U41-VOUT+)") (class "Default")
      (node (ref "C194") (pin "2") (pinfunction "2_2") (pintype "passive"))
      (node (ref "R109") (pin "2") (pinfunction "2_2") (pintype "passive"))
      (node (ref "R110") (pin "1") (pinfunction "1_1") (pintype "passive"))
      (node (ref "U41") (pin "4") (pinfunction "VOUT+_4") (pintype "output"))
    )
    (net (code "180") (name "Net-(U41-VOUT-)") (class "Default")
      (node (ref "R111") (pin "1") (pinfunction "1_1") (pintype "passive"))
      (node (ref "U41") (pin "5") (pinfunction "VOUT-_5") (pintype "output"))
    )
    (net (code "181") (name "unconnected-(R52-Pad4)") (class "Default")
      (node (ref "R52") (pin "4") (pinfunction "4_4") (pintype "passive+no_connect"))
    )
    (net (code "182") (name "unconnected-(R52-Pad5)") (class "Default")
      (node (ref "R52") (pin "5") (pinfunction "5_5") (pintype "passive+no_connect"))
    )
    (net (code "183") (name "unconnected-(R53-Pad4)") (class "Default")
      (node (ref "R53") (pin "4") (pinfunction "4_4") (pintype "passive+no_connect"))
    )
    (net (code "184") (name "unconnected-(R53-Pad5)") (class "Default")
      (node (ref "R53") (pin "5") (pinfunction "5_5") (pintype "passive+no_connect"))
    )
    (net (code "185") (name "unconnected-(R55-Pad4)") (class "Default")
      (node (ref "R55") (pin "4") (pinfunction "4_4") (pintype "passive+no_connect"))
    )
    (net (code "186") (name "unconnected-(R55-Pad5)") (class "Default")
      (node (ref "R55") (pin "5") (pinfunction "5_5") (pintype "passive+no_connect"))
    )
    (net (code "187") (name "unconnected-(R57-Pad4)") (class "Default")
      (node (ref "R57") (pin "4") (pinfunction "4_4") (pintype "passive+no_connect"))
    )
    (net (code "188") (name "unconnected-(R57-Pad5)") (class "Default")
      (node (ref "R57") (pin "5") (pinfunction "5_5") (pintype "passive+no_connect"))
    )
    (net (code "189") (name "unconnected-(R60-Pad4)") (class "Default")
      (node (ref "R60") (pin "4") (pinfunction "4_4") (pintype "passive+no_connect"))
    )
    (net (code "190") (name "unconnected-(R60-Pad5)") (class "Default")
      (node (ref "R60") (pin "5") (pinfunction "5_5") (pintype "passive+no_connect"))
    )
    (net (code "191") (name "unconnected-(U15B-DNC{slash}SCK--Pad42)") (class "Default")
      (node (ref "U15") (pin "42") (pinfunction "DNC/SCK-_42") (pintype "passive+no_connect"))
    )
    (net (code "192") (name "unconnected-(U15B-DNC{slash}SDOA--Pad28)") (class "Default")
      (node (ref "U15") (pin "28") (pinfunction "DNC/SDOA-_28") (pintype "passive+no_connect"))
    )
    (net (code "193") (name "unconnected-(U15B-DNC{slash}SDOB--Pad30)") (class "Default")
      (node (ref "U15") (pin "30") (pinfunction "DNC/SDOB-_30") (pintype "passive+no_connect"))
    )
    (net (code "194") (name "unconnected-(U15B-DNC{slash}SDOC--Pad36)") (class "Default")
      (node (ref "U15") (pin "36") (pinfunction "DNC/SDOC-_36") (pintype "passive+no_connect"))
    )
    (net (code "195") (name "unconnected-(U15B-DNC{slash}SDOD--Pad40)") (class "Default")
      (node (ref "U15") (pin "40") (pinfunction "DNC/SDOD-_40") (pintype "passive+no_connect"))
    )
    (net (code "196") (name "unconnected-(U15B-NC-Pad16)") (class "Default")
      (node (ref "U15") (pin "16") (pinfunction "NC_16") (pintype "passive+no_connect"))
    )
    (net (code "197") (name "unconnected-(U15B-NC-Pad17)") (class "Default")
      (node (ref "U15") (pin "17") (pinfunction "NC_17") (pintype "passive+no_connect"))
    )
    (net (code "198") (name "unconnected-(U15B-NC-Pad19)") (class "Default")
      (node (ref "U15") (pin "19") (pinfunction "NC_19") (pintype "passive+no_connect"))
    )
    (net (code "199") (name "unconnected-(U15B-NC-Pad20)") (class "Default")
      (node (ref "U15") (pin "20") (pinfunction "NC_20") (pintype "passive+no_connect"))
    )
    (net (code "200") (name "unconnected-(U15B-NC-Pad47)") (class "Default")
      (node (ref "U15") (pin "47") (pinfunction "NC_47") (pintype "passive+no_connect"))
    )
    (net (code "201") (name "unconnected-(U15B-NC-Pad48)") (class "Default")
      (node (ref "U15") (pin "48") (pinfunction "NC_48") (pintype "passive+no_connect"))
    )
    (net (code "202") (name "unconnected-(U15B-NC-Pad50)") (class "Default")
      (node (ref "U15") (pin "50") (pinfunction "NC_50") (pintype "passive+no_connect"))
    )
    (net (code "203") (name "unconnected-(U15B-NC-Pad51)") (class "Default")
      (node (ref "U15") (pin "51") (pinfunction "NC_51") (pintype "passive+no_connect"))
    )
    (net (code "204") (name "unconnected-(U16B-DNC{slash}SCK--Pad42)") (class "Default")
      (node (ref "U16") (pin "42") (pinfunction "DNC/SCK-_42") (pintype "passive+no_connect"))
    )
    (net (code "205") (name "unconnected-(U16B-DNC{slash}SDOA--Pad28)") (class "Default")
      (node (ref "U16") (pin "28") (pinfunction "DNC/SDOA-_28") (pintype "passive+no_connect"))
    )
    (net (code "206") (name "unconnected-(U16B-DNC{slash}SDOB--Pad30)") (class "Default")
      (node (ref "U16") (pin "30") (pinfunction "DNC/SDOB-_30") (pintype "passive+no_connect"))
    )
    (net (code "207") (name "unconnected-(U16B-DNC{slash}SDOC--Pad36)") (class "Default")
      (node (ref "U16") (pin "36") (pinfunction "DNC/SDOC-_36") (pintype "passive+no_connect"))
    )
    (net (code "208") (name "unconnected-(U16B-DNC{slash}SDOD--Pad40)") (class "Default")
      (node (ref "U16") (pin "40") (pinfunction "DNC/SDOD-_40") (pintype "passive+no_connect"))
    )
    (net (code "209") (name "unconnected-(U16B-NC-Pad16)") (class "Default")
      (node (ref "U16") (pin "16") (pinfunction "NC_16") (pintype "passive+no_connect"))
    )
    (net (code "210") (name "unconnected-(U16B-NC-Pad17)") (class "Default")
      (node (ref "U16") (pin "17") (pinfunction "NC_17") (pintype "passive+no_connect"))
    )
    (net (code "211") (name "unconnected-(U16B-NC-Pad19)") (class "Default")
      (node (ref "U16") (pin "19") (pinfunction "NC_19") (pintype "passive+no_connect"))
    )
    (net (code "212") (name "unconnected-(U16B-NC-Pad20)") (class "Default")
      (node (ref "U16") (pin "20") (pinfunction "NC_20") (pintype "passive+no_connect"))
    )
    (net (code "213") (name "unconnected-(U16B-NC-Pad47)") (class "Default")
      (node (ref "U16") (pin "47") (pinfunction "NC_47") (pintype "passive+no_connect"))
    )
    (net (code "214") (name "unconnected-(U16B-NC-Pad48)") (class "Default")
      (node (ref "U16") (pin "48") (pinfunction "NC_48") (pintype "passive+no_connect"))
    )
    (net (code "215") (name "unconnected-(U16B-NC-Pad50)") (class "Default")
      (node (ref "U16") (pin "50") (pinfunction "NC_50") (pintype "passive+no_connect"))
    )
    (net (code "216") (name "unconnected-(U16B-NC-Pad51)") (class "Default")
      (node (ref "U16") (pin "51") (pinfunction "NC_51") (pintype "passive+no_connect"))
    )
    (net (code "217") (name "unconnected-(U17B-DNC{slash}SCK--Pad42)") (class "Default")
      (node (ref "U17") (pin "42") (pinfunction "DNC/SCK-_42") (pintype "passive+no_connect"))
    )
    (net (code "218") (name "unconnected-(U17B-DNC{slash}SDOA--Pad28)") (class "Default")
      (node (ref "U17") (pin "28") (pinfunction "DNC/SDOA-_28") (pintype "passive+no_connect"))
    )
    (net (code "219") (name "unconnected-(U17B-DNC{slash}SDOB--Pad30)") (class "Default")
      (node (ref "U17") (pin "30") (pinfunction "DNC/SDOB-_30") (pintype "passive+no_connect"))
    )
    (net (code "220") (name "unconnected-(U17B-DNC{slash}SDOC--Pad36)") (class "Default")
      (node (ref "U17") (pin "36") (pinfunction "DNC/SDOC-_36") (pintype "passive+no_connect"))
    )
    (net (code "221") (name "unconnected-(U17B-DNC{slash}SDOD--Pad40)") (class "Default")
      (node (ref "U17") (pin "40") (pinfunction "DNC/SDOD-_40") (pintype "passive+no_connect"))
    )
    (net (code "222") (name "unconnected-(U17B-NC-Pad16)") (class "Default")
      (node (ref "U17") (pin "16") (pinfunction "NC_16") (pintype "passive+no_connect"))
    )
    (net (code "223") (name "unconnected-(U17B-NC-Pad17)") (class "Default")
      (node (ref "U17") (pin "17") (pinfunction "NC_17") (pintype "passive+no_connect"))
    )
    (net (code "224") (name "unconnected-(U17B-NC-Pad19)") (class "Default")
      (node (ref "U17") (pin "19") (pinfunction "NC_19") (pintype "passive+no_connect"))
    )
    (net (code "225") (name "unconnected-(U17B-NC-Pad20)") (class "Default")
      (node (ref "U17") (pin "20") (pinfunction "NC_20") (pintype "passive+no_connect"))
    )
    (net (code "226") (name "unconnected-(U17B-NC-Pad47)") (class "Default")
      (node (ref "U17") (pin "47") (pinfunction "NC_47") (pintype "passive+no_connect"))
    )
    (net (code "227") (name "unconnected-(U17B-NC-Pad48)") (class "Default")
      (node (ref "U17") (pin "48") (pinfunction "NC_48") (pintype "passive+no_connect"))
    )
    (net (code "228") (name "unconnected-(U17B-NC-Pad50)") (class "Default")
      (node (ref "U17") (pin "50") (pinfunction "NC_50") (pintype "passive+no_connect"))
    )
    (net (code "229") (name "unconnected-(U17B-NC-Pad51)") (class "Default")
      (node (ref "U17") (pin "51") (pinfunction "NC_51") (pintype "passive+no_connect"))
    )
    (net (code "230") (name "unconnected-(U18B-DNC{slash}SCK--Pad42)") (class "Default")
      (node (ref "U18") (pin "42") (pinfunction "DNC/SCK-_42") (pintype "passive+no_connect"))
    )
    (net (code "231") (name "unconnected-(U18B-DNC{slash}SDOA--Pad28)") (class "Default")
      (node (ref "U18") (pin "28") (pinfunction "DNC/SDOA-_28") (pintype "passive+no_connect"))
    )
    (net (code "232") (name "unconnected-(U18B-DNC{slash}SDOB--Pad30)") (class "Default")
      (node (ref "U18") (pin "30") (pinfunction "DNC/SDOB-_30") (pintype "passive+no_connect"))
    )
    (net (code "233") (name "unconnected-(U18B-DNC{slash}SDOC--Pad36)") (class "Default")
      (node (ref "U18") (pin "36") (pinfunction "DNC/SDOC-_36") (pintype "passive+no_connect"))
    )
    (net (code "234") (name "unconnected-(U18B-DNC{slash}SDOD--Pad40)") (class "Default")
      (node (ref "U18") (pin "40") (pinfunction "DNC/SDOD-_40") (pintype "passive+no_connect"))
    )
    (net (code "235") (name "unconnected-(U18B-NC-Pad16)") (class "Default")
      (node (ref "U18") (pin "16") (pinfunction "NC_16") (pintype "passive+no_connect"))
    )
    (net (code "236") (name "unconnected-(U18B-NC-Pad17)") (class "Default")
      (node (ref "U18") (pin "17") (pinfunction "NC_17") (pintype "passive+no_connect"))
    )
    (net (code "237") (name "unconnected-(U18B-NC-Pad19)") (class "Default")
      (node (ref "U18") (pin "19") (pinfunction "NC_19") (pintype "passive+no_connect"))
    )
    (net (code "238") (name "unconnected-(U18B-NC-Pad20)") (class "Default")
      (node (ref "U18") (pin "20") (pinfunction "NC_20") (pintype "passive+no_connect"))
    )
    (net (code "239") (name "unconnected-(U18B-NC-Pad47)") (class "Default")
      (node (ref "U18") (pin "47") (pinfunction "NC_47") (pintype "passive+no_connect"))
    )
    (net (code "240") (name "unconnected-(U18B-NC-Pad48)") (class "Default")
      (node (ref "U18") (pin "48") (pinfunction "NC_48") (pintype "passive+no_connect"))
    )
    (net (code "241") (name "unconnected-(U18B-NC-Pad50)") (class "Default")
      (node (ref "U18") (pin "50") (pinfunction "NC_50") (pintype "passive+no_connect"))
    )
    (net (code "242") (name "unconnected-(U18B-NC-Pad51)") (class "Default")
      (node (ref "U18") (pin "51") (pinfunction "NC_51") (pintype "passive+no_connect"))
    )
    (net (code "243") (name "unconnected-(U19-SCK--Pad15)") (class "Default")
      (node (ref "U19") (pin "15") (pinfunction "SCK-_15") (pintype "input+no_connect"))
    )
    (net (code "244") (name "unconnected-(U19-SDO--Pad13)") (class "Default")
      (node (ref "U19") (pin "13") (pinfunction "SDO-_13") (pintype "output+no_connect"))
    )
  )
)
